# Sheet1.net
KiCad netlist of a schematic drawn in Altium Designer
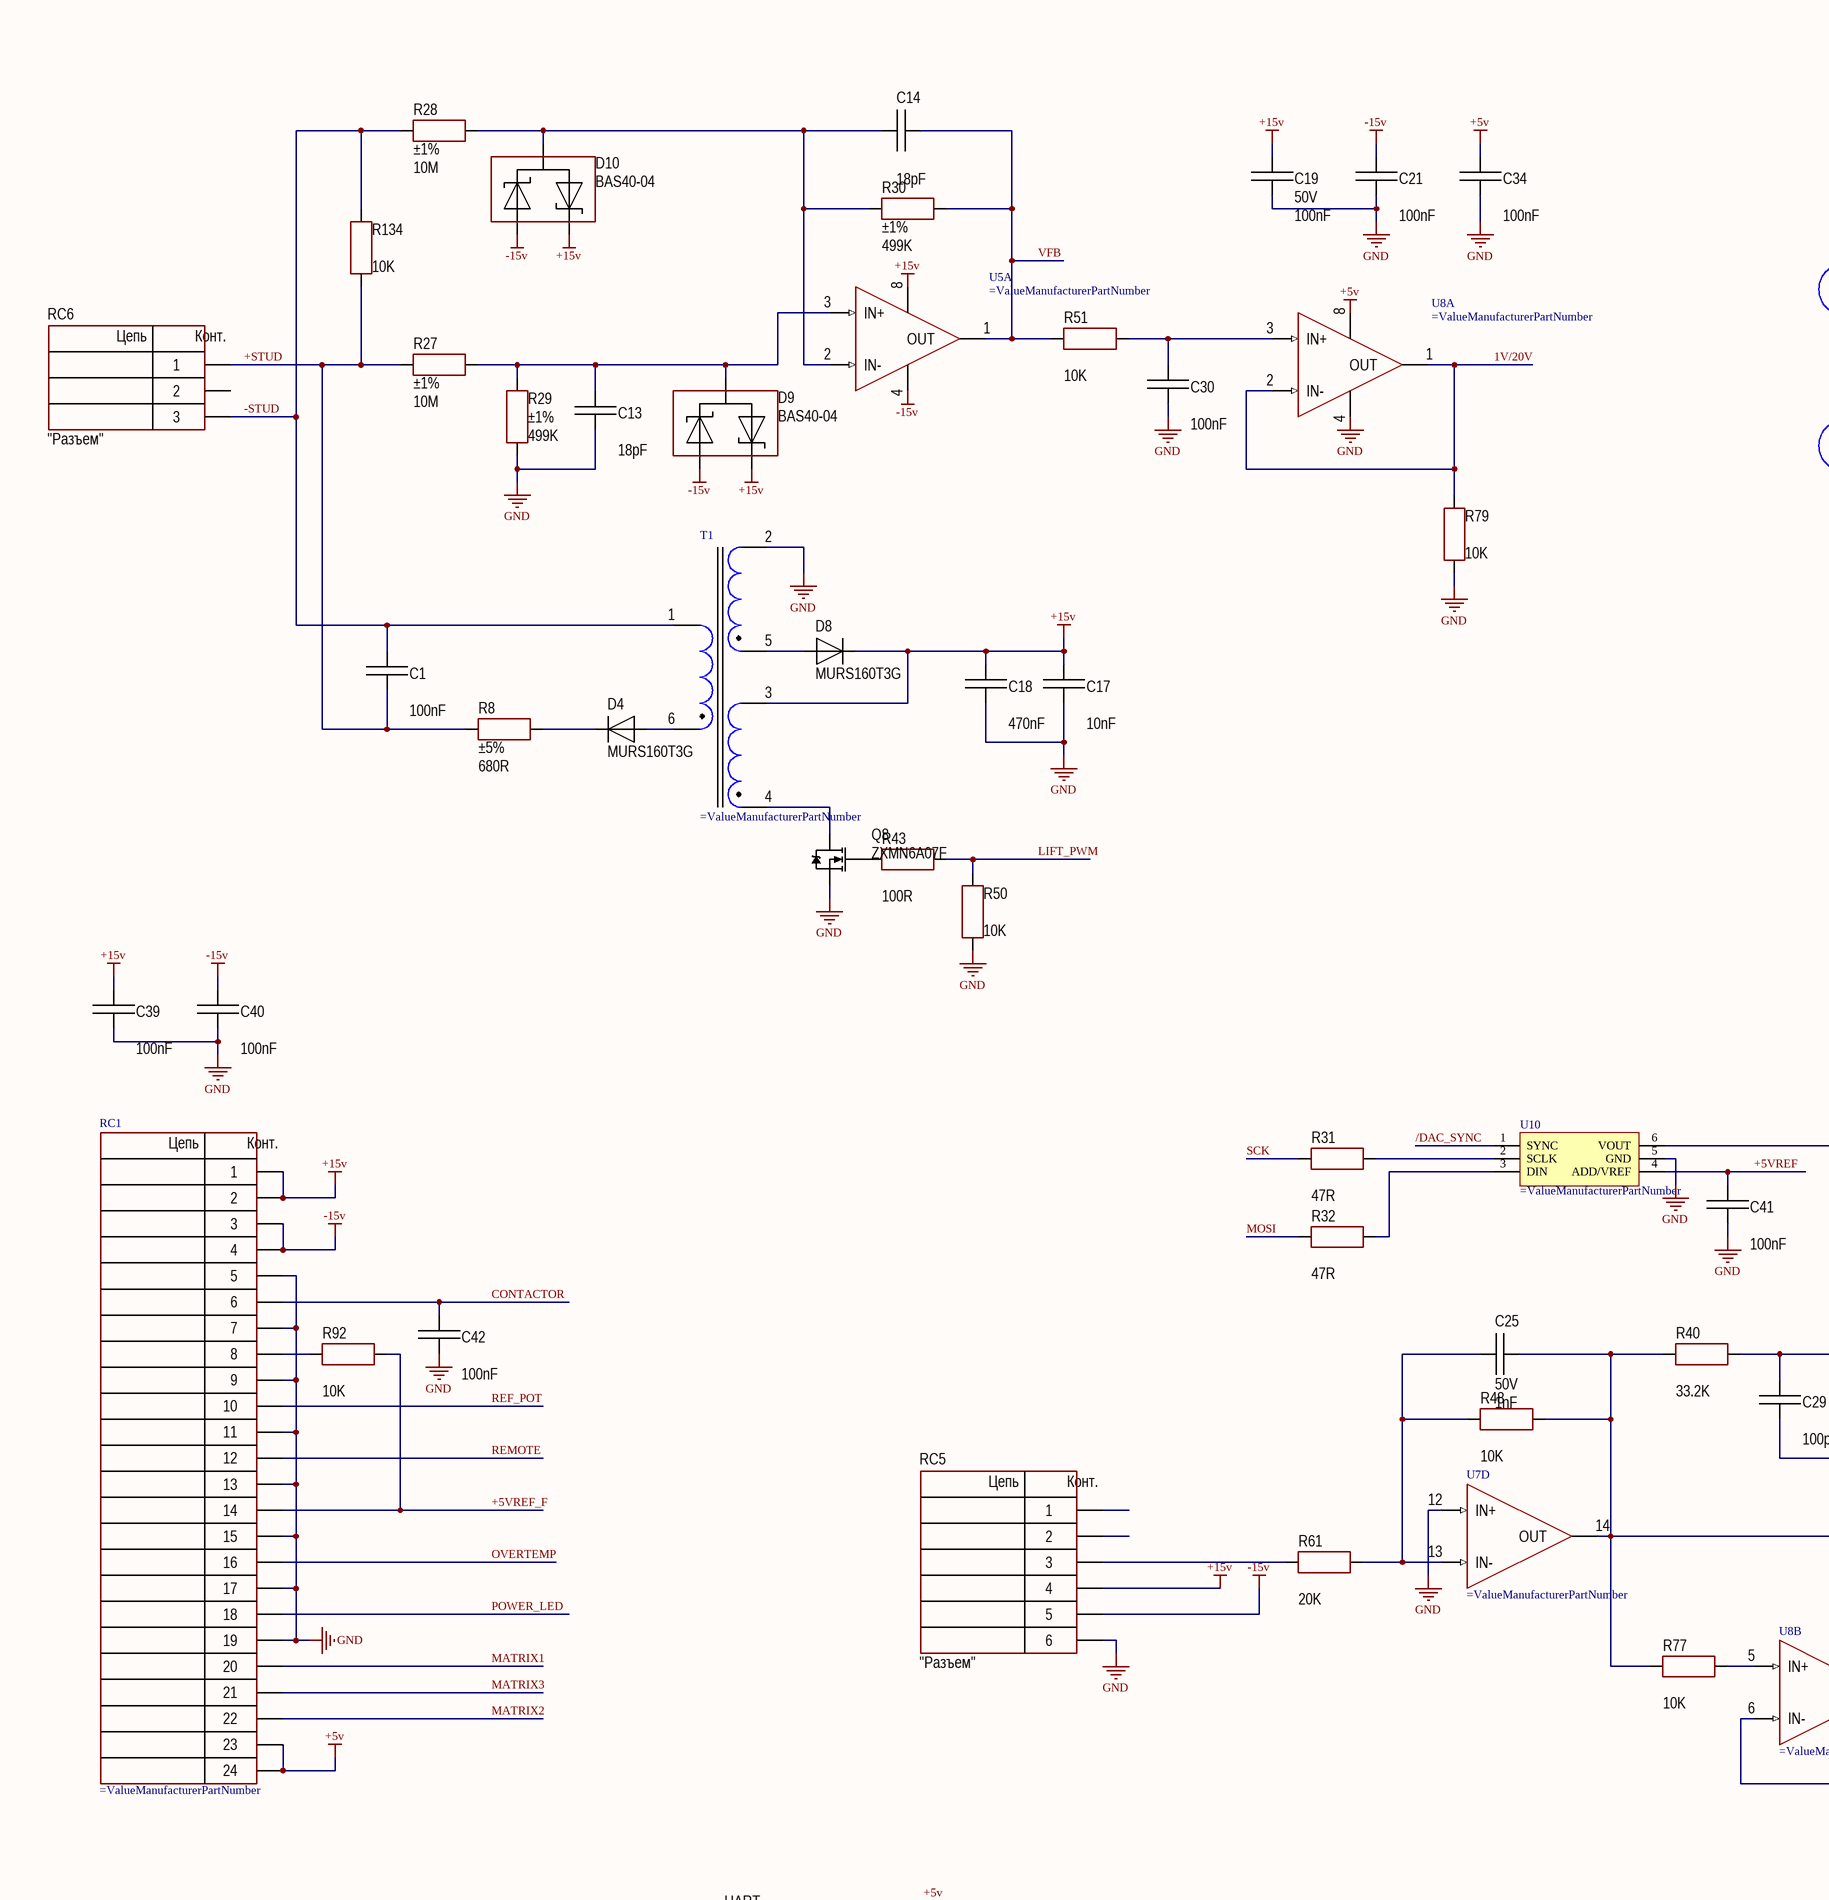
[diagram p0: Sheet1.SchDoc, top left]
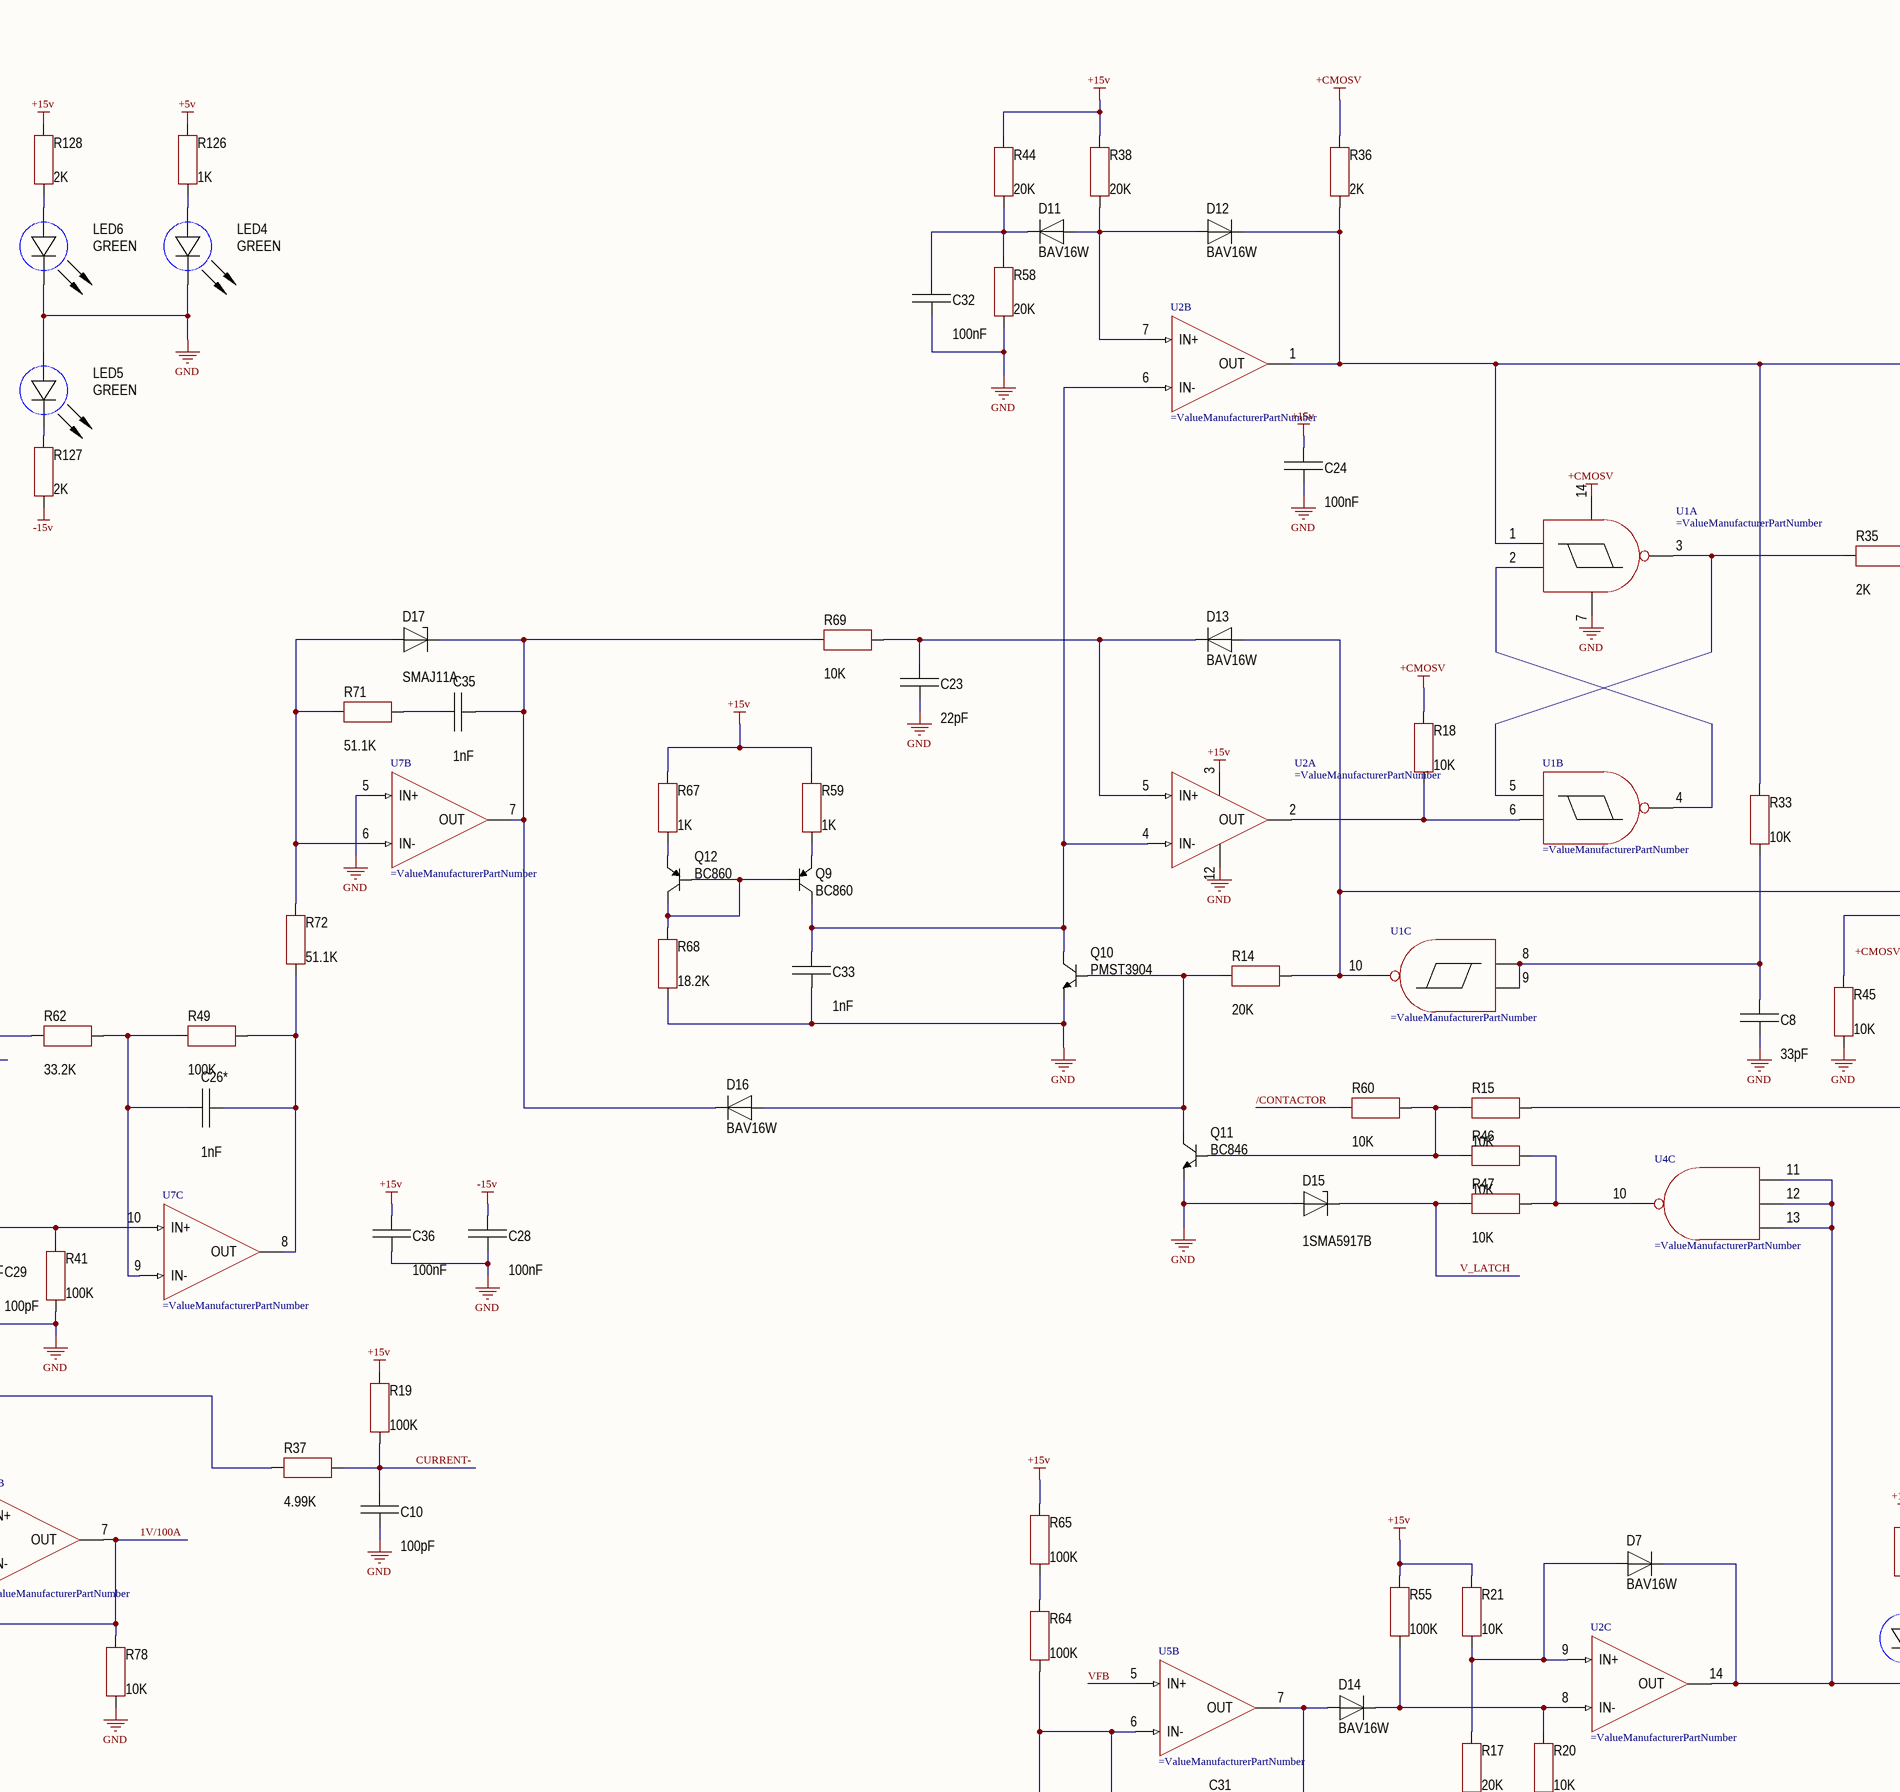
[diagram p1: Sheet1.SchDoc, top middle]
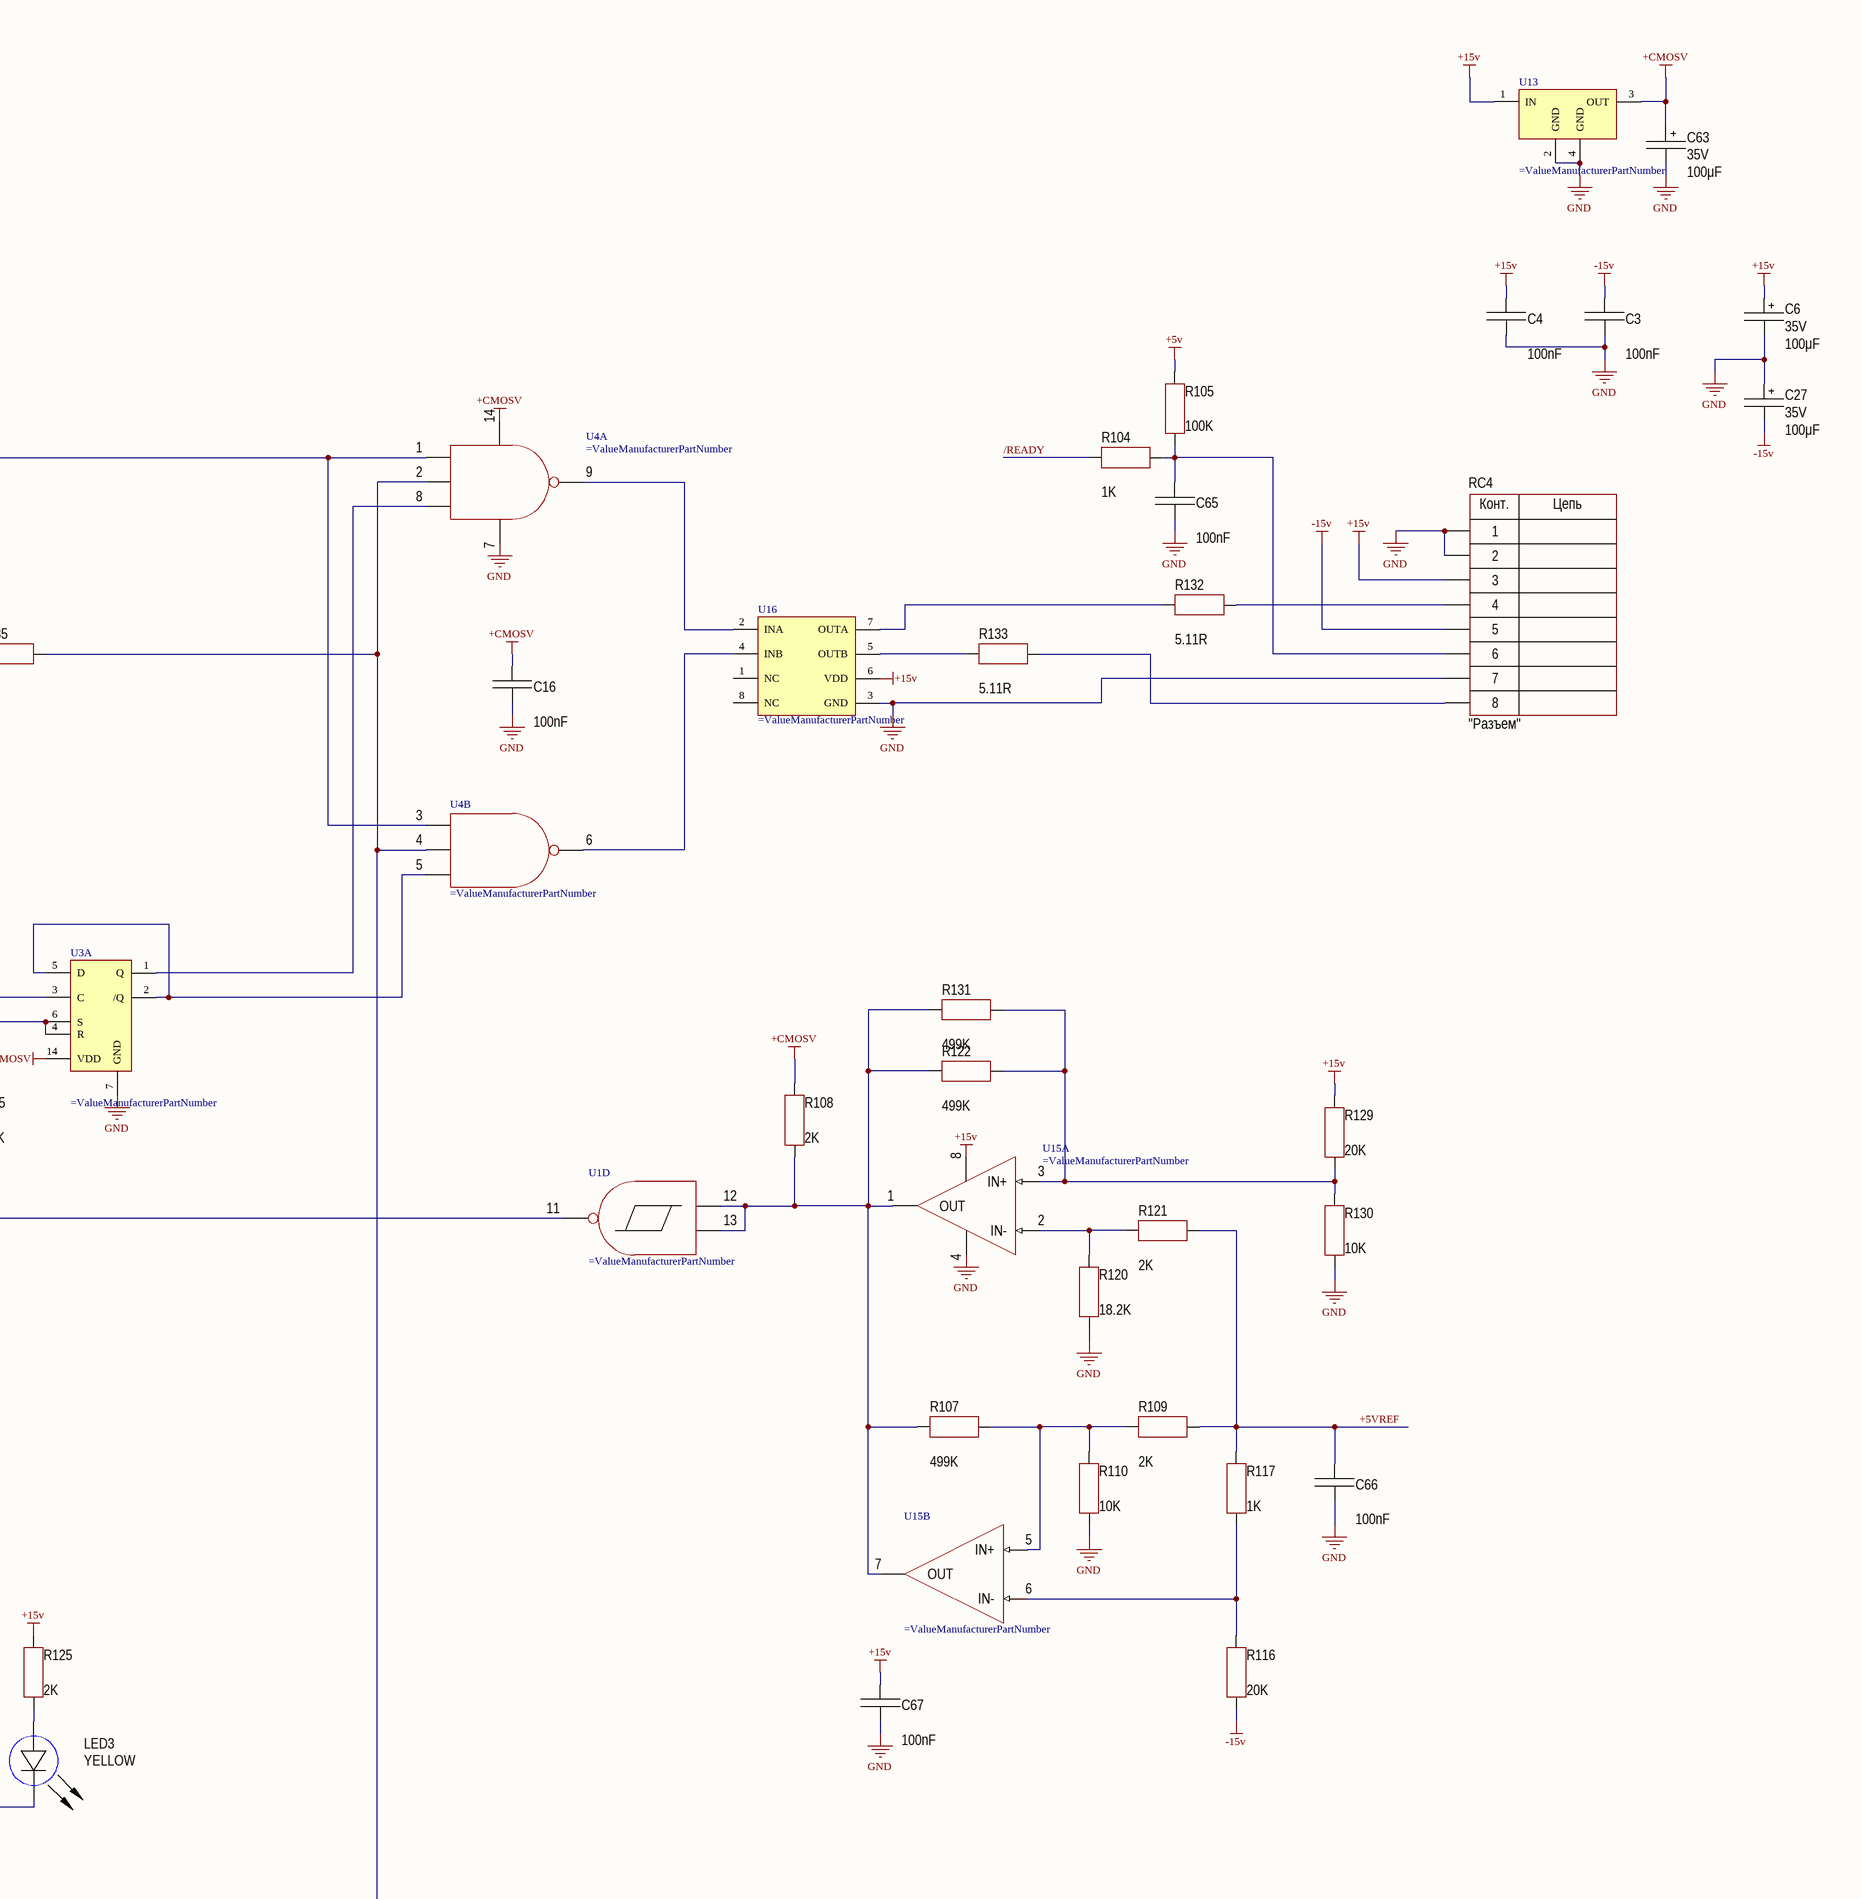
[diagram p2: Sheet1.SchDoc, top right]
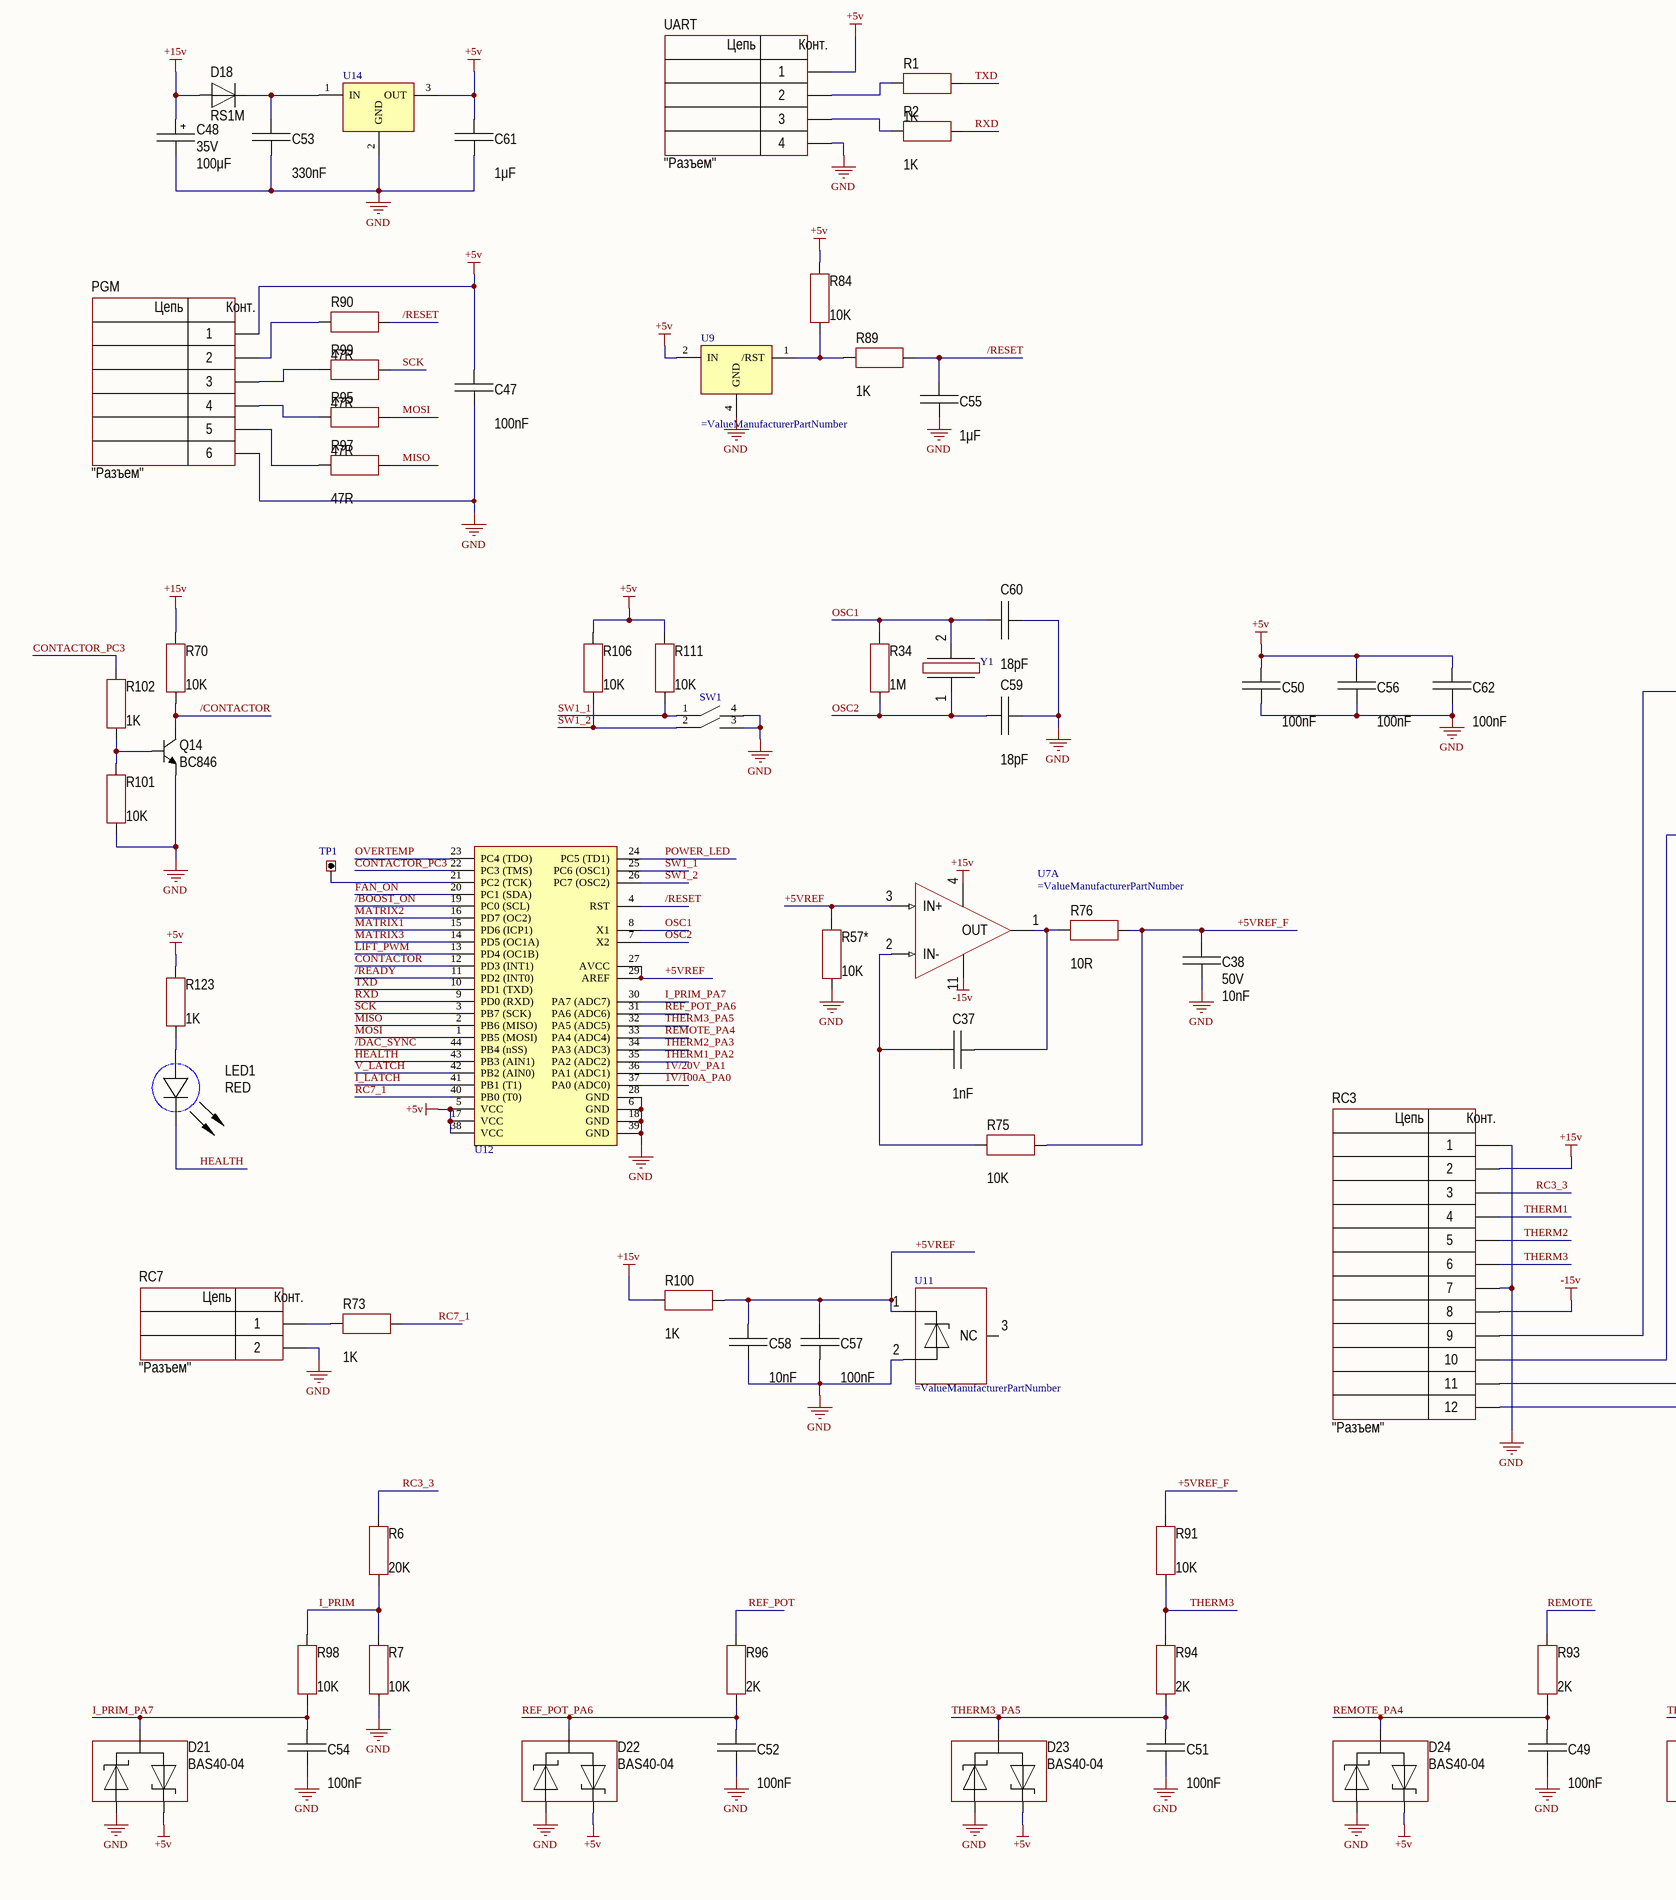
[diagram p3: Sheet1.SchDoc, bottom left]
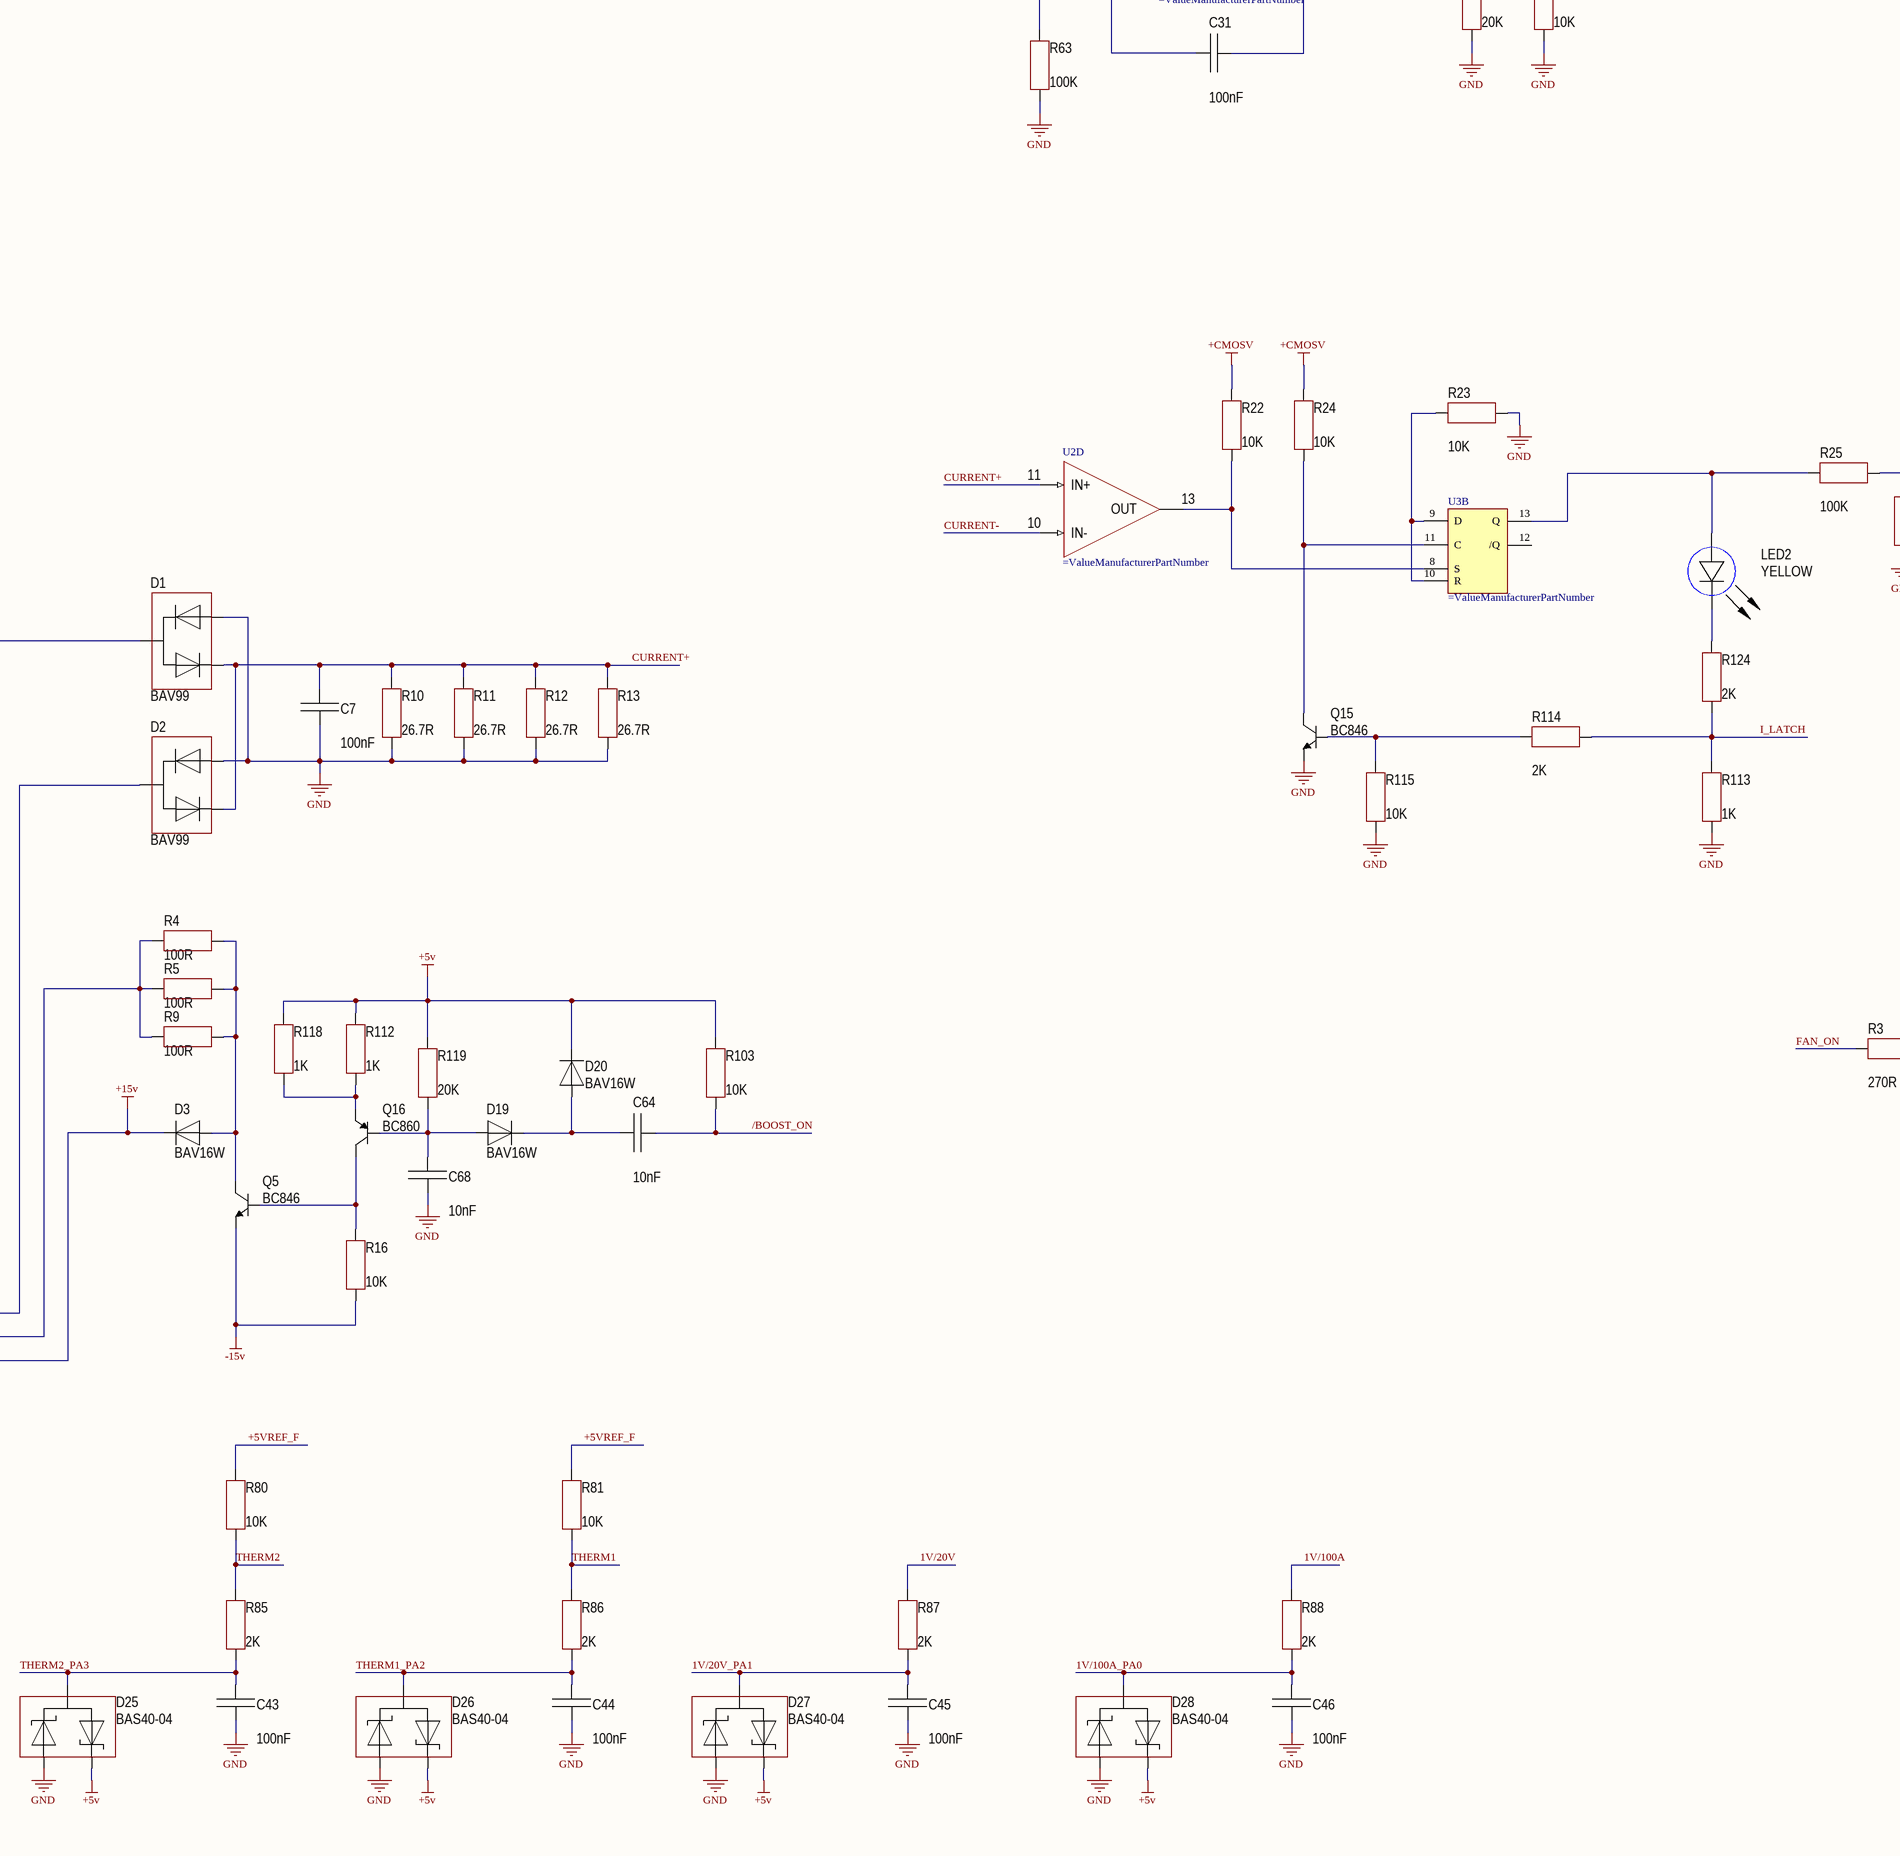
[diagram p4: Sheet1.SchDoc, bottom middle]
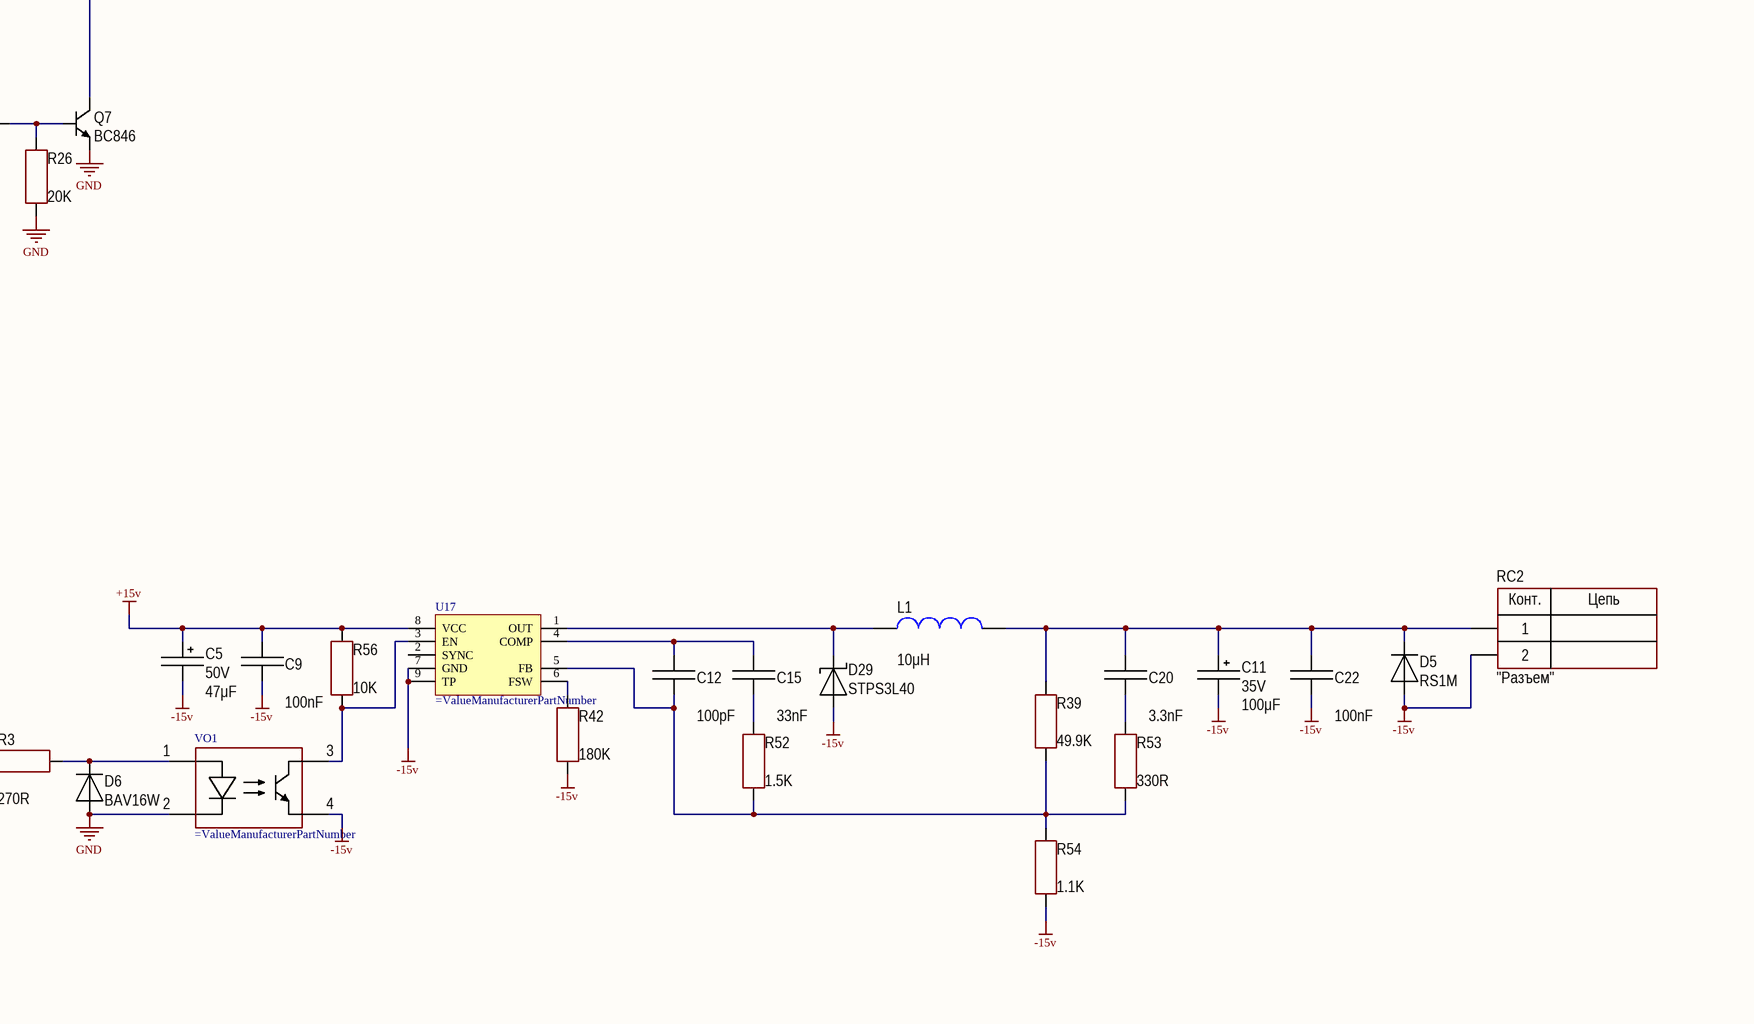
[diagram p5: Sheet1.SchDoc, bottom right]

(export (version "E")
  (design (tool "Eeschema 10.0.6"))
  (components
    (comp (ref "C1")
      (value "100nF")
      (footprint "PcbLib1:К10-17Б")
      (fields
        (field (name "MANUFACTURER") "Yageo")
        (field (name "PARTNUMBER") "CC1206KRX7R9BB104")
        (field (name "VALUEMANUFACTURERPARTNUMBER") "Capacitor, 100nF, К10-17Б")
      )
      (libsource (lib "Capacitor") (part "Ceramic_1206"))
    )
    (comp (ref "C3")
      (value "100nF")
      (footprint "StandardCase:CAP: 1206")
      (fields
        (field (name "MANUFACTURER") "Yageo")
        (field (name "PARTNUMBER") "CC1206KRX7R9BB104")
        (field (name "VALUEMANUFACTURERPARTNUMBER") "Ceramic capacitor, 100nF, 1206")
      )
      (libsource (lib "Capacitor") (part "Ceramic_1206"))
    )
    (comp (ref "C4")
      (value "100nF")
      (footprint "StandardCase:CAP: 1206")
      (fields
        (field (name "MANUFACTURER") "Yageo")
        (field (name "PARTNUMBER") "CC1206KRX7R9BB104")
        (field (name "VALUEMANUFACTURERPARTNUMBER") "Ceramic capacitor, 100nF, 1206")
      )
      (libsource (lib "Capacitor") (part "Ceramic_1206"))
    )
    (comp (ref "C5")
      (value "47μF")
      (footprint "PcbLib1:CAPAE7466X80L")
      (fields
        (field (name "MANUFACTURER") "Wurth")
        (field (name "PARTNUMBER") "EEEFK1H470XP")
        (field (name "VALUEMANUFACTURERPARTNUMBER") "EEEFK1H470XP, 47μF, 50V, D8")
        (field (name "VOLTAGE") "50V")
      )
      (libsource (lib "Capacitor") (part "Aluminium"))
    )
    (comp (ref "C6")
      (value "100μF")
      (footprint "PcbLib1:CAPAE7466X80L")
      (fields
        (field (name "MANUFACTURER") "Wurth")
        (field (name "PARTNUMBER") "EEEFK1V101XP")
        (field (name "VALUEMANUFACTURERPARTNUMBER") "EEEFK1V101XP, 100μF, 35V, D8")
        (field (name "VOLTAGE") "35V")
      )
      (libsource (lib "Capacitor") (part "Aluminium"))
    )
    (comp (ref "C7")
      (value "100nF")
      (footprint "StandardCase:CAP: 1206")
      (fields
        (field (name "MANUFACTURER") "Yageo")
        (field (name "PARTNUMBER") "CC1206KRX7R9BB104")
        (field (name "VALUEMANUFACTURERPARTNUMBER") "Ceramic capacitor, 100nF, 1206")
      )
      (libsource (lib "Capacitor") (part "Ceramic_1206"))
    )
    (comp (ref "C8")
      (value "33pF")
      (footprint "StandardCase:CAP: 1206")
      (fields
        (field (name "MANUFACTURER") "Yageo")
        (field (name "PARTNUMBER") "CC1206KRX7R9BB104")
        (field (name "VALUEMANUFACTURERPARTNUMBER") "Ceramic capacitor, 33pF, 1206")
      )
      (libsource (lib "Capacitor") (part "Ceramic_1206"))
    )
    (comp (ref "C9")
      (value "100nF")
      (footprint "StandardCase:CAP: 1206")
      (fields
        (field (name "MANUFACTURER") "Yageo")
        (field (name "PARTNUMBER") "CC1206KRX7R9BB104")
        (field (name "VALUEMANUFACTURERPARTNUMBER") "Ceramic capacitor, 100nF, 1206")
      )
      (libsource (lib "Capacitor") (part "Ceramic_1206"))
    )
    (comp (ref "C10")
      (value "100pF")
      (footprint "StandardCase:CAP: 1206")
      (fields
        (field (name "MANUFACTURER") "Yageo")
        (field (name "PARTNUMBER") "CC1206KRX7R9BB104")
        (field (name "VALUEMANUFACTURERPARTNUMBER") "Ceramic capacitor, 100pF, 1206")
      )
      (libsource (lib "Capacitor") (part "Ceramic_1206"))
    )
    (comp (ref "C11")
      (value "100μF")
      (footprint "PcbLib1:CAPAE7466X80L")
      (fields
        (field (name "MANUFACTURER") "Wurth")
        (field (name "PARTNUMBER") "EEEFK1V101XP")
        (field (name "VALUEMANUFACTURERPARTNUMBER") "EEEFK1V101XP, 100μF, 35V, D8")
        (field (name "VOLTAGE") "35V")
      )
      (libsource (lib "Capacitor") (part "Aluminium"))
    )
    (comp (ref "C12")
      (value "100pF")
      (footprint "StandardCase:CAP: 1206")
      (fields
        (field (name "MANUFACTURER") "Yageo")
        (field (name "PARTNUMBER") "CC1206KRX7R9BB104")
        (field (name "VALUEMANUFACTURERPARTNUMBER") "Ceramic capacitor, 100pF, 1206")
      )
      (libsource (lib "Capacitor") (part "Ceramic_1206"))
    )
    (comp (ref "C13")
      (value "18pF")
      (footprint "StandardCase:CAP: 1206")
      (fields
        (field (name "MANUFACTURER") "Yageo")
        (field (name "PARTNUMBER") "CC1206KRX7R9BB104")
        (field (name "VALUEMANUFACTURERPARTNUMBER") "Ceramic capacitor, 18pF, 1206")
      )
      (libsource (lib "Capacitor") (part "Ceramic_1206"))
    )
    (comp (ref "C14")
      (value "18pF")
      (footprint "StandardCase:CAP: 1206")
      (fields
        (field (name "MANUFACTURER") "Yageo")
        (field (name "PARTNUMBER") "CC1206KRX7R9BB104")
        (field (name "VALUEMANUFACTURERPARTNUMBER") "Ceramic capacitor, 18pF, 1206")
      )
      (libsource (lib "Capacitor") (part "Ceramic_1206"))
    )
    (comp (ref "C15")
      (value "33nF")
      (footprint "StandardCase:CAP: 1206")
      (fields
        (field (name "MANUFACTURER") "Yageo")
        (field (name "PARTNUMBER") "CC1206KRX7R9BB104")
        (field (name "VALUEMANUFACTURERPARTNUMBER") "Ceramic capacitor, 33nF, 1206")
      )
      (libsource (lib "Capacitor") (part "Ceramic_1206"))
    )
    (comp (ref "C16")
      (value "100nF")
      (footprint "StandardCase:CAP: 1206")
      (fields
        (field (name "MANUFACTURER") "Yageo")
        (field (name "PARTNUMBER") "CC1206KRX7R9BB104")
        (field (name "VALUEMANUFACTURERPARTNUMBER") "Ceramic capacitor, 100nF, 1206")
      )
      (libsource (lib "Capacitor") (part "Ceramic_1206"))
    )
    (comp (ref "C17")
      (value "10nF")
      (footprint "StandardCase:CAP: 1206")
      (fields
        (field (name "MANUFACTURER") "Yageo")
        (field (name "PARTNUMBER") "CC1206KRX7R9BB104")
        (field (name "VALUEMANUFACTURERPARTNUMBER") "Ceramic capacitor, 10nF, 1206")
      )
      (libsource (lib "Capacitor") (part "Ceramic_1206"))
    )
    (comp (ref "C18")
      (value "470nF")
      (footprint "StandardCase:CAP: 1206")
      (fields
        (field (name "MANUFACTURER") "Yageo")
        (field (name "PARTNUMBER") "CC1206KRX7R9BB104")
        (field (name "VALUEMANUFACTURERPARTNUMBER") "Ceramic capacitor, 470nF, 1206")
      )
      (libsource (lib "Capacitor") (part "Ceramic_1206"))
    )
    (comp (ref "C19")
      (value "100nF")
      (footprint "StandardCase:CAP: 1206")
      (fields
        (field (name "MANUFACTURER") "Yageo")
        (field (name "PARTNUMBER") "CC1206KRX7R9BB104")
        (field (name "VALUEMANUFACTURERPARTNUMBER") "Ceramic capacitor, 100nF, 1206")
        (field (name "VOLTAGE") "50V")
      )
      (libsource (lib "Capacitor") (part "Ceramic_1206"))
    )
    (comp (ref "C20")
      (value "3.3nF")
      (footprint "StandardCase:CAP: 1206")
      (fields
        (field (name "MANUFACTURER") "Yageo")
        (field (name "PARTNUMBER") "CC1206KRX7R9BB104")
        (field (name "VALUEMANUFACTURERPARTNUMBER") "Ceramic capacitor, 3.3nF, 1206")
      )
      (libsource (lib "Capacitor") (part "Ceramic_1206"))
    )
    (comp (ref "C21")
      (value "100nF")
      (footprint "StandardCase:CAP: 1206")
      (fields
        (field (name "MANUFACTURER") "Yageo")
        (field (name "PARTNUMBER") "CC1206KRX7R9BB104")
        (field (name "VALUEMANUFACTURERPARTNUMBER") "Ceramic capacitor, 100nF, 1206")
      )
      (libsource (lib "Capacitor") (part "Ceramic_1206"))
    )
    (comp (ref "C22")
      (value "100nF")
      (footprint "StandardCase:CAP: 1206")
      (fields
        (field (name "MANUFACTURER") "Yageo")
        (field (name "PARTNUMBER") "CC1206KRX7R9BB104")
        (field (name "VALUEMANUFACTURERPARTNUMBER") "Ceramic capacitor, 100nF, 1206")
      )
      (libsource (lib "Capacitor") (part "Ceramic_1206"))
    )
    (comp (ref "C23")
      (value "22pF")
      (footprint "StandardCase:CAP: 1206")
      (fields
        (field (name "MANUFACTURER") "Yageo")
        (field (name "PARTNUMBER") "CC1206KRX7R9BB104")
        (field (name "VALUEMANUFACTURERPARTNUMBER") "Ceramic capacitor, 22pF, 1206")
      )
      (libsource (lib "Capacitor") (part "Ceramic_1206"))
    )
    (comp (ref "C24")
      (value "100nF")
      (footprint "StandardCase:CAP: 1206")
      (fields
        (field (name "MANUFACTURER") "Yageo")
        (field (name "PARTNUMBER") "CC1206KRX7R9BB104")
        (field (name "VALUEMANUFACTURERPARTNUMBER") "Ceramic capacitor, 100nF, 1206")
      )
      (libsource (lib "Capacitor") (part "Ceramic_1206"))
    )
    (comp (ref "C25")
      (value "1nF")
      (footprint "StandardCase:CAP: 1206")
      (fields
        (field (name "MANUFACTURER") "Yageo")
        (field (name "PARTNUMBER") "CC1206KRX7R9BB104")
        (field (name "VALUEMANUFACTURERPARTNUMBER") "Ceramic capacitor, 1nF, 1206")
        (field (name "VOLTAGE") "50V")
      )
      (libsource (lib "Capacitor") (part "Ceramic_1206"))
    )
    (comp (ref "C26*")
      (value "1nF")
      (footprint "StandardCase:CAP: 1206")
      (fields
        (field (name "MANUFACTURER") "Yageo")
        (field (name "PARTNUMBER") "CC1206KRX7R9BB104")
        (field (name "VALUEMANUFACTURERPARTNUMBER") "Ceramic capacitor, 1nF, 1206")
      )
      (libsource (lib "Capacitor") (part "Ceramic_1206"))
    )
    (comp (ref "C27")
      (value "100μF")
      (footprint "PcbLib1:CAPAE7466X80L")
      (fields
        (field (name "MANUFACTURER") "Wurth")
        (field (name "PARTNUMBER") "EEEFK1V101XP")
        (field (name "VALUEMANUFACTURERPARTNUMBER") "EEEFK1V101XP, 100μF, 35V, D8")
        (field (name "VOLTAGE") "35V")
      )
      (libsource (lib "Capacitor") (part "Aluminium"))
    )
    (comp (ref "C28")
      (value "100nF")
      (footprint "StandardCase:CAP: 1206")
      (fields
        (field (name "MANUFACTURER") "Yageo")
        (field (name "PARTNUMBER") "CC1206KRX7R9BB104")
        (field (name "VALUEMANUFACTURERPARTNUMBER") "Ceramic capacitor, 100nF, 1206")
      )
      (libsource (lib "Capacitor") (part "Ceramic_1206"))
    )
    (comp (ref "C29")
      (value "100pF")
      (footprint "StandardCase:CAP: 1206")
      (fields
        (field (name "MANUFACTURER") "Yageo")
        (field (name "PARTNUMBER") "CC1206KRX7R9BB104")
        (field (name "VALUEMANUFACTURERPARTNUMBER") "Ceramic capacitor, 100pF, 1206")
      )
      (libsource (lib "Capacitor") (part "Ceramic_1206"))
    )
    (comp (ref "C30")
      (value "100nF")
      (footprint "StandardCase:CAP: 1206")
      (fields
        (field (name "MANUFACTURER") "Yageo")
        (field (name "PARTNUMBER") "CC1206KRX7R9BB104")
        (field (name "VALUEMANUFACTURERPARTNUMBER") "Ceramic capacitor, 100nF, 1206")
      )
      (libsource (lib "Capacitor") (part "Ceramic_1206"))
    )
    (comp (ref "C31")
      (value "100nF")
      (footprint "StandardCase:CAP: 1206")
      (fields
        (field (name "MANUFACTURER") "Yageo")
        (field (name "PARTNUMBER") "CC1206KRX7R9BB104")
        (field (name "VALUEMANUFACTURERPARTNUMBER") "Ceramic capacitor, 100nF, 1206")
      )
      (libsource (lib "Capacitor") (part "Ceramic_1206"))
    )
    (comp (ref "C32")
      (value "100nF")
      (footprint "StandardCase:CAP: 1206")
      (fields
        (field (name "MANUFACTURER") "Yageo")
        (field (name "PARTNUMBER") "CC1206KRX7R9BB104")
        (field (name "VALUEMANUFACTURERPARTNUMBER") "Ceramic capacitor, 100nF, 1206")
      )
      (libsource (lib "Capacitor") (part "Ceramic_1206"))
    )
    (comp (ref "C33")
      (value "1nF")
      (footprint "StandardCase:CAP: 1206")
      (fields
        (field (name "MANUFACTURER") "Yageo")
        (field (name "PARTNUMBER") "CC1206KRX7R9BB104")
        (field (name "VALUEMANUFACTURERPARTNUMBER") "Ceramic capacitor, 1nF, 1206")
      )
      (libsource (lib "Capacitor") (part "Ceramic_1206"))
    )
    (comp (ref "C34")
      (value "100nF")
      (footprint "StandardCase:CAP: 1206")
      (fields
        (field (name "MANUFACTURER") "Yageo")
        (field (name "PARTNUMBER") "CC1206KRX7R9BB104")
        (field (name "VALUEMANUFACTURERPARTNUMBER") "Ceramic capacitor, 100nF, 1206")
      )
      (libsource (lib "Capacitor") (part "Ceramic_1206"))
    )
    (comp (ref "C35")
      (value "1nF")
      (footprint "StandardCase:CAP: 1206")
      (fields
        (field (name "MANUFACTURER") "Yageo")
        (field (name "PARTNUMBER") "CC1206KRX7R9BB104")
        (field (name "VALUEMANUFACTURERPARTNUMBER") "Ceramic capacitor, 1nF, 1206")
      )
      (libsource (lib "Capacitor") (part "Ceramic_1206"))
    )
    (comp (ref "C36")
      (value "100nF")
      (footprint "StandardCase:CAP: 1206")
      (fields
        (field (name "MANUFACTURER") "Yageo")
        (field (name "PARTNUMBER") "CC1206KRX7R9BB104")
        (field (name "VALUEMANUFACTURERPARTNUMBER") "Ceramic capacitor, 100nF, 1206")
      )
      (libsource (lib "Capacitor") (part "Ceramic_1206"))
    )
    (comp (ref "C37")
      (value "1nF")
      (footprint "StandardCase:CAP: 1206")
      (fields
        (field (name "MANUFACTURER") "Yageo")
        (field (name "PARTNUMBER") "CC1206KRX7R9BB104")
        (field (name "VALUEMANUFACTURERPARTNUMBER") "Ceramic capacitor, 1nF, 1206")
      )
      (libsource (lib "Capacitor") (part "Ceramic_1206"))
    )
    (comp (ref "C38")
      (value "10nF")
      (footprint "StandardCase:CAP: 1206")
      (fields
        (field (name "MANUFACTURER") "Yageo")
        (field (name "PARTNUMBER") "CC1206KRX7R9BB104")
        (field (name "VALUEMANUFACTURERPARTNUMBER") "Ceramic capacitor, 10nF, 1206")
        (field (name "VOLTAGE") "50V")
      )
      (libsource (lib "Capacitor") (part "Ceramic_1206"))
    )
    (comp (ref "C39")
      (value "100nF")
      (footprint "StandardCase:CAP: 1206")
      (fields
        (field (name "MANUFACTURER") "Yageo")
        (field (name "PARTNUMBER") "CC1206KRX7R9BB104")
        (field (name "VALUEMANUFACTURERPARTNUMBER") "Ceramic capacitor, 100nF, 1206")
      )
      (libsource (lib "Capacitor") (part "Ceramic_1206"))
    )
    (comp (ref "C40")
      (value "100nF")
      (footprint "StandardCase:CAP: 1206")
      (fields
        (field (name "MANUFACTURER") "Yageo")
        (field (name "PARTNUMBER") "CC1206KRX7R9BB104")
        (field (name "VALUEMANUFACTURERPARTNUMBER") "Ceramic capacitor, 100nF, 1206")
      )
      (libsource (lib "Capacitor") (part "Ceramic_1206"))
    )
    (comp (ref "C41")
      (value "100nF")
      (footprint "StandardCase:CAP: 1206")
      (fields
        (field (name "MANUFACTURER") "Yageo")
        (field (name "PARTNUMBER") "CC1206KRX7R9BB104")
        (field (name "VALUEMANUFACTURERPARTNUMBER") "Ceramic capacitor, 100nF, 1206")
      )
      (libsource (lib "Capacitor") (part "Ceramic_1206"))
    )
    (comp (ref "C42")
      (value "100nF")
      (footprint "StandardCase:CAP: 1206")
      (fields
        (field (name "MANUFACTURER") "Yageo")
        (field (name "PARTNUMBER") "CC1206KRX7R9BB104")
        (field (name "VALUEMANUFACTURERPARTNUMBER") "Ceramic capacitor, 100nF, 1206")
      )
      (libsource (lib "Capacitor") (part "Ceramic_1206"))
    )
    (comp (ref "C43")
      (value "100nF")
      (footprint "StandardCase:CAP: 1206")
      (fields
        (field (name "MANUFACTURER") "Yageo")
        (field (name "PARTNUMBER") "CC1206KRX7R9BB104")
        (field (name "VALUEMANUFACTURERPARTNUMBER") "Ceramic capacitor, 100nF, 1206")
      )
      (libsource (lib "Capacitor") (part "Ceramic_1206"))
    )
    (comp (ref "C44")
      (value "100nF")
      (footprint "StandardCase:CAP: 1206")
      (fields
        (field (name "MANUFACTURER") "Yageo")
        (field (name "PARTNUMBER") "CC1206KRX7R9BB104")
        (field (name "VALUEMANUFACTURERPARTNUMBER") "Ceramic capacitor, 100nF, 1206")
      )
      (libsource (lib "Capacitor") (part "Ceramic_1206"))
    )
    (comp (ref "C45")
      (value "100nF")
      (footprint "StandardCase:CAP: 1206")
      (fields
        (field (name "MANUFACTURER") "Yageo")
        (field (name "PARTNUMBER") "CC1206KRX7R9BB104")
        (field (name "VALUEMANUFACTURERPARTNUMBER") "Ceramic capacitor, 100nF, 1206")
      )
      (libsource (lib "Capacitor") (part "Ceramic_1206"))
    )
    (comp (ref "C46")
      (value "100nF")
      (footprint "StandardCase:CAP: 1206")
      (fields
        (field (name "MANUFACTURER") "Yageo")
        (field (name "PARTNUMBER") "CC1206KRX7R9BB104")
        (field (name "VALUEMANUFACTURERPARTNUMBER") "Ceramic capacitor, 100nF, 1206")
      )
      (libsource (lib "Capacitor") (part "Ceramic_1206"))
    )
    (comp (ref "C47")
      (value "100nF")
      (footprint "StandardCase:CAP: 1206")
      (fields
        (field (name "MANUFACTURER") "Yageo")
        (field (name "PARTNUMBER") "CC1206KRX7R9BB104")
        (field (name "VALUEMANUFACTURERPARTNUMBER") "Ceramic capacitor, 100nF, 1206")
      )
      (libsource (lib "Capacitor") (part "Ceramic_1206"))
    )
    (comp (ref "C48")
      (value "100μF")
      (footprint "PcbLib1:CAPAE7466X80L")
      (fields
        (field (name "MANUFACTURER") "Wurth")
        (field (name "PARTNUMBER") "EEEFK1V101XP")
        (field (name "VALUEMANUFACTURERPARTNUMBER") "EEEFK1V101XP, 100μF, 35V, D8")
        (field (name "VOLTAGE") "35V")
      )
      (libsource (lib "Capacitor") (part "Aluminium"))
    )
    (comp (ref "C49")
      (value "100nF")
      (footprint "StandardCase:CAP: 1206")
      (fields
        (field (name "MANUFACTURER") "Yageo")
        (field (name "PARTNUMBER") "CC1206KRX7R9BB104")
        (field (name "VALUEMANUFACTURERPARTNUMBER") "Ceramic capacitor, 100nF, 1206")
      )
      (libsource (lib "Capacitor") (part "Ceramic_1206"))
    )
    (comp (ref "C50")
      (value "100nF")
      (footprint "StandardCase:CAP: 1206")
      (fields
        (field (name "MANUFACTURER") "Yageo")
        (field (name "PARTNUMBER") "CC1206KRX7R9BB104")
        (field (name "VALUEMANUFACTURERPARTNUMBER") "Ceramic capacitor, 100nF, 1206")
      )
      (libsource (lib "Capacitor") (part "Ceramic_1206"))
    )
    (comp (ref "C51")
      (value "100nF")
      (footprint "StandardCase:CAP: 1206")
      (fields
        (field (name "MANUFACTURER") "Yageo")
        (field (name "PARTNUMBER") "CC1206KRX7R9BB104")
        (field (name "VALUEMANUFACTURERPARTNUMBER") "Ceramic capacitor, 100nF, 1206")
      )
      (libsource (lib "Capacitor") (part "Ceramic_1206"))
    )
    (comp (ref "C52")
      (value "100nF")
      (footprint "StandardCase:CAP: 1206")
      (fields
        (field (name "MANUFACTURER") "Yageo")
        (field (name "PARTNUMBER") "CC1206KRX7R9BB104")
        (field (name "VALUEMANUFACTURERPARTNUMBER") "Ceramic capacitor, 100nF, 1206")
      )
      (libsource (lib "Capacitor") (part "Ceramic_1206"))
    )
    (comp (ref "C53")
      (value "330nF")
      (footprint "StandardCase:CAP: 1206")
      (fields
        (field (name "MANUFACTURER") "Yageo")
        (field (name "PARTNUMBER") "CC1206KRX7R9BB104")
        (field (name "VALUEMANUFACTURERPARTNUMBER") "Ceramic capacitor, 330nF, 1206")
      )
      (libsource (lib "Capacitor") (part "Ceramic_1206"))
    )
    (comp (ref "C54")
      (value "100nF")
      (footprint "StandardCase:CAP: 1206")
      (fields
        (field (name "MANUFACTURER") "Yageo")
        (field (name "PARTNUMBER") "CC1206KRX7R9BB104")
        (field (name "VALUEMANUFACTURERPARTNUMBER") "Ceramic capacitor, 100nF, 1206")
      )
      (libsource (lib "Capacitor") (part "Ceramic_1206"))
    )
    (comp (ref "C55")
      (value "1μF")
      (footprint "StandardCase:CAP: 1206")
      (fields
        (field (name "MANUFACTURER") "Yageo")
        (field (name "PARTNUMBER") "CC1206KRX7R9BB104")
        (field (name "VALUEMANUFACTURERPARTNUMBER") "Ceramic capacitor, 1μF, 1206")
      )
      (libsource (lib "Capacitor") (part "Ceramic_1206"))
    )
    (comp (ref "C56")
      (value "100nF")
      (footprint "StandardCase:CAP: 1206")
      (fields
        (field (name "MANUFACTURER") "Yageo")
        (field (name "PARTNUMBER") "CC1206KRX7R9BB104")
        (field (name "VALUEMANUFACTURERPARTNUMBER") "Ceramic capacitor, 100nF, 1206")
      )
      (libsource (lib "Capacitor") (part "Ceramic_1206"))
    )
    (comp (ref "C57")
      (value "100nF")
      (footprint "StandardCase:CAP: 1206")
      (fields
        (field (name "MANUFACTURER") "Yageo")
        (field (name "PARTNUMBER") "CC1206KRX7R9BB104")
        (field (name "VALUEMANUFACTURERPARTNUMBER") "Ceramic capacitor, 100nF, 1206")
      )
      (libsource (lib "Capacitor") (part "Ceramic_1206"))
    )
    (comp (ref "C58")
      (value "10nF")
      (footprint "StandardCase:CAP: 1206")
      (fields
        (field (name "MANUFACTURER") "Yageo")
        (field (name "PARTNUMBER") "CC1206KRX7R9BB104")
        (field (name "VALUEMANUFACTURERPARTNUMBER") "Ceramic capacitor, 10nF, 1206")
      )
      (libsource (lib "Capacitor") (part "Ceramic_1206"))
    )
    (comp (ref "C59")
      (value "18pF")
      (footprint "StandardCase:CAP: 1206")
      (fields
        (field (name "MANUFACTURER") "Yageo")
        (field (name "PARTNUMBER") "CC1206KRX7R9BB104")
        (field (name "VALUEMANUFACTURERPARTNUMBER") "Ceramic capacitor, 18pF, 1206")
      )
      (libsource (lib "Capacitor") (part "Ceramic_1206"))
    )
    (comp (ref "C60")
      (value "18pF")
      (footprint "StandardCase:CAP: 1206")
      (fields
        (field (name "MANUFACTURER") "Yageo")
        (field (name "PARTNUMBER") "CC1206KRX7R9BB104")
        (field (name "VALUEMANUFACTURERPARTNUMBER") "Ceramic capacitor, 18pF, 1206")
      )
      (libsource (lib "Capacitor") (part "Ceramic_1206"))
    )
    (comp (ref "C61")
      (value "1μF")
      (footprint "StandardCase:CAP: 1206")
      (fields
        (field (name "MANUFACTURER") "Yageo")
        (field (name "PARTNUMBER") "CC1206KRX7R9BB104")
        (field (name "VALUEMANUFACTURERPARTNUMBER") "Ceramic capacitor, 1μF, 1206")
      )
      (libsource (lib "Capacitor") (part "Ceramic_1206"))
    )
    (comp (ref "C62")
      (value "100nF")
      (footprint "StandardCase:CAP: 1206")
      (fields
        (field (name "MANUFACTURER") "Yageo")
        (field (name "PARTNUMBER") "CC1206KRX7R9BB104")
        (field (name "VALUEMANUFACTURERPARTNUMBER") "Ceramic capacitor, 100nF, 1206")
      )
      (libsource (lib "Capacitor") (part "Ceramic_1206"))
    )
    (comp (ref "C63")
      (value "100μF")
      (footprint "PcbLib1:CAPAE7466X80L")
      (fields
        (field (name "MANUFACTURER") "Wurth")
        (field (name "PARTNUMBER") "EEEFK1V101XP")
        (field (name "VALUEMANUFACTURERPARTNUMBER") "EEEFK1V101XP, 100μF, 35V, D8")
        (field (name "VOLTAGE") "35V")
      )
      (libsource (lib "Capacitor") (part "Aluminium"))
    )
    (comp (ref "C64")
      (value "10nF")
      (footprint "StandardCase:CAP: 1206")
      (fields
        (field (name "MANUFACTURER") "Yageo")
        (field (name "PARTNUMBER") "CC1206KRX7R9BB104")
        (field (name "VALUEMANUFACTURERPARTNUMBER") "Ceramic capacitor, 10nF, 1206")
      )
      (libsource (lib "Capacitor") (part "Ceramic_1206"))
    )
    (comp (ref "C65")
      (value "100nF")
      (footprint "StandardCase:CAP: 1206")
      (fields
        (field (name "MANUFACTURER") "Yageo")
        (field (name "PARTNUMBER") "CC1206KRX7R9BB104")
        (field (name "VALUEMANUFACTURERPARTNUMBER") "Ceramic capacitor, 100nF, 1206")
      )
      (libsource (lib "Capacitor") (part "Ceramic_1206"))
    )
    (comp (ref "C66")
      (value "100nF")
      (footprint "StandardCase:CAP: 1206")
      (fields
        (field (name "MANUFACTURER") "Yageo")
        (field (name "PARTNUMBER") "CC1206KRX7R9BB104")
        (field (name "VALUEMANUFACTURERPARTNUMBER") "Ceramic capacitor, 100nF, 1206")
      )
      (libsource (lib "Capacitor") (part "Ceramic_1206"))
    )
    (comp (ref "C67")
      (value "100nF")
      (footprint "StandardCase:CAP: 1206")
      (fields
        (field (name "MANUFACTURER") "Yageo")
        (field (name "PARTNUMBER") "CC1206KRX7R9BB104")
        (field (name "VALUEMANUFACTURERPARTNUMBER") "Ceramic capacitor, 100nF, 1206")
      )
      (libsource (lib "Capacitor") (part "Ceramic_1206"))
    )
    (comp (ref "C68")
      (value "10nF")
      (footprint "StandardCase:CAP: 1206")
      (fields
        (field (name "MANUFACTURER") "Yageo")
        (field (name "PARTNUMBER") "CC1206KRX7R9BB104")
        (field (name "VALUEMANUFACTURERPARTNUMBER") "Ceramic capacitor, 10nF, 1206")
      )
      (libsource (lib "Capacitor") (part "Ceramic_1206"))
    )
    (comp (ref "D1")
      (value "~")
      (footprint "StandardCase:SOT23")
      (fields
        (field (name "MANUFACTURER") "Diodes Incorporated")
        (field (name "VALUEMANUFACTURERPARTNUMBER") "BAV99, SOT-23")
        (field (name "VOLTAGE") "85V")
        (field (name "PARTNUMBER") "BAV99")
      )
      (libsource (lib "Diode") (part "Diode_array"))
    )
    (comp (ref "D2")
      (value "~")
      (footprint "StandardCase:SOT23")
      (fields
        (field (name "MANUFACTURER") "Diodes Incorporated")
        (field (name "VALUEMANUFACTURERPARTNUMBER") "BAV99, SOT-23")
        (field (name "VOLTAGE") "85V")
        (field (name "PARTNUMBER") "BAV99")
      )
      (libsource (lib "Diode") (part "Diode_array"))
    )
    (comp (ref "D3")
      (value "~")
      (footprint "StandardCase:DIODE: SOD123")
      (fields
        (field (name "MANUFACTURER") "DIODES")
        (field (name "VALUEMANUFACTURERPARTNUMBER") "BAV16W@ DIODES, SOD123")
        (field (name "VOLTAGE") "1000V")
        (field (name "PARTNUMBER") "BAV16W")
      )
      (libsource (lib "Diode") (part "Diode_single"))
    )
    (comp (ref "D4")
      (value "~")
      (footprint "StandardCase:DIODE: SMB")
      (fields
        (field (name "MANUFACTURER") "Micro Commercial")
        (field (name "VALUEMANUFACTURERPARTNUMBER") "MURS160T3G, SMB")
        (field (name "VOLTAGE") "600V")
        (field (name "PARTNUMBER") "MURS160T3G")
      )
      (libsource (lib "Diode") (part "Diode_single"))
    )
    (comp (ref "D5")
      (value "~")
      (footprint "StandardCase:DIODE: SMA")
      (fields
        (field (name "MANUFACTURER") "DIODES")
        (field (name "VALUEMANUFACTURERPARTNUMBER") "RS1M, SMA")
        (field (name "VOLTAGE") "1000V")
        (field (name "PARTNUMBER") "RS1M")
      )
      (libsource (lib "Diode") (part "Diode_single"))
    )
    (comp (ref "D6")
      (value "~")
      (footprint "StandardCase:DIODE: SOD123")
      (fields
        (field (name "MANUFACTURER") "DIODES")
        (field (name "VALUEMANUFACTURERPARTNUMBER") "BAV16W@ DIODES, SOD123")
        (field (name "VOLTAGE") "1000V")
        (field (name "PARTNUMBER") "BAV16W")
      )
      (libsource (lib "Diode") (part "Diode_single"))
    )
    (comp (ref "D7")
      (value "~")
      (footprint "StandardCase:DIODE: SOD123")
      (fields
        (field (name "MANUFACTURER") "DIODES")
        (field (name "VALUEMANUFACTURERPARTNUMBER") "BAV16W@ DIODES, SOD123")
        (field (name "VOLTAGE") "1000V")
        (field (name "PARTNUMBER") "BAV16W")
      )
      (libsource (lib "Diode") (part "Diode_single"))
    )
    (comp (ref "D8")
      (value "~")
      (footprint "StandardCase:DIODE: SMB")
      (fields
        (field (name "MANUFACTURER") "Micro Commercial")
        (field (name "VALUEMANUFACTURERPARTNUMBER") "MURS160T3G, SMB")
        (field (name "VOLTAGE") "600V")
        (field (name "PARTNUMBER") "MURS160T3G")
      )
      (libsource (lib "Diode") (part "Diode_single"))
    )
    (comp (ref "D9")
      (value "~")
      (footprint "StandardCase:SOT23")
      (fields
        (field (name "MANUFACTURER") "Diodes Incorporated")
        (field (name "VALUEMANUFACTURERPARTNUMBER") "BAS40-04, SOT23-3")
        (field (name "VOLTAGE") "40V")
        (field (name "PARTNUMBER") "BAS40-04")
      )
      (libsource (lib "Diode") (part "Schottky_array"))
    )
    (comp (ref "D10")
      (value "~")
      (footprint "StandardCase:SOT23")
      (fields
        (field (name "MANUFACTURER") "Diodes Incorporated")
        (field (name "VALUEMANUFACTURERPARTNUMBER") "BAS40-04, SOT23-3")
        (field (name "VOLTAGE") "40V")
        (field (name "PARTNUMBER") "BAS40-04")
      )
      (libsource (lib "Diode") (part "Schottky_array"))
    )
    (comp (ref "D11")
      (value "~")
      (footprint "StandardCase:DIODE: SOD123")
      (fields
        (field (name "MANUFACTURER") "DIODES")
        (field (name "VALUEMANUFACTURERPARTNUMBER") "BAV16W@ DIODES, SOD123")
        (field (name "VOLTAGE") "1000V")
        (field (name "PARTNUMBER") "BAV16W")
      )
      (libsource (lib "Diode") (part "Diode_single"))
    )
    (comp (ref "D12")
      (value "~")
      (footprint "StandardCase:DIODE: SOD123")
      (fields
        (field (name "MANUFACTURER") "DIODES")
        (field (name "VALUEMANUFACTURERPARTNUMBER") "BAV16W@ DIODES, SOD123")
        (field (name "VOLTAGE") "1000V")
        (field (name "PARTNUMBER") "BAV16W")
      )
      (libsource (lib "Diode") (part "Diode_single"))
    )
    (comp (ref "D13")
      (value "~")
      (footprint "StandardCase:DIODE: SOD123")
      (fields
        (field (name "MANUFACTURER") "DIODES")
        (field (name "VALUEMANUFACTURERPARTNUMBER") "BAV16W@ DIODES, SOD123")
        (field (name "VOLTAGE") "1000V")
        (field (name "PARTNUMBER") "BAV16W")
      )
      (libsource (lib "Diode") (part "Diode_single"))
    )
    (comp (ref "D14")
      (value "~")
      (footprint "StandardCase:DIODE: SOD123")
      (fields
        (field (name "MANUFACTURER") "DIODES")
        (field (name "VALUEMANUFACTURERPARTNUMBER") "BAV16W@ DIODES, SOD123")
        (field (name "VOLTAGE") "1000V")
        (field (name "PARTNUMBER") "BAV16W")
      )
      (libsource (lib "Diode") (part "Diode_single"))
    )
    (comp (ref "D15")
      (value "~")
      (footprint "StandardCase:DIODE: SMA")
      (fields
        (field (name "MANUFACTURER") "Diodes Incorporated")
        (field (name "VALUEMANUFACTURERPARTNUMBER") "1SMA5917B, SMA")
        (field (name "VOLTAGE") "5.1V")
        (field (name "PARTNUMBER") "1SMA5917B")
      )
      (libsource (lib "Diode") (part "Zener_single"))
    )
    (comp (ref "D16")
      (value "~")
      (footprint "StandardCase:DIODE: SOD123")
      (fields
        (field (name "MANUFACTURER") "DIODES")
        (field (name "VALUEMANUFACTURERPARTNUMBER") "BAV16W@ DIODES, SOD123")
        (field (name "VOLTAGE") "1000V")
        (field (name "PARTNUMBER") "BAV16W")
      )
      (libsource (lib "Diode") (part "Diode_single"))
    )
    (comp (ref "D17")
      (value "~")
      (footprint "StandardCase:DIODE: SMA")
      (fields
        (field (name "MANUFACTURER") "Diodes Incorporated")
        (field (name "VALUEMANUFACTURERPARTNUMBER") "SMAJ11A, SMA")
        (field (name "VOLTAGE") "11V")
        (field (name "PARTNUMBER") "SMAJ11A")
      )
      (libsource (lib "Diode") (part "Zener_single"))
    )
    (comp (ref "D18")
      (value "~")
      (footprint "StandardCase:DIODE: SMA")
      (fields
        (field (name "MANUFACTURER") "DIODES")
        (field (name "VALUEMANUFACTURERPARTNUMBER") "RS1M, SMA")
        (field (name "VOLTAGE") "1000V")
        (field (name "PARTNUMBER") "RS1M")
      )
      (libsource (lib "Diode") (part "Diode_single"))
    )
    (comp (ref "D19")
      (value "~")
      (footprint "StandardCase:DIODE: SOD123")
      (fields
        (field (name "MANUFACTURER") "DIODES")
        (field (name "VALUEMANUFACTURERPARTNUMBER") "BAV16W@ DIODES, SOD123")
        (field (name "VOLTAGE") "1000V")
        (field (name "PARTNUMBER") "BAV16W")
      )
      (libsource (lib "Diode") (part "Diode_single"))
    )
    (comp (ref "D20")
      (value "~")
      (footprint "StandardCase:DIODE: SOD123")
      (fields
        (field (name "MANUFACTURER") "DIODES")
        (field (name "VALUEMANUFACTURERPARTNUMBER") "BAV16W@ DIODES, SOD123")
        (field (name "VOLTAGE") "1000V")
        (field (name "PARTNUMBER") "BAV16W")
      )
      (libsource (lib "Diode") (part "Diode_single"))
    )
    (comp (ref "D21")
      (value "~")
      (footprint "StandardCase:SOT23")
      (fields
        (field (name "MANUFACTURER") "Diodes Incorporated")
        (field (name "VALUEMANUFACTURERPARTNUMBER") "BAS40-04, SOT23-3")
        (field (name "VOLTAGE") "40V")
        (field (name "PARTNUMBER") "BAS40-04")
      )
      (libsource (lib "Diode") (part "Schottky_array"))
    )
    (comp (ref "D22")
      (value "~")
      (footprint "StandardCase:SOT23")
      (fields
        (field (name "MANUFACTURER") "Diodes Incorporated")
        (field (name "VALUEMANUFACTURERPARTNUMBER") "BAS40-04, SOT23-3")
        (field (name "VOLTAGE") "40V")
        (field (name "PARTNUMBER") "BAS40-04")
      )
      (libsource (lib "Diode") (part "Schottky_array"))
    )
    (comp (ref "D23")
      (value "~")
      (footprint "StandardCase:SOT23")
      (fields
        (field (name "MANUFACTURER") "Diodes Incorporated")
        (field (name "VALUEMANUFACTURERPARTNUMBER") "BAS40-04, SOT23-3")
        (field (name "VOLTAGE") "40V")
        (field (name "PARTNUMBER") "BAS40-04")
      )
      (libsource (lib "Diode") (part "Schottky_array"))
    )
    (comp (ref "D24")
      (value "~")
      (footprint "StandardCase:SOT23")
      (fields
        (field (name "MANUFACTURER") "Diodes Incorporated")
        (field (name "VALUEMANUFACTURERPARTNUMBER") "BAS40-04, SOT23-3")
        (field (name "VOLTAGE") "40V")
        (field (name "PARTNUMBER") "BAS40-04")
      )
      (libsource (lib "Diode") (part "Schottky_array"))
    )
    (comp (ref "D25")
      (value "~")
      (footprint "StandardCase:SOT23")
      (fields
        (field (name "MANUFACTURER") "Diodes Incorporated")
        (field (name "VALUEMANUFACTURERPARTNUMBER") "BAS40-04, SOT23-3")
        (field (name "VOLTAGE") "40V")
        (field (name "PARTNUMBER") "BAS40-04")
      )
      (libsource (lib "Diode") (part "Schottky_array"))
    )
    (comp (ref "D26")
      (value "~")
      (footprint "StandardCase:SOT23")
      (fields
        (field (name "MANUFACTURER") "Diodes Incorporated")
        (field (name "VALUEMANUFACTURERPARTNUMBER") "BAS40-04, SOT23-3")
        (field (name "VOLTAGE") "40V")
        (field (name "PARTNUMBER") "BAS40-04")
      )
      (libsource (lib "Diode") (part "Schottky_array"))
    )
    (comp (ref "D27")
      (value "~")
      (footprint "StandardCase:SOT23")
      (fields
        (field (name "MANUFACTURER") "Diodes Incorporated")
        (field (name "VALUEMANUFACTURERPARTNUMBER") "BAS40-04, SOT23-3")
        (field (name "VOLTAGE") "40V")
        (field (name "PARTNUMBER") "BAS40-04")
      )
      (libsource (lib "Diode") (part "Schottky_array"))
    )
    (comp (ref "D28")
      (value "~")
      (footprint "StandardCase:SOT23")
      (fields
        (field (name "MANUFACTURER") "Diodes Incorporated")
        (field (name "VALUEMANUFACTURERPARTNUMBER") "BAS40-04, SOT23-3")
        (field (name "VOLTAGE") "40V")
        (field (name "PARTNUMBER") "BAS40-04")
      )
      (libsource (lib "Diode") (part "Schottky_array"))
    )
    (comp (ref "D29")
      (value "~")
      (footprint "StandardCase:DIODE: SMC")
      (fields
        (field (name "MANUFACTURER") "Diodes Incorporated")
        (field (name "VALUEMANUFACTURERPARTNUMBER") "STPS3L40, SMC")
        (field (name "VOLTAGE") "80V")
        (field (name "PARTNUMBER") "STPS3L40")
      )
      (libsource (lib "Diode") (part "Schottky_single"))
    )
    (comp (ref "L1")
      (value "10μH")
      (footprint "PcbLib1:MSS1038T")
      (fields
        (field (name "MANUFACTURER") "Sumida")
        (field (name "PARTNUMBER") "MSS1038T")
        (field (name "VALUEMANUFACTURERPARTNUMBER") "MSS1038T, 10μH")
      )
      (libsource (lib "Inductor") (part "Inductor_CD43"))
    )
    (comp (ref "LED1")
      (value "~")
      (footprint "StandardCase:LED: 1206G")
      (fields
        (field (name "VALUEMANUFACTURERPARTNUMBER") "LED, RED, 1206")
        (field (name "PARTNUMBER") "BL-LS1206HC")
        (field (name "COLOR") "RED")
      )
      (libsource (lib "Diode") (part "LED_single"))
    )
    (comp (ref "LED2")
      (value "~")
      (footprint "StandardCase:LED: 1206G")
      (fields
        (field (name "VALUEMANUFACTURERPARTNUMBER") "LED, YELLOW, 1206")
        (field (name "PARTNUMBER") "BL-LS1206HC")
        (field (name "COLOR") "YELLOW")
      )
      (libsource (lib "Diode") (part "LED_single"))
    )
    (comp (ref "LED3")
      (value "~")
      (footprint "StandardCase:LED: 1206G")
      (fields
        (field (name "VALUEMANUFACTURERPARTNUMBER") "LED, YELLOW, 1206")
        (field (name "PARTNUMBER") "BL-LS1206HC")
        (field (name "COLOR") "YELLOW")
      )
      (libsource (lib "Diode") (part "LED_single"))
    )
    (comp (ref "LED4")
      (value "~")
      (footprint "StandardCase:LED: 1206G")
      (fields (field (name "VALUEMANUFACTURERPARTNUMBER") "LED, GREEN, 1206") (field (name "COLOR") "GREEN"))
      (libsource (lib "Diode") (part "LED_single"))
    )
    (comp (ref "LED5")
      (value "~")
      (footprint "StandardCase:LED: 1206R")
      (fields (field (name "VALUEMANUFACTURERPARTNUMBER") "LED, GREEN, 1206") (field (name "COLOR") "GREEN"))
      (libsource (lib "Diode") (part "LED_single"))
    )
    (comp (ref "LED6")
      (value "~")
      (footprint "StandardCase:LED: 1206G")
      (fields
        (field (name "VALUEMANUFACTURERPARTNUMBER") "LED, GREEN, 1206")
        (field (name "PARTNUMBER") "BL-LS1206HC")
        (field (name "COLOR") "GREEN")
      )
      (libsource (lib "Diode") (part "LED_single"))
    )
    (comp (ref "PGM")
      (value "~")
      (footprint "CustomCase:CON: PLS-6")
      (fields
        (field (name "MANUFACTURER") "Connfly")
        (field (name "VALUEMANUFACTURERPARTNUMBER") "PLS-6, 6pin")
        (field (name "PARTNUMBER") "PLS-6")
        (field (name "COMMENTTEXT") "\"Разъем\"")
      )
      (libsource (lib "Connector") (part "PLS-6"))
    )
    (comp (ref "Q5")
      (value "~")
      (footprint "StandardCase:SOT23")
      (fields
        (field (name "MANUFACTURER") "ON Semiconductor")
        (field (name "VALUEMANUFACTURERPARTNUMBER") "BC846, SOT-23")
        (field (name "PARTNUMBER") "BC846")
      )
      (libsource (lib "Transistor") (part "BJT_NPN_132"))
    )
    (comp (ref "Q7")
      (value "~")
      (footprint "StandardCase:SOT23")
      (fields
        (field (name "MANUFACTURER") "ON Semiconductor")
        (field (name "VALUEMANUFACTURERPARTNUMBER") "BC846, SOT-23")
        (field (name "PARTNUMBER") "BC846")
      )
      (libsource (lib "Transistor") (part "BJT_NPN_132"))
    )
    (comp (ref "Q8")
      (value "~")
      (footprint "StandardCase:SOT23")
      (fields
        (field (name "MANUFACTURER") "Infineon Technologies")
        (field (name "VALUEMANUFACTURERPARTNUMBER") "ZXMN6A07F, SOT23-3")
        (field (name "PARTNUMBER") "ZXMN6A07F")
      )
      (libsource (lib "Transistor") (part "MOSFET_N_132"))
    )
    (comp (ref "Q9")
      (value "~")
      (footprint "StandardCase:SOT23")
      (fields
        (field (name "MANUFACTURER") "ON Semiconductor")
        (field (name "VALUEMANUFACTURERPARTNUMBER") "BC860, SOT-23")
        (field (name "PARTNUMBER") "BC860")
      )
      (libsource (lib "Transistor") (part "BJT_PNP_123"))
    )
    (comp (ref "Q10")
      (value "~")
      (footprint "StandardCase:SOT23")
      (fields
        (field (name "MANUFACTURER") "ON Semiconductor")
        (field (name "VALUEMANUFACTURERPARTNUMBER") "PMST3904, SOT-23")
        (field (name "PARTNUMBER") "PMST3904")
      )
      (libsource (lib "Transistor") (part "BJT_NPN_132"))
    )
    (comp (ref "Q11")
      (value "~")
      (footprint "StandardCase:SOT23")
      (fields
        (field (name "MANUFACTURER") "ON Semiconductor")
        (field (name "VALUEMANUFACTURERPARTNUMBER") "BC846, SOT-23")
        (field (name "PARTNUMBER") "BC846")
      )
      (libsource (lib "Transistor") (part "BJT_NPN_132"))
    )
    (comp (ref "Q12")
      (value "~")
      (footprint "StandardCase:SOT23")
      (fields
        (field (name "MANUFACTURER") "ON Semiconductor")
        (field (name "VALUEMANUFACTURERPARTNUMBER") "BC860, SOT-23")
        (field (name "PARTNUMBER") "BC860")
      )
      (libsource (lib "Transistor") (part "BJT_PNP_123"))
    )
    (comp (ref "Q14")
      (value "~")
      (footprint "StandardCase:SOT23")
      (fields
        (field (name "MANUFACTURER") "ON Semiconductor")
        (field (name "VALUEMANUFACTURERPARTNUMBER") "BC846, SOT-23")
        (field (name "PARTNUMBER") "BC846")
      )
      (libsource (lib "Transistor") (part "BJT_NPN_132"))
    )
    (comp (ref "Q15")
      (value "~")
      (footprint "StandardCase:SOT23")
      (fields
        (field (name "MANUFACTURER") "ON Semiconductor")
        (field (name "VALUEMANUFACTURERPARTNUMBER") "BC846, SOT-23")
        (field (name "PARTNUMBER") "BC846")
      )
      (libsource (lib "Transistor") (part "BJT_NPN_132"))
    )
    (comp (ref "Q16")
      (value "~")
      (footprint "StandardCase:SOT23")
      (fields
        (field (name "MANUFACTURER") "ON Semiconductor")
        (field (name "VALUEMANUFACTURERPARTNUMBER") "BC860, SOT-23")
        (field (name "PARTNUMBER") "BC860")
      )
      (libsource (lib "Transistor") (part "BJT_PNP_123"))
    )
    (comp (ref "R1")
      (value "1K")
      (footprint "StandardCase:RES: 1206")
      (fields
        (field (name "MANUFACTURER") "Yageo")
        (field (name "PARTNUMBER") "RC1206JR-07100RL")
        (field (name "VALUEMANUFACTURERPARTNUMBER") "Resistor, 1K, 1206")
      )
      (libsource (lib "") (part "Resistor_1206_1"))
    )
    (comp (ref "R2")
      (value "1K")
      (footprint "StandardCase:RES: 1206")
      (fields
        (field (name "MANUFACTURER") "Yageo")
        (field (name "PARTNUMBER") "RC1206JR-07100RL")
        (field (name "VALUEMANUFACTURERPARTNUMBER") "Resistor, 1K, 1206")
      )
      (libsource (lib "") (part "Resistor_1206_1"))
    )
    (comp (ref "R3")
      (value "270R")
      (footprint "StandardCase:RES: 1206")
      (fields
        (field (name "MANUFACTURER") "Yageo")
        (field (name "PARTNUMBER") "RC1206JR-07100RL")
        (field (name "VALUEMANUFACTURERPARTNUMBER") "Resistor, 270R, 1206")
      )
      (libsource (lib "") (part "Resistor_1206_2"))
    )
    (comp (ref "R4")
      (value "100R")
      (footprint "StandardCase:RES: 1206")
      (fields
        (field (name "MANUFACTURER") "Yageo")
        (field (name "PARTNUMBER") "RC1206JR-07100RL")
        (field (name "VALUEMANUFACTURERPARTNUMBER") "Resistor, 100R, 1206")
      )
      (libsource (lib "") (part "Resistor_1206_2"))
    )
    (comp (ref "R5")
      (value "100R")
      (footprint "StandardCase:RES: 1206")
      (fields
        (field (name "MANUFACTURER") "Yageo")
        (field (name "PARTNUMBER") "RC1206JR-07100RL")
        (field (name "VALUEMANUFACTURERPARTNUMBER") "Resistor, 100R, 1206")
      )
      (libsource (lib "") (part "Resistor_1206_2"))
    )
    (comp (ref "R6")
      (value "20K")
      (footprint "StandardCase:RES: 1206")
      (fields
        (field (name "MANUFACTURER") "Yageo")
        (field (name "PARTNUMBER") "RC1206JR-07100RL")
        (field (name "VALUEMANUFACTURERPARTNUMBER") "Resistor, 20K, 1206")
      )
      (libsource (lib "Resistor") (part "Resistor_1206"))
    )
    (comp (ref "R7")
      (value "10K")
      (footprint "StandardCase:RES: 1206")
      (fields
        (field (name "MANUFACTURER") "Yageo")
        (field (name "PARTNUMBER") "RC1206JR-07100RL")
        (field (name "VALUEMANUFACTURERPARTNUMBER") "Resistor, 10K, 1206")
      )
      (libsource (lib "Resistor") (part "Resistor_1206"))
    )
    (comp (ref "R8")
      (value "680R")
      (footprint "StandardCase:RES: 1206")
      (fields
        (field (name "MANUFACTURER") "Yageo")
        (field (name "PARTNUMBER") "RC1206JR-07100RL")
        (field (name "VALUEMANUFACTURERPARTNUMBER") "Resistor, 680R, 1206")
        (field (name "TOLERANCE") "±5%")
      )
      (libsource (lib "") (part "Resistor_1206_1"))
    )
    (comp (ref "R9")
      (value "100R")
      (footprint "StandardCase:RES: 1206")
      (fields
        (field (name "MANUFACTURER") "Yageo")
        (field (name "PARTNUMBER") "RC1206JR-07100RL")
        (field (name "VALUEMANUFACTURERPARTNUMBER") "Resistor, 100R, 1206")
      )
      (libsource (lib "") (part "Resistor_1206_2"))
    )
    (comp (ref "R10")
      (value "26.7R")
      (footprint "StandardCase:RES: 1206")
      (fields
        (field (name "MANUFACTURER") "Yageo")
        (field (name "PARTNUMBER") "RC1206JR-07100RL")
        (field (name "VALUEMANUFACTURERPARTNUMBER") "Resistor, 26.7R, 1206")
      )
      (libsource (lib "Resistor") (part "Resistor_1206"))
    )
    (comp (ref "R11")
      (value "26.7R")
      (footprint "StandardCase:RES: 1206")
      (fields
        (field (name "MANUFACTURER") "Yageo")
        (field (name "PARTNUMBER") "RC1206JR-07100RL")
        (field (name "VALUEMANUFACTURERPARTNUMBER") "Resistor, 26.7R, 1206")
      )
      (libsource (lib "Resistor") (part "Resistor_1206"))
    )
    (comp (ref "R12")
      (value "26.7R")
      (footprint "StandardCase:RES: 1206")
      (fields
        (field (name "MANUFACTURER") "Yageo")
        (field (name "PARTNUMBER") "RC1206JR-07100RL")
        (field (name "VALUEMANUFACTURERPARTNUMBER") "Resistor, 26.7R, 1206")
      )
      (libsource (lib "Resistor") (part "Resistor_1206"))
    )
    (comp (ref "R13")
      (value "26.7R")
      (footprint "StandardCase:RES: 1206")
      (fields
        (field (name "MANUFACTURER") "Yageo")
        (field (name "PARTNUMBER") "RC1206JR-07100RL")
        (field (name "VALUEMANUFACTURERPARTNUMBER") "Resistor, 26.7R, 1206")
      )
      (libsource (lib "Resistor") (part "Resistor_1206"))
    )
    (comp (ref "R14")
      (value "20K")
      (footprint "StandardCase:RES: 1206")
      (fields
        (field (name "MANUFACTURER") "Yageo")
        (field (name "PARTNUMBER") "RC1206JR-07100RL")
        (field (name "VALUEMANUFACTURERPARTNUMBER") "Resistor, 20K, 1206")
      )
      (libsource (lib "") (part "Resistor_1206_2"))
    )
    (comp (ref "R15")
      (value "10K")
      (footprint "StandardCase:RES: 1206")
      (fields
        (field (name "MANUFACTURER") "Yageo")
        (field (name "PARTNUMBER") "RC1206JR-07100RL")
        (field (name "VALUEMANUFACTURERPARTNUMBER") "Resistor, 10K, 1206")
      )
      (libsource (lib "") (part "Resistor_1206_2"))
    )
    (comp (ref "R16")
      (value "10K")
      (footprint "StandardCase:RES: 1206")
      (fields
        (field (name "MANUFACTURER") "Yageo")
        (field (name "PARTNUMBER") "RC1206JR-07100RL")
        (field (name "VALUEMANUFACTURERPARTNUMBER") "Resistor, 10K, 1206")
      )
      (libsource (lib "Resistor") (part "Resistor_1206"))
    )
    (comp (ref "R17")
      (value "20K")
      (footprint "StandardCase:RES: 1206")
      (fields
        (field (name "MANUFACTURER") "Yageo")
        (field (name "PARTNUMBER") "RC1206JR-07100RL")
        (field (name "VALUEMANUFACTURERPARTNUMBER") "Resistor, 20K, 1206")
      )
      (libsource (lib "Resistor") (part "Resistor_1206"))
    )
    (comp (ref "R18")
      (value "10K")
      (footprint "StandardCase:RES: 1206")
      (fields
        (field (name "MANUFACTURER") "Yageo")
        (field (name "PARTNUMBER") "RC1206JR-07100RL")
        (field (name "VALUEMANUFACTURERPARTNUMBER") "Resistor, 10K, 1206")
      )
      (libsource (lib "Resistor") (part "Resistor_1206"))
    )
    (comp (ref "R19")
      (value "100K")
      (footprint "StandardCase:RES: 1206")
      (fields
        (field (name "MANUFACTURER") "Yageo")
        (field (name "PARTNUMBER") "RC1206JR-07100RL")
        (field (name "VALUEMANUFACTURERPARTNUMBER") "Resistor, 100K, 1206")
      )
      (libsource (lib "Resistor") (part "Resistor_1206"))
    )
    (comp (ref "R20")
      (value "10K")
      (footprint "StandardCase:RES: 1206")
      (fields
        (field (name "MANUFACTURER") "Yageo")
        (field (name "PARTNUMBER") "RC1206JR-07100RL")
        (field (name "VALUEMANUFACTURERPARTNUMBER") "Resistor, 10K, 1206")
      )
      (libsource (lib "Resistor") (part "Resistor_1206"))
    )
    (comp (ref "R21")
      (value "10K")
      (footprint "StandardCase:RES: 1206")
      (fields
        (field (name "MANUFACTURER") "Yageo")
        (field (name "PARTNUMBER") "RC1206JR-07100RL")
        (field (name "VALUEMANUFACTURERPARTNUMBER") "Resistor, 10K, 1206")
      )
      (libsource (lib "Resistor") (part "Resistor_1206"))
    )
    (comp (ref "R22")
      (value "10K")
      (footprint "StandardCase:RES: 1206")
      (fields
        (field (name "MANUFACTURER") "Yageo")
        (field (name "PARTNUMBER") "RC1206JR-07100RL")
        (field (name "VALUEMANUFACTURERPARTNUMBER") "Resistor, 10K, 1206")
      )
      (libsource (lib "Resistor") (part "Resistor_1206"))
    )
    (comp (ref "R23")
      (value "10K")
      (footprint "StandardCase:RES: 1206")
      (fields
        (field (name "MANUFACTURER") "Yageo")
        (field (name "PARTNUMBER") "RC1206JR-07100RL")
        (field (name "VALUEMANUFACTURERPARTNUMBER") "Resistor, 10K, 1206")
      )
      (libsource (lib "") (part "Resistor_1206_2"))
    )
    (comp (ref "R24")
      (value "10K")
      (footprint "StandardCase:RES: 1206")
      (fields
        (field (name "MANUFACTURER") "Yageo")
        (field (name "PARTNUMBER") "RC1206JR-07100RL")
        (field (name "VALUEMANUFACTURERPARTNUMBER") "Resistor, 10K, 1206")
      )
      (libsource (lib "Resistor") (part "Resistor_1206"))
    )
    (comp (ref "R25")
      (value "100K")
      (footprint "StandardCase:RES: 1206")
      (fields
        (field (name "MANUFACTURER") "Yageo")
        (field (name "PARTNUMBER") "RC1206JR-07100RL")
        (field (name "VALUEMANUFACTURERPARTNUMBER") "Resistor, 100K, 1206")
      )
      (libsource (lib "") (part "Resistor_1206_2"))
    )
    (comp (ref "R26")
      (value "20K")
      (footprint "StandardCase:RES: 1206")
      (fields
        (field (name "MANUFACTURER") "Yageo")
        (field (name "PARTNUMBER") "RC1206JR-07100RL")
        (field (name "VALUEMANUFACTURERPARTNUMBER") "Resistor, 20K, 1206")
      )
      (libsource (lib "") (part "Resistor_1206_3"))
    )
    (comp (ref "R27")
      (value "10M")
      (footprint "PcbLib1:CFR-50")
      (fields
        (field (name "MANUFACTURER") "Yageo")
        (field (name "PARTNUMBER") "RC1206JR-07100RL")
        (field (name "VALUEMANUFACTURERPARTNUMBER") "Resistor, 10M, CFR-50")
        (field (name "TOLERANCE") "±1%")
      )
      (libsource (lib "") (part "Resistor_1206_1"))
    )
    (comp (ref "R28")
      (value "10M")
      (footprint "PcbLib1:CFR-50")
      (fields
        (field (name "MANUFACTURER") "Yageo")
        (field (name "PARTNUMBER") "RC1206JR-07100RL")
        (field (name "VALUEMANUFACTURERPARTNUMBER") "Resistor, 10M, CFR-50")
        (field (name "TOLERANCE") "±1%")
      )
      (libsource (lib "") (part "Resistor_1206_2"))
    )
    (comp (ref "R29")
      (value "499K")
      (footprint "StandardCase:RES: 1206")
      (fields
        (field (name "MANUFACTURER") "Yageo")
        (field (name "PARTNUMBER") "RC1206JR-07100RL")
        (field (name "VALUEMANUFACTURERPARTNUMBER") "Resistor, 499K, 1206")
        (field (name "TOLERANCE") "±1%")
      )
      (libsource (lib "Resistor") (part "Resistor_1206"))
    )
    (comp (ref "R30")
      (value "499K")
      (footprint "StandardCase:RES: 1206")
      (fields
        (field (name "MANUFACTURER") "Yageo")
        (field (name "PARTNUMBER") "RC1206JR-07100RL")
        (field (name "VALUEMANUFACTURERPARTNUMBER") "Resistor, 499K, 1206")
        (field (name "TOLERANCE") "±1%")
      )
      (libsource (lib "") (part "Resistor_1206_1"))
    )
    (comp (ref "R31")
      (value "47R")
      (footprint "StandardCase:RES: 1206")
      (fields
        (field (name "MANUFACTURER") "Yageo")
        (field (name "PARTNUMBER") "RC1206JR-07100RL")
        (field (name "VALUEMANUFACTURERPARTNUMBER") "Resistor, 47R, 1206")
      )
      (libsource (lib "") (part "Resistor_1206_1"))
    )
    (comp (ref "R32")
      (value "47R")
      (footprint "StandardCase:RES: 1206")
      (fields
        (field (name "MANUFACTURER") "Yageo")
        (field (name "PARTNUMBER") "RC1206JR-07100RL")
        (field (name "VALUEMANUFACTURERPARTNUMBER") "Resistor, 47R, 1206")
      )
      (libsource (lib "") (part "Resistor_1206_1"))
    )
    (comp (ref "R33")
      (value "10K")
      (footprint "StandardCase:RES: 1206")
      (fields
        (field (name "MANUFACTURER") "Yageo")
        (field (name "PARTNUMBER") "RC1206JR-07100RL")
        (field (name "VALUEMANUFACTURERPARTNUMBER") "Resistor, 10K, 1206")
      )
      (libsource (lib "Resistor") (part "Resistor_1206"))
    )
    (comp (ref "R34")
      (value "1M")
      (footprint "StandardCase:RES: 1206")
      (fields
        (field (name "MANUFACTURER") "Yageo")
        (field (name "PARTNUMBER") "RC1206JR-07100RL")
        (field (name "VALUEMANUFACTURERPARTNUMBER") "Resistor, 1M, 1206")
      )
      (libsource (lib "Resistor") (part "Resistor_1206"))
    )
    (comp (ref "R35")
      (value "2K")
      (footprint "StandardCase:RES: 1206")
      (fields
        (field (name "MANUFACTURER") "Yageo")
        (field (name "PARTNUMBER") "RC1206JR-07100RL")
        (field (name "VALUEMANUFACTURERPARTNUMBER") "Resistor, 2K, 1206")
      )
      (libsource (lib "") (part "Resistor_1206_2"))
    )
    (comp (ref "R36")
      (value "2K")
      (footprint "StandardCase:RES: 1206")
      (fields
        (field (name "MANUFACTURER") "Yageo")
        (field (name "PARTNUMBER") "RC1206JR-07100RL")
        (field (name "VALUEMANUFACTURERPARTNUMBER") "Resistor, 2K, 1206")
      )
      (libsource (lib "Resistor") (part "Resistor_1206"))
    )
    (comp (ref "R37")
      (value "4.99K")
      (footprint "StandardCase:RES: 1206")
      (fields
        (field (name "MANUFACTURER") "Yageo")
        (field (name "PARTNUMBER") "RC1206JR-07100RL")
        (field (name "VALUEMANUFACTURERPARTNUMBER") "Resistor, 4.99K, 1206")
      )
      (libsource (lib "") (part "Resistor_1206_1"))
    )
    (comp (ref "R38")
      (value "20K")
      (footprint "StandardCase:RES: 1206")
      (fields
        (field (name "MANUFACTURER") "Yageo")
        (field (name "PARTNUMBER") "RC1206JR-07100RL")
        (field (name "VALUEMANUFACTURERPARTNUMBER") "Resistor, 20K, 1206")
      )
      (libsource (lib "Resistor") (part "Resistor_1206"))
    )
    (comp (ref "R39")
      (value "49.9K")
      (footprint "StandardCase:RES: 1206")
      (fields
        (field (name "MANUFACTURER") "Yageo")
        (field (name "PARTNUMBER") "RC1206JR-07100RL")
        (field (name "VALUEMANUFACTURERPARTNUMBER") "Resistor, 49.9K, 1206")
      )
      (libsource (lib "") (part "Resistor_1206_3"))
    )
    (comp (ref "R40")
      (value "33.2K")
      (footprint "StandardCase:RES: 1206")
      (fields
        (field (name "MANUFACTURER") "Yageo")
        (field (name "PARTNUMBER") "RC1206JR-07100RL")
        (field (name "VALUEMANUFACTURERPARTNUMBER") "Resistor, 33.2K, 1206")
      )
      (libsource (lib "") (part "Resistor_1206_1"))
    )
    (comp (ref "R41")
      (value "100K")
      (footprint "StandardCase:RES: 1206")
      (fields
        (field (name "MANUFACTURER") "Yageo")
        (field (name "PARTNUMBER") "RC1206JR-07100RL")
        (field (name "VALUEMANUFACTURERPARTNUMBER") "Resistor, 100K, 1206")
      )
      (libsource (lib "Resistor") (part "Resistor_1206"))
    )
    (comp (ref "R42")
      (value "180K")
      (footprint "StandardCase:RES: 1206")
      (fields
        (field (name "MANUFACTURER") "Yageo")
        (field (name "PARTNUMBER") "RC1206JR-07100RL")
        (field (name "VALUEMANUFACTURERPARTNUMBER") "Resistor, 180K, 1206")
      )
      (libsource (lib "Resistor") (part "Resistor_1206"))
    )
    (comp (ref "R43")
      (value "100R")
      (footprint "StandardCase:RES: 1206")
      (fields
        (field (name "MANUFACTURER") "Yageo")
        (field (name "PARTNUMBER") "RC1206JR-07100RL")
        (field (name "VALUEMANUFACTURERPARTNUMBER") "Resistor, 100R, 1206")
      )
      (libsource (lib "") (part "Resistor_1206_1"))
    )
    (comp (ref "R44")
      (value "20K")
      (footprint "StandardCase:RES: 1206")
      (fields
        (field (name "MANUFACTURER") "Yageo")
        (field (name "PARTNUMBER") "RC1206JR-07100RL")
        (field (name "VALUEMANUFACTURERPARTNUMBER") "Resistor, 20K, 1206")
      )
      (libsource (lib "Resistor") (part "Resistor_1206"))
    )
    (comp (ref "R45")
      (value "10K")
      (footprint "StandardCase:RES: 1206")
      (fields
        (field (name "MANUFACTURER") "Yageo")
        (field (name "PARTNUMBER") "RC1206JR-07100RL")
        (field (name "VALUEMANUFACTURERPARTNUMBER") "Resistor, 10K, 1206")
      )
      (libsource (lib "Resistor") (part "Resistor_1206"))
    )
    (comp (ref "R46")
      (value "10K")
      (footprint "StandardCase:RES: 1206")
      (fields
        (field (name "MANUFACTURER") "Yageo")
        (field (name "PARTNUMBER") "RC1206JR-07100RL")
        (field (name "VALUEMANUFACTURERPARTNUMBER") "Resistor, 10K, 1206")
      )
      (libsource (lib "") (part "Resistor_1206_2"))
    )
    (comp (ref "R47")
      (value "10K")
      (footprint "StandardCase:RES: 1206")
      (fields
        (field (name "MANUFACTURER") "Yageo")
        (field (name "PARTNUMBER") "RC1206JR-07100RL")
        (field (name "VALUEMANUFACTURERPARTNUMBER") "Resistor, 10K, 1206")
      )
      (libsource (lib "") (part "Resistor_1206_2"))
    )
    (comp (ref "R48")
      (value "10K")
      (footprint "StandardCase:RES: 1206")
      (fields
        (field (name "MANUFACTURER") "Yageo")
        (field (name "PARTNUMBER") "RC1206JR-07100RL")
        (field (name "VALUEMANUFACTURERPARTNUMBER") "Resistor, 10K, 1206")
      )
      (libsource (lib "") (part "Resistor_1206_1"))
    )
    (comp (ref "R49")
      (value "100K")
      (footprint "StandardCase:RES: 1206")
      (fields
        (field (name "MANUFACTURER") "Yageo")
        (field (name "PARTNUMBER") "RC1206JR-07100RL")
        (field (name "VALUEMANUFACTURERPARTNUMBER") "Resistor, 100K, 1206")
      )
      (libsource (lib "") (part "Resistor_1206_1"))
    )
    (comp (ref "R50")
      (value "10K")
      (footprint "StandardCase:RES: 1206")
      (fields
        (field (name "MANUFACTURER") "Yageo")
        (field (name "PARTNUMBER") "RC1206JR-07100RL")
        (field (name "VALUEMANUFACTURERPARTNUMBER") "Resistor, 10K, 1206")
      )
      (libsource (lib "Resistor") (part "Resistor_1206"))
    )
    (comp (ref "R51")
      (value "10K")
      (footprint "StandardCase:RES: 1206")
      (fields
        (field (name "MANUFACTURER") "Yageo")
        (field (name "PARTNUMBER") "RC1206JR-07100RL")
        (field (name "VALUEMANUFACTURERPARTNUMBER") "Resistor, 10K, 1206")
      )
      (libsource (lib "") (part "Resistor_1206_1"))
    )
    (comp (ref "R52")
      (value "1.5K")
      (footprint "StandardCase:RES: 1206")
      (fields
        (field (name "MANUFACTURER") "Yageo")
        (field (name "PARTNUMBER") "RC1206JR-07100RL")
        (field (name "VALUEMANUFACTURERPARTNUMBER") "Resistor, 1.5K, 1206")
      )
      (libsource (lib "") (part "Resistor_1206_3"))
    )
    (comp (ref "R53")
      (value "330R")
      (footprint "StandardCase:RES: 1206")
      (fields
        (field (name "MANUFACTURER") "Yageo")
        (field (name "PARTNUMBER") "RC1206JR-07100RL")
        (field (name "VALUEMANUFACTURERPARTNUMBER") "Resistor, 330R, 1206")
      )
      (libsource (lib "") (part "Resistor_1206_3"))
    )
    (comp (ref "R54")
      (value "1.1K")
      (footprint "StandardCase:RES: 1206")
      (fields
        (field (name "MANUFACTURER") "Yageo")
        (field (name "PARTNUMBER") "RC1206JR-07100RL")
        (field (name "VALUEMANUFACTURERPARTNUMBER") "Resistor, 1.1K, 1206")
      )
      (libsource (lib "") (part "Resistor_1206_3"))
    )
    (comp (ref "R55")
      (value "100K")
      (footprint "StandardCase:RES: 1206")
      (fields
        (field (name "MANUFACTURER") "Yageo")
        (field (name "PARTNUMBER") "RC1206JR-07100RL")
        (field (name "VALUEMANUFACTURERPARTNUMBER") "Resistor, 100K, 1206")
      )
      (libsource (lib "Resistor") (part "Resistor_1206"))
    )
    (comp (ref "R56")
      (value "10K")
      (footprint "StandardCase:RES: 1206")
      (fields
        (field (name "MANUFACTURER") "Yageo")
        (field (name "PARTNUMBER") "RC1206JR-07100RL")
        (field (name "VALUEMANUFACTURERPARTNUMBER") "Resistor, 10K, 1206")
      )
      (libsource (lib "Resistor") (part "Resistor_1206"))
    )
    (comp (ref "R57*")
      (value "10K")
      (footprint "StandardCase:RES: 1206")
      (fields
        (field (name "MANUFACTURER") "Yageo")
        (field (name "PARTNUMBER") "RC1206JR-07100RL")
        (field (name "VALUEMANUFACTURERPARTNUMBER") "Resistor, 10K, 1206")
      )
      (libsource (lib "Resistor") (part "Resistor_1206"))
    )
    (comp (ref "R58")
      (value "20K")
      (footprint "StandardCase:RES: 1206")
      (fields
        (field (name "MANUFACTURER") "Yageo")
        (field (name "PARTNUMBER") "RC1206JR-07100RL")
        (field (name "VALUEMANUFACTURERPARTNUMBER") "Resistor, 20K, 1206")
      )
      (libsource (lib "Resistor") (part "Resistor_1206"))
    )
    (comp (ref "R59")
      (value "1K")
      (footprint "StandardCase:RES: 1206")
      (fields
        (field (name "MANUFACTURER") "Yageo")
        (field (name "PARTNUMBER") "RC1206JR-07100RL")
        (field (name "VALUEMANUFACTURERPARTNUMBER") "Resistor, 1K, 1206")
      )
      (libsource (lib "Resistor") (part "Resistor_1206"))
    )
    (comp (ref "R60")
      (value "10K")
      (footprint "StandardCase:RES: 1206")
      (fields
        (field (name "MANUFACTURER") "Yageo")
        (field (name "PARTNUMBER") "RC1206JR-07100RL")
        (field (name "VALUEMANUFACTURERPARTNUMBER") "Resistor, 10K, 1206")
      )
      (libsource (lib "") (part "Resistor_1206_2"))
    )
    (comp (ref "R61")
      (value "20K")
      (footprint "StandardCase:RES: 1206")
      (fields
        (field (name "MANUFACTURER") "Yageo")
        (field (name "PARTNUMBER") "RC1206JR-07100RL")
        (field (name "VALUEMANUFACTURERPARTNUMBER") "Resistor, 20K, 1206")
      )
      (libsource (lib "") (part "Resistor_1206_1"))
    )
    (comp (ref "R62")
      (value "33.2K")
      (footprint "StandardCase:RES: 1206")
      (fields
        (field (name "MANUFACTURER") "Yageo")
        (field (name "PARTNUMBER") "RC1206JR-07100RL")
        (field (name "VALUEMANUFACTURERPARTNUMBER") "Resistor, 33.2K, 1206")
      )
      (libsource (lib "") (part "Resistor_1206_1"))
    )
    (comp (ref "R63")
      (value "100K")
      (footprint "StandardCase:RES: 1206")
      (fields
        (field (name "MANUFACTURER") "Yageo")
        (field (name "PARTNUMBER") "RC1206JR-07100RL")
        (field (name "VALUEMANUFACTURERPARTNUMBER") "Resistor, 100K, 1206")
      )
      (libsource (lib "Resistor") (part "Resistor_1206"))
    )
    (comp (ref "R64")
      (value "100K")
      (footprint "StandardCase:RES: 1206")
      (fields
        (field (name "MANUFACTURER") "Yageo")
        (field (name "PARTNUMBER") "RC1206JR-07100RL")
        (field (name "VALUEMANUFACTURERPARTNUMBER") "Resistor, 100K, 1206")
      )
      (libsource (lib "Resistor") (part "Resistor_1206"))
    )
    (comp (ref "R65")
      (value "100K")
      (footprint "StandardCase:RES: 1206")
      (fields
        (field (name "MANUFACTURER") "Yageo")
        (field (name "PARTNUMBER") "RC1206JR-07100RL")
        (field (name "VALUEMANUFACTURERPARTNUMBER") "Resistor, 100K, 1206")
      )
      (libsource (lib "Resistor") (part "Resistor_1206"))
    )
    (comp (ref "R67")
      (value "1K")
      (footprint "StandardCase:RES: 1206")
      (fields
        (field (name "MANUFACTURER") "Yageo")
        (field (name "PARTNUMBER") "RC1206JR-07100RL")
        (field (name "VALUEMANUFACTURERPARTNUMBER") "Resistor, 1K, 1206")
      )
      (libsource (lib "Resistor") (part "Resistor_1206"))
    )
    (comp (ref "R68")
      (value "18.2K")
      (footprint "StandardCase:RES: 1206")
      (fields
        (field (name "MANUFACTURER") "Yageo")
        (field (name "PARTNUMBER") "RC1206JR-07100RL")
        (field (name "VALUEMANUFACTURERPARTNUMBER") "Resistor, 18.2K, 1206")
      )
      (libsource (lib "Resistor") (part "Resistor_1206"))
    )
    (comp (ref "R69")
      (value "10K")
      (footprint "StandardCase:RES: 1206")
      (fields
        (field (name "MANUFACTURER") "Yageo")
        (field (name "PARTNUMBER") "RC1206JR-07100RL")
        (field (name "VALUEMANUFACTURERPARTNUMBER") "Resistor, 10K, 1206")
      )
      (libsource (lib "") (part "Resistor_1206_1"))
    )
    (comp (ref "R70")
      (value "10K")
      (footprint "StandardCase:RES: 1206")
      (fields
        (field (name "MANUFACTURER") "Yageo")
        (field (name "PARTNUMBER") "RC1206JR-07100RL")
        (field (name "VALUEMANUFACTURERPARTNUMBER") "Resistor, 10K, 1206")
      )
      (libsource (lib "Resistor") (part "Resistor_1206"))
    )
    (comp (ref "R71")
      (value "51.1K")
      (footprint "StandardCase:RES: 1206")
      (fields
        (field (name "MANUFACTURER") "Yageo")
        (field (name "PARTNUMBER") "RC1206JR-07100RL")
        (field (name "VALUEMANUFACTURERPARTNUMBER") "Resistor, 51.1K, 1206")
      )
      (libsource (lib "") (part "Resistor_1206_1"))
    )
    (comp (ref "R72")
      (value "51.1K")
      (footprint "StandardCase:RES: 1206")
      (fields
        (field (name "MANUFACTURER") "Yageo")
        (field (name "PARTNUMBER") "RC1206JR-07100RL")
        (field (name "VALUEMANUFACTURERPARTNUMBER") "Resistor, 51.1K, 1206")
      )
      (libsource (lib "Resistor") (part "Resistor_1206"))
    )
    (comp (ref "R73")
      (value "1K")
      (footprint "StandardCase:RES: 1206")
      (fields
        (field (name "MANUFACTURER") "Yageo")
        (field (name "PARTNUMBER") "RC1206JR-07100RL")
        (field (name "VALUEMANUFACTURERPARTNUMBER") "Resistor, 1K, 1206")
      )
      (libsource (lib "") (part "Resistor_1206_2"))
    )
    (comp (ref "R75")
      (value "10K")
      (footprint "StandardCase:RES: 1206")
      (fields
        (field (name "MANUFACTURER") "Yageo")
        (field (name "PARTNUMBER") "RC1206JR-07100RL")
        (field (name "VALUEMANUFACTURERPARTNUMBER") "Resistor, 10K, 1206")
      )
      (libsource (lib "") (part "Resistor_1206_2"))
    )
    (comp (ref "R76")
      (value "10R")
      (footprint "StandardCase:RES: 1206")
      (fields
        (field (name "MANUFACTURER") "Yageo")
        (field (name "PARTNUMBER") "RC1206JR-07100RL")
        (field (name "VALUEMANUFACTURERPARTNUMBER") "Resistor, 10R, 1206")
      )
      (libsource (lib "") (part "Resistor_1206_2"))
    )
    (comp (ref "R77")
      (value "10K")
      (footprint "StandardCase:RES: 1206")
      (fields
        (field (name "MANUFACTURER") "Yageo")
        (field (name "PARTNUMBER") "RC1206JR-07100RL")
        (field (name "VALUEMANUFACTURERPARTNUMBER") "Resistor, 10K, 1206")
      )
      (libsource (lib "") (part "Resistor_1206_1"))
    )
    (comp (ref "R78")
      (value "10K")
      (footprint "StandardCase:RES: 1206")
      (fields
        (field (name "MANUFACTURER") "Yageo")
        (field (name "PARTNUMBER") "RC1206JR-07100RL")
        (field (name "VALUEMANUFACTURERPARTNUMBER") "Resistor, 10K, 1206")
      )
      (libsource (lib "Resistor") (part "Resistor_1206"))
    )
    (comp (ref "R79")
      (value "10K")
      (footprint "StandardCase:RES: 1206")
      (fields
        (field (name "MANUFACTURER") "Yageo")
        (field (name "PARTNUMBER") "RC1206JR-07100RL")
        (field (name "VALUEMANUFACTURERPARTNUMBER") "Resistor, 10K, 1206")
      )
      (libsource (lib "Resistor") (part "Resistor_1206"))
    )
    (comp (ref "R80")
      (value "10K")
      (footprint "StandardCase:RES: 1206")
      (fields
        (field (name "MANUFACTURER") "Yageo")
        (field (name "PARTNUMBER") "RC1206JR-07100RL")
        (field (name "VALUEMANUFACTURERPARTNUMBER") "Resistor, 10K, 1206")
      )
      (libsource (lib "Resistor") (part "Resistor_1206"))
    )
    (comp (ref "R81")
      (value "10K")
      (footprint "StandardCase:RES: 1206")
      (fields
        (field (name "MANUFACTURER") "Yageo")
        (field (name "PARTNUMBER") "RC1206JR-07100RL")
        (field (name "VALUEMANUFACTURERPARTNUMBER") "Resistor, 10K, 1206")
      )
      (libsource (lib "Resistor") (part "Resistor_1206"))
    )
    (comp (ref "R84")
      (value "10K")
      (footprint "StandardCase:RES: 1206")
      (fields
        (field (name "MANUFACTURER") "Yageo")
        (field (name "PARTNUMBER") "RC1206JR-07100RL")
        (field (name "VALUEMANUFACTURERPARTNUMBER") "Resistor, 10K, 1206")
      )
      (libsource (lib "Resistor") (part "Resistor_1206"))
    )
    (comp (ref "R85")
      (value "2K")
      (footprint "StandardCase:RES: 1206")
      (fields
        (field (name "MANUFACTURER") "Yageo")
        (field (name "PARTNUMBER") "RC1206JR-07100RL")
        (field (name "VALUEMANUFACTURERPARTNUMBER") "Resistor, 2K, 1206")
      )
      (libsource (lib "Resistor") (part "Resistor_1206"))
    )
    (comp (ref "R86")
      (value "2K")
      (footprint "StandardCase:RES: 1206")
      (fields
        (field (name "MANUFACTURER") "Yageo")
        (field (name "PARTNUMBER") "RC1206JR-07100RL")
        (field (name "VALUEMANUFACTURERPARTNUMBER") "Resistor, 2K, 1206")
      )
      (libsource (lib "Resistor") (part "Resistor_1206"))
    )
    (comp (ref "R87")
      (value "2K")
      (footprint "StandardCase:RES: 1206")
      (fields
        (field (name "MANUFACTURER") "Yageo")
        (field (name "PARTNUMBER") "RC1206JR-07100RL")
        (field (name "VALUEMANUFACTURERPARTNUMBER") "Resistor, 2K, 1206")
      )
      (libsource (lib "Resistor") (part "Resistor_1206"))
    )
    (comp (ref "R88")
      (value "2K")
      (footprint "StandardCase:RES: 1206")
      (fields
        (field (name "MANUFACTURER") "Yageo")
        (field (name "PARTNUMBER") "RC1206JR-07100RL")
        (field (name "VALUEMANUFACTURERPARTNUMBER") "Resistor, 2K, 1206")
      )
      (libsource (lib "Resistor") (part "Resistor_1206"))
    )
    (comp (ref "R89")
      (value "1K")
      (footprint "StandardCase:RES: 1206")
      (fields
        (field (name "MANUFACTURER") "Yageo")
        (field (name "PARTNUMBER") "RC1206JR-07100RL")
        (field (name "VALUEMANUFACTURERPARTNUMBER") "Resistor, 1K, 1206")
      )
      (libsource (lib "") (part "Resistor_1206_1"))
    )
    (comp (ref "R90")
      (value "47R")
      (footprint "StandardCase:RES: 1206")
      (fields
        (field (name "MANUFACTURER") "Yageo")
        (field (name "PARTNUMBER") "RC1206JR-07100RL")
        (field (name "VALUEMANUFACTURERPARTNUMBER") "Resistor, 47R, 1206")
      )
      (libsource (lib "") (part "Resistor_1206_1"))
    )
    (comp (ref "R91")
      (value "10K")
      (footprint "StandardCase:RES: 1206")
      (fields
        (field (name "MANUFACTURER") "Yageo")
        (field (name "PARTNUMBER") "RC1206JR-07100RL")
        (field (name "VALUEMANUFACTURERPARTNUMBER") "Resistor, 10K, 1206")
      )
      (libsource (lib "Resistor") (part "Resistor_1206"))
    )
    (comp (ref "R92")
      (value "10K")
      (footprint "StandardCase:RES: 1206")
      (fields
        (field (name "MANUFACTURER") "Yageo")
        (field (name "PARTNUMBER") "RC1206JR-07100RL")
        (field (name "VALUEMANUFACTURERPARTNUMBER") "Resistor, 10K, 1206")
      )
      (libsource (lib "") (part "Resistor_1206_1"))
    )
    (comp (ref "R93")
      (value "2K")
      (footprint "StandardCase:RES: 1206")
      (fields
        (field (name "MANUFACTURER") "Yageo")
        (field (name "PARTNUMBER") "RC1206JR-07100RL")
        (field (name "VALUEMANUFACTURERPARTNUMBER") "Resistor, 2K, 1206")
      )
      (libsource (lib "Resistor") (part "Resistor_1206"))
    )
    (comp (ref "R94")
      (value "2K")
      (footprint "StandardCase:RES: 1206")
      (fields
        (field (name "MANUFACTURER") "Yageo")
        (field (name "PARTNUMBER") "RC1206JR-07100RL")
        (field (name "VALUEMANUFACTURERPARTNUMBER") "Resistor, 2K, 1206")
      )
      (libsource (lib "Resistor") (part "Resistor_1206"))
    )
    (comp (ref "R95")
      (value "47R")
      (footprint "StandardCase:RES: 1206")
      (fields
        (field (name "MANUFACTURER") "Yageo")
        (field (name "PARTNUMBER") "RC1206JR-07100RL")
        (field (name "VALUEMANUFACTURERPARTNUMBER") "Resistor, 47R, 1206")
      )
      (libsource (lib "") (part "Resistor_1206_1"))
    )
    (comp (ref "R96")
      (value "2K")
      (footprint "StandardCase:RES: 1206")
      (fields
        (field (name "MANUFACTURER") "Yageo")
        (field (name "PARTNUMBER") "RC1206JR-07100RL")
        (field (name "VALUEMANUFACTURERPARTNUMBER") "Resistor, 2K, 1206")
      )
      (libsource (lib "Resistor") (part "Resistor_1206"))
    )
    (comp (ref "R97")
      (value "47R")
      (footprint "StandardCase:RES: 1206")
      (fields
        (field (name "MANUFACTURER") "Yageo")
        (field (name "PARTNUMBER") "RC1206JR-07100RL")
        (field (name "VALUEMANUFACTURERPARTNUMBER") "Resistor, 47R, 1206")
      )
      (libsource (lib "") (part "Resistor_1206_1"))
    )
    (comp (ref "R98")
      (value "10K")
      (footprint "StandardCase:RES: 1206")
      (fields
        (field (name "MANUFACTURER") "Yageo")
        (field (name "PARTNUMBER") "RC1206JR-07100RL")
        (field (name "VALUEMANUFACTURERPARTNUMBER") "Resistor, 10K, 1206")
      )
      (libsource (lib "Resistor") (part "Resistor_1206"))
    )
    (comp (ref "R99")
      (value "47R")
      (footprint "StandardCase:RES: 1206")
      (fields
        (field (name "MANUFACTURER") "Yageo")
        (field (name "PARTNUMBER") "RC1206JR-07100RL")
        (field (name "VALUEMANUFACTURERPARTNUMBER") "Resistor, 47R, 1206")
      )
      (libsource (lib "") (part "Resistor_1206_1"))
    )
    (comp (ref "R100")
      (value "1K")
      (footprint "StandardCase:RES: 1206")
      (fields
        (field (name "MANUFACTURER") "Yageo")
        (field (name "PARTNUMBER") "RC1206JR-07100RL")
        (field (name "VALUEMANUFACTURERPARTNUMBER") "Resistor, 1K, 1206")
      )
      (libsource (lib "") (part "Resistor_1206_2"))
    )
    (comp (ref "R101")
      (value "10K")
      (footprint "StandardCase:RES: 1206")
      (fields
        (field (name "MANUFACTURER") "Yageo")
        (field (name "PARTNUMBER") "RC1206JR-07100RL")
        (field (name "VALUEMANUFACTURERPARTNUMBER") "Resistor, 10K, 1206")
      )
      (libsource (lib "Resistor") (part "Resistor_1206"))
    )
    (comp (ref "R102")
      (value "1K")
      (footprint "StandardCase:RES: 1206")
      (fields
        (field (name "MANUFACTURER") "Yageo")
        (field (name "PARTNUMBER") "RC1206JR-07100RL")
        (field (name "VALUEMANUFACTURERPARTNUMBER") "Resistor, 1K, 1206")
      )
      (libsource (lib "Resistor") (part "Resistor_1206"))
    )
    (comp (ref "R103")
      (value "10K")
      (footprint "StandardCase:RES: 1206")
      (fields
        (field (name "MANUFACTURER") "Yageo")
        (field (name "PARTNUMBER") "RC1206JR-07100RL")
        (field (name "VALUEMANUFACTURERPARTNUMBER") "Resistor, 10K, 1206")
      )
      (libsource (lib "Resistor") (part "Resistor_1206"))
    )
    (comp (ref "R104")
      (value "1K")
      (footprint "StandardCase:RES: 1206")
      (fields
        (field (name "MANUFACTURER") "Yageo")
        (field (name "PARTNUMBER") "RC1206JR-07100RL")
        (field (name "VALUEMANUFACTURERPARTNUMBER") "Resistor, 1K, 1206")
      )
      (libsource (lib "") (part "Resistor_1206_2"))
    )
    (comp (ref "R105")
      (value "100K")
      (footprint "StandardCase:RES: 1206")
      (fields
        (field (name "MANUFACTURER") "Yageo")
        (field (name "PARTNUMBER") "RC1206JR-07100RL")
        (field (name "VALUEMANUFACTURERPARTNUMBER") "Resistor, 100K, 1206")
      )
      (libsource (lib "") (part "Resistor_1206_3"))
    )
    (comp (ref "R106")
      (value "10K")
      (footprint "StandardCase:RES: 1206")
      (fields
        (field (name "MANUFACTURER") "Yageo")
        (field (name "PARTNUMBER") "RC1206JR-07100RL")
        (field (name "VALUEMANUFACTURERPARTNUMBER") "Resistor, 10K, 1206")
      )
      (libsource (lib "Resistor") (part "Resistor_1206"))
    )
    (comp (ref "R107")
      (value "499K")
      (footprint "StandardCase:RES: 1206")
      (fields
        (field (name "MANUFACTURER") "Yageo")
        (field (name "PARTNUMBER") "RC1206JR-07100RL")
        (field (name "VALUEMANUFACTURERPARTNUMBER") "Resistor, 499K, 1206")
      )
      (libsource (lib "") (part "Resistor_1206_2"))
    )
    (comp (ref "R108")
      (value "2K")
      (footprint "StandardCase:RES: 1206")
      (fields
        (field (name "MANUFACTURER") "Yageo")
        (field (name "PARTNUMBER") "RC1206JR-07100RL")
        (field (name "VALUEMANUFACTURERPARTNUMBER") "Resistor, 2K, 1206")
      )
      (libsource (lib "Resistor") (part "Resistor_1206"))
    )
    (comp (ref "R109")
      (value "2K")
      (footprint "StandardCase:RES: 1206")
      (fields
        (field (name "MANUFACTURER") "Yageo")
        (field (name "PARTNUMBER") "RC1206JR-07100RL")
        (field (name "VALUEMANUFACTURERPARTNUMBER") "Resistor, 2K, 1206")
      )
      (libsource (lib "") (part "Resistor_1206_2"))
    )
    (comp (ref "R110")
      (value "10K")
      (footprint "StandardCase:RES: 1206")
      (fields
        (field (name "MANUFACTURER") "Yageo")
        (field (name "PARTNUMBER") "RC1206JR-07100RL")
        (field (name "VALUEMANUFACTURERPARTNUMBER") "Resistor, 10K, 1206")
      )
      (libsource (lib "Resistor") (part "Resistor_1206"))
    )
    (comp (ref "R111")
      (value "10K")
      (footprint "StandardCase:RES: 1206")
      (fields
        (field (name "MANUFACTURER") "Yageo")
        (field (name "PARTNUMBER") "RC1206JR-07100RL")
        (field (name "VALUEMANUFACTURERPARTNUMBER") "Resistor, 10K, 1206")
      )
      (libsource (lib "Resistor") (part "Resistor_1206"))
    )
    (comp (ref "R112")
      (value "1K")
      (footprint "StandardCase:RES: 1206")
      (fields
        (field (name "MANUFACTURER") "Yageo")
        (field (name "PARTNUMBER") "RC1206JR-07100RL")
        (field (name "VALUEMANUFACTURERPARTNUMBER") "Resistor, 1K, 1206")
      )
      (libsource (lib "Resistor") (part "Resistor_1206"))
    )
    (comp (ref "R113")
      (value "1K")
      (footprint "StandardCase:RES: 1206")
      (fields
        (field (name "MANUFACTURER") "Yageo")
        (field (name "PARTNUMBER") "RC1206JR-07100RL")
        (field (name "VALUEMANUFACTURERPARTNUMBER") "Resistor, 1K, 1206")
      )
      (libsource (lib "Resistor") (part "Resistor_1206"))
    )
    (comp (ref "R114")
      (value "2K")
      (footprint "StandardCase:RES: 1206")
      (fields
        (field (name "MANUFACTURER") "Yageo")
        (field (name "PARTNUMBER") "RC1206JR-07100RL")
        (field (name "VALUEMANUFACTURERPARTNUMBER") "Resistor, 2K, 1206")
      )
      (libsource (lib "") (part "Resistor_1206_2"))
    )
    (comp (ref "R115")
      (value "10K")
      (footprint "StandardCase:RES: 1206")
      (fields
        (field (name "MANUFACTURER") "Yageo")
        (field (name "PARTNUMBER") "RC1206JR-07100RL")
        (field (name "VALUEMANUFACTURERPARTNUMBER") "Resistor, 10K, 1206")
      )
      (libsource (lib "Resistor") (part "Resistor_1206"))
    )
    (comp (ref "R116")
      (value "20K")
      (footprint "StandardCase:RES: 1206")
      (fields
        (field (name "MANUFACTURER") "Yageo")
        (field (name "PARTNUMBER") "RC1206JR-07100RL")
        (field (name "VALUEMANUFACTURERPARTNUMBER") "Resistor, 20K, 1206")
      )
      (libsource (lib "Resistor") (part "Resistor_1206"))
    )
    (comp (ref "R117")
      (value "1K")
      (footprint "StandardCase:RES: 1206")
      (fields
        (field (name "MANUFACTURER") "Yageo")
        (field (name "PARTNUMBER") "RC1206JR-07100RL")
        (field (name "VALUEMANUFACTURERPARTNUMBER") "Resistor, 1K, 1206")
      )
      (libsource (lib "Resistor") (part "Resistor_1206"))
    )
    (comp (ref "R118")
      (value "1K")
      (footprint "StandardCase:RES: 1206")
      (fields
        (field (name "MANUFACTURER") "Yageo")
        (field (name "PARTNUMBER") "RC1206JR-07100RL")
        (field (name "VALUEMANUFACTURERPARTNUMBER") "Resistor, 1K, 1206")
      )
      (libsource (lib "Resistor") (part "Resistor_1206"))
    )
    (comp (ref "R119")
      (value "20K")
      (footprint "StandardCase:RES: 1206")
      (fields
        (field (name "MANUFACTURER") "Yageo")
        (field (name "PARTNUMBER") "RC1206JR-07100RL")
        (field (name "VALUEMANUFACTURERPARTNUMBER") "Resistor, 20K, 1206")
      )
      (libsource (lib "Resistor") (part "Resistor_1206"))
    )
    (comp (ref "R120")
      (value "18.2K")
      (footprint "StandardCase:RES: 1206")
      (fields
        (field (name "MANUFACTURER") "Yageo")
        (field (name "PARTNUMBER") "RC1206JR-07100RL")
        (field (name "VALUEMANUFACTURERPARTNUMBER") "Resistor, 18.2K, 1206")
      )
      (libsource (lib "Resistor") (part "Resistor_1206"))
    )
    (comp (ref "R121")
      (value "2K")
      (footprint "StandardCase:RES: 1206")
      (fields
        (field (name "MANUFACTURER") "Yageo")
        (field (name "PARTNUMBER") "RC1206JR-07100RL")
        (field (name "VALUEMANUFACTURERPARTNUMBER") "Resistor, 2K, 1206")
      )
      (libsource (lib "") (part "Resistor_1206_2"))
    )
    (comp (ref "R122")
      (value "499K")
      (footprint "StandardCase:RES: 1206")
      (fields
        (field (name "MANUFACTURER") "Yageo")
        (field (name "PARTNUMBER") "RC1206JR-07100RL")
        (field (name "VALUEMANUFACTURERPARTNUMBER") "Resistor, 499K, 1206")
      )
      (libsource (lib "") (part "Resistor_1206_2"))
    )
    (comp (ref "R123")
      (value "1K")
      (footprint "StandardCase:RES: 1206")
      (fields
        (field (name "MANUFACTURER") "Yageo")
        (field (name "PARTNUMBER") "RC1206JR-07100RL")
        (field (name "VALUEMANUFACTURERPARTNUMBER") "Resistor, 1K, 1206")
      )
      (libsource (lib "Resistor") (part "Resistor_1206"))
    )
    (comp (ref "R124")
      (value "2K")
      (footprint "StandardCase:RES: 1206")
      (fields
        (field (name "MANUFACTURER") "Yageo")
        (field (name "PARTNUMBER") "RC1206JR-07100RL")
        (field (name "VALUEMANUFACTURERPARTNUMBER") "Resistor, 2K, 1206")
      )
      (libsource (lib "Resistor") (part "Resistor_1206"))
    )
    (comp (ref "R125")
      (value "2K")
      (footprint "StandardCase:RES: 1206")
      (fields
        (field (name "MANUFACTURER") "Yageo")
        (field (name "PARTNUMBER") "RC1206JR-07100RL")
        (field (name "VALUEMANUFACTURERPARTNUMBER") "Resistor, 2K, 1206")
      )
      (libsource (lib "Resistor") (part "Resistor_1206"))
    )
    (comp (ref "R126")
      (value "1K")
      (footprint "StandardCase:RES: 1206")
      (fields
        (field (name "MANUFACTURER") "Yageo")
        (field (name "PARTNUMBER") "RC1206JR-07100RL")
        (field (name "VALUEMANUFACTURERPARTNUMBER") "Resistor, 1K, 1206")
      )
      (libsource (lib "Resistor") (part "Resistor_1206"))
    )
    (comp (ref "R127")
      (value "2K")
      (footprint "StandardCase:RES: 1206")
      (fields
        (field (name "MANUFACTURER") "Yageo")
        (field (name "PARTNUMBER") "RC1206JR-07100RL")
        (field (name "VALUEMANUFACTURERPARTNUMBER") "Resistor, 2K, 1206")
      )
      (libsource (lib "Resistor") (part "Resistor_1206"))
    )
    (comp (ref "R128")
      (value "2K")
      (footprint "StandardCase:RES: 1206")
      (fields
        (field (name "MANUFACTURER") "Yageo")
        (field (name "PARTNUMBER") "RC1206JR-07100RL")
        (field (name "VALUEMANUFACTURERPARTNUMBER") "Resistor, 2K, 1206")
      )
      (libsource (lib "Resistor") (part "Resistor_1206"))
    )
    (comp (ref "R129")
      (value "20K")
      (footprint "StandardCase:RES: 1206")
      (fields
        (field (name "MANUFACTURER") "Yageo")
        (field (name "PARTNUMBER") "RC1206JR-07100RL")
        (field (name "VALUEMANUFACTURERPARTNUMBER") "Resistor, 20K, 1206")
      )
      (libsource (lib "Resistor") (part "Resistor_1206"))
    )
    (comp (ref "R130")
      (value "10K")
      (footprint "StandardCase:RES: 1206")
      (fields
        (field (name "MANUFACTURER") "Yageo")
        (field (name "PARTNUMBER") "RC1206JR-07100RL")
        (field (name "VALUEMANUFACTURERPARTNUMBER") "Resistor, 10K, 1206")
      )
      (libsource (lib "Resistor") (part "Resistor_1206"))
    )
    (comp (ref "R131")
      (value "499K")
      (footprint "StandardCase:RES: 1206")
      (fields
        (field (name "MANUFACTURER") "Yageo")
        (field (name "PARTNUMBER") "RC1206JR-07100RL")
        (field (name "VALUEMANUFACTURERPARTNUMBER") "Resistor, 499K, 1206")
      )
      (libsource (lib "") (part "Resistor_1206_2"))
    )
    (comp (ref "R132")
      (value "5.11R")
      (footprint "StandardCase:RES: 2512")
      (fields
        (field (name "MANUFACTURER") "Yageo")
        (field (name "PARTNUMBER") "RC1206JR-07100RL")
        (field (name "VALUEMANUFACTURERPARTNUMBER") "Resistor, 5.11R, 2512")
      )
      (libsource (lib "") (part "Resistor_1206_2"))
    )
    (comp (ref "R133")
      (value "5.11R")
      (footprint "StandardCase:RES: 2512")
      (fields
        (field (name "MANUFACTURER") "Yageo")
        (field (name "PARTNUMBER") "RC1206JR-07100RL")
        (field (name "VALUEMANUFACTURERPARTNUMBER") "Resistor, 5.11R, 2512")
      )
      (libsource (lib "") (part "Resistor_1206_2"))
    )
    (comp (ref "R134")
      (value "10K")
      (footprint "PcbLib1:CPF-3")
      (fields
        (field (name "MANUFACTURER") "Yageo")
        (field (name "PARTNUMBER") "RC1206JR-07100RL")
        (field (name "VALUEMANUFACTURERPARTNUMBER") "Resistor, 10K, CPF-3")
      )
      (libsource (lib "Resistor") (part "Resistor_1206"))
    )
    (comp (ref "RC1")
      (value "~")
      (footprint "PcbLib1:SCM-24")
      (fields
        (field (name "PARTNUMBER") "DS1011-24SBSiB")
        (field (name "VALUEMANUFACTURERPARTNUMBER") "DS1011-24SBSiB, 24 Pin")
      )
      (libsource (lib "Schlib1") (part "SCM-24"))
    )
    (comp (ref "RC2")
      (value "~")
      (footprint "PcbLib1:MOLEX 2")
      (fields
        (field (name "MANUFACTURER") "MOLEX")
        (field (name "VALUEMANUFACTURERPARTNUMBER") "MOLEX, 0026013114, 2pin")
        (field (name "PARTNUMBER") "0026013114")
        (field (name "COMMENTTEXT") "\"Разъем\"")
      )
      (libsource (lib "") (part "PLS-2_1"))
    )
    (comp (ref "RC3")
      (value "~")
      (footprint "PcbLib1:MOLEX 2x6")
      (fields
        (field (name "MANUFACTURER") "MOLEX")
        (field (name "VALUEMANUFACTURERPARTNUMBER") "MOLEX, 0026013119, 12pin")
        (field (name "PARTNUMBER") "0026013119")
        (field (name "COMMENTTEXT") "\"Разъем\"")
      )
      (libsource (lib "Connector") (part "PLS-12"))
    )
    (comp (ref "RC4")
      (value "~")
      (footprint "PcbLib1:MOLEX 2x4")
      (fields
        (field (name "MANUFACTURER") "MOLEX")
        (field (name "VALUEMANUFACTURERPARTNUMBER") "MOLEX, 0026013144, 8pin")
        (field (name "PARTNUMBER") "0026013144")
        (field (name "COMMENTTEXT") "\"Разъем\"")
      )
      (libsource (lib "Connector") (part "PLS-8"))
    )
    (comp (ref "RC5")
      (value "~")
      (footprint "PcbLib1:MOLEX 2x3")
      (fields
        (field (name "MANUFACTURER") "MOLEX")
        (field (name "VALUEMANUFACTURERPARTNUMBER") "MOLEX, 0039301060, 6pin")
        (field (name "PARTNUMBER") "0039301060")
        (field (name "COMMENTTEXT") "\"Разъем\"")
      )
      (libsource (lib "Connector") (part "PLS-6"))
    )
    (comp (ref "RC6")
      (value "~")
      (footprint "PcbLib1:MOLEX 3")
      (fields
        (field (name "MANUFACTURER") "MOLEX")
        (field (name "VALUEMANUFACTURERPARTNUMBER") "MOLEX, 0460140304, 3pin")
        (field (name "PARTNUMBER") "0460140304")
        (field (name "COMMENTTEXT") "\"Разъем\"")
      )
      (libsource (lib "Connector") (part "PLS-3"))
    )
    (comp (ref "RC7")
      (value "~")
      (footprint "CustomCase:CON: PLS-2")
      (fields
        (field (name "MANUFACTURER") "Connfly")
        (field (name "VALUEMANUFACTURERPARTNUMBER") "PLS-2, 2pin")
        (field (name "PARTNUMBER") "PLS-2")
        (field (name "COMMENTTEXT") "\"Разъем\"")
      )
      (libsource (lib "Connector") (part "PLS-2"))
    )
    (comp (ref "SW1")
      (value "~")
      (footprint "PcbLib1:DPL-2")
      (fields
        (field (name "PARTNUMBER") "NDP-02")
        (field (name "VALUEMANUFACTURERPARTNUMBER") "NDP-02, DPL-02")
      )
      (libsource (lib "Schlib1") (part "NDP-02"))
    )
    (comp (ref "T1")
      (value "~")
      (footprint "PcbLib1:T1")
      (fields (field (name "PARTNUMBER") "T1"))
      (libsource (lib "Schlib1") (part "T1"))
    )
    (comp (ref "TP1")
      (value "~")
      (footprint "FP_lib_PCB:Test_Point")
      (libsource (lib "PcbLib1") (part "Test_Point"))
    )
    (comp (ref "U1")
      (value "~")
      (footprint "StandardCase:14-SOIC")
      (fields
        (field (name "VALUEMANUFACTURERPARTNUMBER") "CD4093, SOIC-14")
        (field (name "PARTNUMBER") "CD4093")
      )
      (libsource (lib "") (part "CD4093_1"))
    )
    (comp (ref "U2")
      (value "~")
      (footprint "StandardCase:14-SOIC")
      (fields
        (field (name "PARTNUMBER") "LM239")
        (field (name "VALUEMANUFACTURERPARTNUMBER") "LM239, SOIC-14")
      )
      (libsource (lib "Schlib1") (part "LM339"))
    )
    (comp (ref "U3")
      (value "~")
      (footprint "StandardCase:14-SOIC")
      (fields
        (field (name "PARTNUMBER") "MC14013")
        (field (name "VALUEMANUFACTURERPARTNUMBER") "MC14013, SOIC-14")
      )
      (libsource (lib "Schlib1") (part "MC14013"))
    )
    (comp (ref "U4")
      (value "~")
      (footprint "StandardCase:14-SOIC")
      (fields
        (field (name "PARTNUMBER") "MC14023")
        (field (name "VALUEMANUFACTURERPARTNUMBER") "MC14023, SOIC-14")
      )
      (libsource (lib "") (part "MC14023_1"))
    )
    (comp (ref "U5")
      (value "~")
      (footprint "StandardCase:8-SOIC")
      (fields
        (field (name "PARTNUMBER") "LF253")
        (field (name "VALUEMANUFACTURERPARTNUMBER") "LF253, SOIC-8")
      )
      (libsource (lib "Schlib1") (part "LF253"))
    )
    (comp (ref "U7")
      (value "~")
      (footprint "StandardCase:14-SOIC")
      (fields
        (field (name "PARTNUMBER") "LF247")
        (field (name "VALUEMANUFACTURERPARTNUMBER") "LF247, SOIC-14")
      )
      (libsource (lib "Schlib1") (part "LF347"))
    )
    (comp (ref "U8")
      (value "~")
      (footprint "StandardCase:8-SOIC")
      (fields
        (field (name "PARTNUMBER") "MC33202")
        (field (name "VALUEMANUFACTURERPARTNUMBER") "MC33202, SOIC-8")
      )
      (libsource (lib "Schlib1") (part "MC33202"))
    )
    (comp (ref "U9")
      (value "~")
      (footprint "StandardCase:8-SOIC")
      (fields
        (field (name "PARTNUMBER") "MC33064")
        (field (name "VALUEMANUFACTURERPARTNUMBER") "MC33064, SOIC-8")
      )
      (libsource (lib "Schlib1") (part "MC34064"))
    )
    (comp (ref "U10")
      (value "~")
      (footprint "PcbLib1:SC70-6")
      (fields
        (field (name "VALUEMANUFACTURERPARTNUMBER") "AD5641, SC70-6")
        (field (name "PARTNUMBER") "AD5641")
      )
      (libsource (lib "Schlib1") (part "AD5641"))
    )
    (comp (ref "U11")
      (value "~")
      (footprint "StandardCase:SOT23")
      (fields
        (field (name "PARTNUMBER") "LM4040A50IDZ")
        (field (name "VALUEMANUFACTURERPARTNUMBER") "LM4040A50IDZ, SOT23-3")
      )
      (libsource (lib "Schlib1") (part "LM4040"))
    )
    (comp (ref "U12")
      (value "~")
      (footprint "PcbLib1:QFP80P1200X1200X120-44N")
      (fields
        (field (name "VALUEMANUFACTURERPARTNUMBER") "ATMega16-AU, TQFP-44")
        (field (name "PARTNUMBER") "ATMega16-AU")
      )
      (libsource (lib "Schlib1") (part "ATMega16-AU"))
    )
    (comp (ref "U13")
      (value "~")
      (footprint "StandardCase:SOT223")
      (fields
        (field (name "PARTNUMBER") "LM2940-15")
        (field (name "VALUEMANUFACTURERPARTNUMBER") "LM2940-15, SOT223")
      )
      (libsource (lib "Schlib1") (part "LM2940"))
    )
    (comp (ref "U14")
      (value "~")
      (footprint "StandardCase:D2PAK")
      (fields
        (field (name "PARTNUMBER") "MC7805")
        (field (name "VALUEMANUFACTURERPARTNUMBER") "MC7805, D2PAK")
      )
      (libsource (lib "Schlib1") (part "MC7805"))
    )
    (comp (ref "U15")
      (value "~")
      (footprint "StandardCase:8-SOIC")
      (fields
        (field (name "PARTNUMBER") "LM393")
        (field (name "VALUEMANUFACTURERPARTNUMBER") "LM393, SOIC-8")
      )
      (libsource (lib "Schlib1") (part "LM393"))
    )
    (comp (ref "U16")
      (value "~")
      (footprint "StandardCase:8-SOIC")
      (fields
        (field (name "PARTNUMBER") "IXDN602SIA")
        (field (name "VALUEMANUFACTURERPARTNUMBER") "IXDN602SIA, SOIC-8")
      )
      (libsource (lib "Schlib1") (part "IXDN602SIA"))
    )
    (comp (ref "U17")
      (value "~")
      (footprint "PcbLib1:HSOP8")
      (fields
        (field (name "PARTNUMBER") "L7986")
        (field (name "VALUEMANUFACTURERPARTNUMBER") "L7986, HSOP-8")
      )
      (libsource (lib "Schlib1") (part "L7986"))
    )
    (comp (ref "UART")
      (value "~")
      (footprint "CustomCase:CON: PLS-4")
      (fields
        (field (name "MANUFACTURER") "Connfly")
        (field (name "VALUEMANUFACTURERPARTNUMBER") "PLS-4, 4pin")
        (field (name "PARTNUMBER") "PLS-4")
        (field (name "COMMENTTEXT") "\"Разъем\"")
      )
      (libsource (lib "Connector") (part "PLS-4"))
    )
    (comp (ref "VO1")
      (value "~")
      (footprint "PcbLib1:SOP254P980X405-4L")
      (fields
        (field (name "PARTNUMBER") "SFH610*")
        (field (name "VALUEMANUFACTURERPARTNUMBER") "SFH610*, SMD (option 7)")
      )
      (libsource (lib "Schlib1") (part "SFH610"))
    )
    (comp (ref "Y1")
      (value "~")
      (footprint "PcbLib1:HC49SM")
      (fields
        (field (name "PARTNUMBER") "HC49SM-16.000MHZ-20PF")
        (field (name "VALUEMANUFACTURERPARTNUMBER") "HC49SM-16.000MHZ-20PF, HC49SM")
      )
      (libsource (lib "Schlib1") (part "HC49SM"))
    )
  )
  (nets
    (net (code "1") (name "+5v") (class "Default")
      (node (ref "C34") (pin "2") (pinfunction "2_2") (pintype "power_in"))
      (node (ref "C47") (pin "2") (pinfunction "2_2") (pintype "power_in"))
      (node (ref "C50") (pin "2") (pinfunction "2_2") (pintype "power_in"))
      (node (ref "C56") (pin "2") (pinfunction "2_2") (pintype "power_in"))
      (node (ref "C61") (pin "2") (pinfunction "2_2") (pintype "power_in"))
      (node (ref "C62") (pin "2") (pinfunction "2_2") (pintype "power_in"))
      (node (ref "D20") (pin "2") (pinfunction "2_2") (pintype "passive"))
      (node (ref "D21") (pin "2") (pinfunction "2_2") (pintype "passive"))
      (node (ref "D22") (pin "2") (pinfunction "2_2") (pintype "passive"))
      (node (ref "D23") (pin "2") (pinfunction "2_2") (pintype "passive"))
      (node (ref "D24") (pin "2") (pinfunction "2_2") (pintype "passive"))
      (node (ref "D25") (pin "2") (pinfunction "2_2") (pintype "passive"))
      (node (ref "D26") (pin "2") (pinfunction "2_2") (pintype "passive"))
      (node (ref "D27") (pin "2") (pinfunction "2_2") (pintype "passive"))
      (node (ref "D28") (pin "2") (pinfunction "2_2") (pintype "passive"))
      (node (ref "PGM") (pin "1") (pinfunction "1_1") (pintype "passive"))
      (node (ref "R103") (pin "2") (pinfunction "2_2") (pintype "passive"))
      (node (ref "R105") (pin "1") (pinfunction "1_1") (pintype "passive"))
      (node (ref "R106") (pin "2") (pinfunction "2_2") (pintype "passive"))
      (node (ref "R111") (pin "2") (pinfunction "2_2") (pintype "passive"))
      (node (ref "R112") (pin "2") (pinfunction "2_2") (pintype "passive"))
      (node (ref "R118") (pin "2") (pinfunction "2_2") (pintype "passive"))
      (node (ref "R119") (pin "2") (pinfunction "2_2") (pintype "passive"))
      (node (ref "R123") (pin "2") (pinfunction "2_2") (pintype "passive"))
      (node (ref "R126") (pin "2") (pinfunction "2_2") (pintype "passive"))
      (node (ref "R84") (pin "2") (pinfunction "2_2") (pintype "passive"))
      (node (ref "RC1") (pin "23") (pinfunction "23_23") (pintype "passive"))
      (node (ref "RC1") (pin "24") (pinfunction "24_24") (pintype "passive"))
      (node (ref "U12") (pin "17") (pinfunction "VCC_17") (pintype "passive"))
      (node (ref "U12") (pin "38") (pinfunction "VCC_38") (pintype "passive"))
      (node (ref "U12") (pin "5") (pinfunction "VCC_5") (pintype "passive"))
      (node (ref "U14") (pin "3") (pinfunction "OUT_3") (pintype "passive"))
      (node (ref "U8") (pin "8") (pinfunction "V+_8") (pintype "power_in"))
      (node (ref "U9") (pin "2") (pinfunction "IN_2") (pintype "passive"))
      (node (ref "UART") (pin "1") (pinfunction "1_1") (pintype "passive"))
    )
    (net (code "2") (name "+15v") (class "Default")
      (node (ref "C17") (pin "2") (pinfunction "2_2") (pintype "power_in"))
      (node (ref "C18") (pin "2") (pinfunction "2_2") (pintype "power_in"))
      (node (ref "C19") (pin "2") (pinfunction "2_2") (pintype "power_in"))
      (node (ref "C24") (pin "2") (pinfunction "2_2") (pintype "power_in"))
      (node (ref "C36") (pin "2") (pinfunction "2_2") (pintype "power_in"))
      (node (ref "C39") (pin "2") (pinfunction "2_2") (pintype "power_in"))
      (node (ref "C4") (pin "2") (pinfunction "2_2") (pintype "power_in"))
      (node (ref "C48") (pin "1") (pinfunction "1_1") (pintype "power_in"))
      (node (ref "C5") (pin "1") (pinfunction "1_1") (pintype "power_in"))
      (node (ref "C6") (pin "1") (pinfunction "1_1") (pintype "power_in"))
      (node (ref "C67") (pin "2") (pinfunction "2_2") (pintype "power_in"))
      (node (ref "C9") (pin "1") (pinfunction "1_1") (pintype "power_in"))
      (node (ref "D10") (pin "2") (pinfunction "2_2") (pintype "passive"))
      (node (ref "D18") (pin "1") (pinfunction "1_1") (pintype "passive"))
      (node (ref "D3") (pin "2") (pinfunction "2_2") (pintype "passive"))
      (node (ref "D8") (pin "2") (pinfunction "2_2") (pintype "passive"))
      (node (ref "D9") (pin "2") (pinfunction "2_2") (pintype "passive"))
      (node (ref "R100") (pin "2") (pinfunction "2_2") (pintype "passive"))
      (node (ref "R125") (pin "2") (pinfunction "2_2") (pintype "passive"))
      (node (ref "R128") (pin "2") (pinfunction "2_2") (pintype "passive"))
      (node (ref "R129") (pin "2") (pinfunction "2_2") (pintype "passive"))
      (node (ref "R19") (pin "2") (pinfunction "2_2") (pintype "passive"))
      (node (ref "R21") (pin "2") (pinfunction "2_2") (pintype "passive"))
      (node (ref "R38") (pin "2") (pinfunction "2_2") (pintype "passive"))
      (node (ref "R44") (pin "2") (pinfunction "2_2") (pintype "passive"))
      (node (ref "R55") (pin "2") (pinfunction "2_2") (pintype "passive"))
      (node (ref "R56") (pin "2") (pinfunction "2_2") (pintype "passive"))
      (node (ref "R59") (pin "2") (pinfunction "2_2") (pintype "passive"))
      (node (ref "R65") (pin "2") (pinfunction "2_2") (pintype "passive"))
      (node (ref "R67") (pin "2") (pinfunction "2_2") (pintype "passive"))
      (node (ref "R70") (pin "2") (pinfunction "2_2") (pintype "passive"))
      (node (ref "RC1") (pin "1") (pinfunction "1_1") (pintype "passive"))
      (node (ref "RC1") (pin "2") (pinfunction "2_2") (pintype "passive"))
      (node (ref "RC3") (pin "12") (pinfunction "12_12") (pintype "power_in"))
      (node (ref "RC3") (pin "2") (pinfunction "2_2") (pintype "passive"))
      (node (ref "RC4") (pin "3") (pinfunction "3_3") (pintype "power_in"))
      (node (ref "RC5") (pin "4") (pinfunction "4_4") (pintype "power_in"))
      (node (ref "T1") (pin "3") (pinfunction "3_3") (pintype "power_in"))
      (node (ref "U13") (pin "1") (pinfunction "IN_1") (pintype "passive"))
      (node (ref "U15") (pin "8") (pinfunction "V+_8") (pintype "power_in"))
      (node (ref "U16") (pin "6") (pinfunction "VDD_6") (pintype "passive"))
      (node (ref "U17") (pin "8") (pinfunction "VCC_8") (pintype "passive"))
      (node (ref "U2") (pin "3") (pinfunction "V+_3") (pintype "power_in"))
      (node (ref "U5") (pin "8") (pinfunction "V+_8") (pintype "power_in"))
      (node (ref "U7") (pin "4") (pinfunction "V+_4") (pintype "power_in"))
    )
    (net (code "3") (name "+CMOSV") (class "Default")
      (node (ref "C16") (pin "2") (pinfunction "2_2") (pintype "power_in"))
      (node (ref "C63") (pin "1") (pinfunction "1_1") (pintype "power_in"))
      (node (ref "R108") (pin "2") (pinfunction "2_2") (pintype "passive"))
      (node (ref "R18") (pin "2") (pinfunction "2_2") (pintype "passive"))
      (node (ref "R22") (pin "2") (pinfunction "2_2") (pintype "passive"))
      (node (ref "R24") (pin "2") (pinfunction "2_2") (pintype "passive"))
      (node (ref "R36") (pin "2") (pinfunction "2_2") (pintype "passive"))
      (node (ref "U1") (pin "14") (pintype "passive"))
      (node (ref "U13") (pin "3") (pinfunction "OUT_3") (pintype "passive"))
      (node (ref "U3") (pin "14") (pinfunction "VDD_14") (pintype "passive"))
      (node (ref "U4") (pin "14") (pintype "power_in"))
    )
    (net (code "4") (name "-15v") (class "Default")
      (node (ref "C11") (pin "2") (pinfunction "2_2") (pintype "power_in"))
      (node (ref "C21") (pin "2") (pinfunction "2_2") (pintype "power_in"))
      (node (ref "C22") (pin "2") (pinfunction "2_2") (pintype "power_in"))
      (node (ref "C27") (pin "2") (pinfunction "2_2") (pintype "power_in"))
      (node (ref "C28") (pin "2") (pinfunction "2_2") (pintype "power_in"))
      (node (ref "C3") (pin "2") (pinfunction "2_2") (pintype "power_in"))
      (node (ref "C40") (pin "2") (pinfunction "2_2") (pintype "power_in"))
      (node (ref "C5") (pin "2") (pinfunction "2_2") (pintype "power_in"))
      (node (ref "C9") (pin "2") (pinfunction "2_2") (pintype "power_in"))
      (node (ref "D10") (pin "1") (pinfunction "1_1") (pintype "passive"))
      (node (ref "D29") (pin "1") (pinfunction "1_1") (pintype "passive"))
      (node (ref "D5") (pin "1") (pinfunction "1_1") (pintype "passive"))
      (node (ref "D9") (pin "1") (pinfunction "1_1") (pintype "passive"))
      (node (ref "Q5") (pin "2") (pinfunction "E_2") (pintype "passive"))
      (node (ref "R116") (pin "1") (pinfunction "1_1") (pintype "passive"))
      (node (ref "R127") (pin "1") (pinfunction "1_1") (pintype "passive"))
      (node (ref "R16") (pin "1") (pinfunction "1_1") (pintype "passive"))
      (node (ref "R42") (pin "1") (pinfunction "1_1") (pintype "passive"))
      (node (ref "R54") (pin "2") (pinfunction "2_2") (pintype "passive"))
      (node (ref "RC1") (pin "3") (pinfunction "3_3") (pintype "passive"))
      (node (ref "RC1") (pin "4") (pinfunction "4_4") (pintype "passive"))
      (node (ref "RC2") (pin "2") (pinfunction "2_2") (pintype "passive"))
      (node (ref "RC3") (pin "8") (pinfunction "8_8") (pintype "power_in"))
      (node (ref "RC4") (pin "5") (pinfunction "5_5") (pintype "power_in"))
      (node (ref "RC5") (pin "5") (pinfunction "5_5") (pintype "power_in"))
      (node (ref "U17") (pin "7") (pinfunction "GND_7") (pintype "passive"))
      (node (ref "U17") (pin "9") (pinfunction "TP_9") (pintype "passive"))
      (node (ref "U5") (pin "4") (pinfunction "V-_4") (pintype "power_in"))
      (node (ref "U7") (pin "11") (pinfunction "V-_11") (pintype "power_in"))
      (node (ref "VO1") (pin "4") (pinfunction "E_4") (pintype "passive"))
    )
    (net (code "5") (name "/+5VREF") (class "Default")
      (node (ref "C41") (pin "2") (pinfunction "2_2") (pintype "power_in"))
      (node (ref "C57") (pin "1") (pinfunction "1_1") (pintype "power_in"))
      (node (ref "C58") (pin "1") (pinfunction "1_1") (pintype "power_in"))
      (node (ref "C66") (pin "1") (pinfunction "1_1") (pintype "power_in"))
      (node (ref "R100") (pin "1") (pinfunction "1_1") (pintype "passive"))
      (node (ref "R109") (pin "1") (pinfunction "1_1") (pintype "passive"))
      (node (ref "R117") (pin "2") (pinfunction "2_2") (pintype "passive"))
      (node (ref "R121") (pin "1") (pinfunction "1_1") (pintype "passive"))
      (node (ref "R57*") (pin "2") (pinfunction "2_2") (pintype "passive"))
      (node (ref "U10") (pin "4") (pinfunction "ADD/VREF_4") (pintype "passive"))
      (node (ref "U11") (pin "1") (pintype "passive"))
      (node (ref "U12") (pin "27") (pinfunction "AVCC_27") (pintype "passive"))
      (node (ref "U12") (pin "29") (pinfunction "AREF_29") (pintype "passive"))
      (node (ref "U7") (pin "3") (pinfunction "IN+_3") (pintype "input"))
    )
    (net (code "6") (name "/+5VREF_F") (class "Default")
      (node (ref "C38") (pin "1") (pinfunction "1_1") (pintype "power_in"))
      (node (ref "R75") (pin "1") (pinfunction "1_1") (pintype "passive"))
      (node (ref "R76") (pin "1") (pinfunction "1_1") (pintype "passive"))
      (node (ref "R80") (pin "2") (pinfunction "2_2") (pintype "passive"))
      (node (ref "R81") (pin "2") (pinfunction "2_2") (pintype "passive"))
      (node (ref "R91") (pin "2") (pinfunction "2_2") (pintype "passive"))
      (node (ref "R92") (pin "2") (pinfunction "2_2") (pintype "passive"))
      (node (ref "RC1") (pin "14") (pinfunction "14_14") (pintype "passive"))
    )
    (net (code "7") (name "/+STUD") (class "Default")
      (node (ref "C1") (pin "1") (pinfunction "1_1") (pintype "power_in"))
      (node (ref "R134") (pin "1") (pinfunction "1_1") (pintype "passive"))
      (node (ref "R27") (pin "1") (pinfunction "1_1") (pintype "passive"))
      (node (ref "R8") (pin "1") (pinfunction "1_1") (pintype "passive"))
      (node (ref "RC6") (pin "1") (pinfunction "1_1") (pintype "passive"))
    )
    (net (code "8") (name "/-STUD") (class "Default")
      (node (ref "C1") (pin "2") (pinfunction "2_2") (pintype "power_in"))
      (node (ref "R134") (pin "2") (pinfunction "2_2") (pintype "passive"))
      (node (ref "R28") (pin "2") (pinfunction "2_2") (pintype "passive"))
      (node (ref "RC6") (pin "3") (pinfunction "3_3") (pintype "power_in"))
      (node (ref "T1") (pin "1") (pinfunction "1_1") (pintype "power_in"))
    )
    (net (code "9") (name "/1V{slash}20V") (class "Default")
      (node (ref "R79") (pin "2") (pinfunction "2_2") (pintype "passive"))
      (node (ref "R87") (pin "2") (pinfunction "2_2") (pintype "passive"))
      (node (ref "U8") (pin "1") (pinfunction "OUT_1") (pintype "power_in"))
      (node (ref "U8") (pin "2") (pinfunction "IN-_2") (pintype "input"))
    )
    (net (code "10") (name "/1V{slash}20V_PA1") (class "Default")
      (node (ref "C45") (pin "1") (pinfunction "1_1") (pintype "power_in"))
      (node (ref "D27") (pin "3") (pinfunction "3_3") (pintype "passive"))
      (node (ref "R87") (pin "1") (pinfunction "1_1") (pintype "passive"))
      (node (ref "U12") (pin "36") (pinfunction "PA1_(ADC1)_36") (pintype "passive"))
    )
    (net (code "11") (name "/1V{slash}100A") (class "Default")
      (node (ref "R78") (pin "2") (pinfunction "2_2") (pintype "passive"))
      (node (ref "R88") (pin "2") (pinfunction "2_2") (pintype "passive"))
      (node (ref "U8") (pin "6") (pinfunction "IN-_6") (pintype "input"))
      (node (ref "U8") (pin "7") (pinfunction "OUT_7") (pintype "power_in"))
    )
    (net (code "12") (name "/1V{slash}100A_PA0") (class "Default")
      (node (ref "C46") (pin "1") (pinfunction "1_1") (pintype "power_in"))
      (node (ref "D28") (pin "3") (pinfunction "3_3") (pintype "passive"))
      (node (ref "R88") (pin "1") (pinfunction "1_1") (pintype "passive"))
      (node (ref "U12") (pin "37") (pinfunction "PA0_(ADC0)_37") (pintype "passive"))
    )
    (net (code "13") (name "/CONTACTOR") (class "Default")
      (node (ref "C42") (pin "2") (pinfunction "2_2") (pintype "power_in"))
      (node (ref "RC1") (pin "6") (pinfunction "6_6") (pintype "passive"))
      (node (ref "U12") (pin "12") (pinfunction "PD3_(INT1)_12") (pintype "passive"))
    )
    (net (code "14") (name "/CONTACTOR_PC3") (class "Default")
      (node (ref "R102") (pin "2") (pinfunction "2_2") (pintype "passive"))
      (node (ref "U12") (pin "22") (pinfunction "PC3_(TMS)_22") (pintype "passive"))
    )
    (net (code "15") (name "/CURRENT+") (class "Default")
      (node (ref "C7") (pin "1") (pinfunction "1_1") (pintype "power_in"))
      (node (ref "D1") (pin "2") (pinfunction "2_2") (pintype "passive"))
      (node (ref "D2") (pin "2") (pinfunction "2_2") (pintype "passive"))
      (node (ref "R10") (pin "2") (pinfunction "2_2") (pintype "passive"))
      (node (ref "R11") (pin "2") (pinfunction "2_2") (pintype "passive"))
      (node (ref "R12") (pin "2") (pinfunction "2_2") (pintype "passive"))
      (node (ref "R13") (pin "2") (pinfunction "2_2") (pintype "passive"))
      (node (ref "U2") (pin "11") (pinfunction "IN+_11") (pintype "input"))
    )
    (net (code "16") (name "/CURRENT-") (class "Default")
      (node (ref "C10") (pin "2") (pinfunction "2_2") (pintype "power_in"))
      (node (ref "R19") (pin "1") (pinfunction "1_1") (pintype "passive"))
      (node (ref "R37") (pin "2") (pinfunction "2_2") (pintype "passive"))
      (node (ref "U2") (pin "10") (pinfunction "IN-_10") (pintype "input"))
    )
    (net (code "17") (name "/FAN_ON") (class "Default")
      (node (ref "R3") (pin "2") (pinfunction "2_2") (pintype "passive"))
      (node (ref "U12") (pin "20") (pinfunction "PC1_(SDA)_20") (pintype "passive"))
    )
    (net (code "18") (name "/HEALTH") (class "Default")
      (node (ref "LED1") (pin "2") (pinfunction "C_2") (pintype "passive"))
      (node (ref "U12") (pin "43") (pinfunction "PB3_(AIN1)_43") (pintype "passive"))
    )
    (net (code "19") (name "/I_LATCH") (class "Default")
      (node (ref "R113") (pin "2") (pinfunction "2_2") (pintype "passive"))
      (node (ref "R114") (pin "1") (pinfunction "1_1") (pintype "passive"))
      (node (ref "R124") (pin "1") (pinfunction "1_1") (pintype "passive"))
      (node (ref "U12") (pin "41") (pinfunction "PB1_(T1)_41") (pintype "passive"))
    )
    (net (code "20") (name "/I_PRIM") (class "Default")
      (node (ref "R6") (pin "1") (pinfunction "1_1") (pintype "passive"))
      (node (ref "R7") (pin "2") (pinfunction "2_2") (pintype "passive"))
      (node (ref "R98") (pin "2") (pinfunction "2_2") (pintype "passive"))
    )
    (net (code "21") (name "/I_PRIM_PA7") (class "Default")
      (node (ref "C54") (pin "1") (pinfunction "1_1") (pintype "power_in"))
      (node (ref "D21") (pin "3") (pinfunction "3_3") (pintype "passive"))
      (node (ref "R98") (pin "1") (pinfunction "1_1") (pintype "passive"))
      (node (ref "U12") (pin "30") (pinfunction "PA7_(ADC7)_30") (pintype "passive"))
    )
    (net (code "22") (name "/LIFT_PWM") (class "Default")
      (node (ref "R43") (pin "2") (pinfunction "2_2") (pintype "passive"))
      (node (ref "R50") (pin "2") (pinfunction "2_2") (pintype "passive"))
      (node (ref "U12") (pin "13") (pinfunction "PD4_(OC1B)_13") (pintype "passive"))
    )
    (net (code "23") (name "/MATRIX1") (class "Default")
      (node (ref "RC1") (pin "20") (pinfunction "20_20") (pintype "passive"))
      (node (ref "U12") (pin "15") (pinfunction "PD6_(ICP1)_15") (pintype "passive"))
    )
    (net (code "24") (name "/MATRIX2") (class "Default")
      (node (ref "RC1") (pin "22") (pinfunction "22_22") (pintype "passive"))
      (node (ref "U12") (pin "16") (pinfunction "PD7_(OC2)_16") (pintype "passive"))
    )
    (net (code "25") (name "/MATRIX3") (class "Default")
      (node (ref "RC1") (pin "21") (pinfunction "21_21") (pintype "passive"))
      (node (ref "U12") (pin "14") (pinfunction "PD5_(OC1A)_14") (pintype "passive"))
    )
    (net (code "26") (name "/MISO") (class "Default")
      (node (ref "R97") (pin "2") (pinfunction "2_2") (pintype "passive"))
      (node (ref "U12") (pin "2") (pinfunction "PB6_(MISO)_2") (pintype "passive"))
    )
    (net (code "27") (name "/MOSI") (class "Default")
      (node (ref "R32") (pin "1") (pinfunction "1_1") (pintype "passive"))
      (node (ref "R95") (pin "2") (pinfunction "2_2") (pintype "passive"))
      (node (ref "U12") (pin "1") (pinfunction "PB5_(MOSI)_1") (pintype "passive"))
    )
    (net (code "28") (name "/OSC1") (class "Default")
      (node (ref "C60") (pin "2") (pinfunction "2_2") (pintype "power_in"))
      (node (ref "R34") (pin "2") (pinfunction "2_2") (pintype "passive"))
      (node (ref "U12") (pin "8") (pinfunction "X1_8") (pintype "passive"))
      (node (ref "Y1") (pin "2") (pinfunction "2_2") (pintype "passive"))
    )
    (net (code "29") (name "/OSC2") (class "Default")
      (node (ref "C59") (pin "2") (pinfunction "2_2") (pintype "power_in"))
      (node (ref "R34") (pin "1") (pinfunction "1_1") (pintype "passive"))
      (node (ref "U12") (pin "7") (pinfunction "X2_7") (pintype "passive"))
      (node (ref "Y1") (pin "1") (pinfunction "1_1") (pintype "passive"))
    )
    (net (code "30") (name "/OVERTEMP") (class "Default")
      (node (ref "RC1") (pin "16") (pinfunction "16_16") (pintype "passive"))
      (node (ref "U12") (pin "23") (pinfunction "PC4_(TDO)_23") (pintype "passive"))
    )
    (net (code "31") (name "/POWER_LED") (class "Default")
      (node (ref "RC1") (pin "18") (pinfunction "18_18") (pintype "passive"))
      (node (ref "U12") (pin "24") (pinfunction "PC5_(TD1)_24") (pintype "passive"))
    )
    (net (code "32") (name "/RC3_3") (class "Default")
      (node (ref "R6") (pin "2") (pinfunction "2_2") (pintype "passive"))
      (node (ref "RC3") (pin "3") (pinfunction "3_3") (pintype "power_in"))
    )
    (net (code "33") (name "/RC7_1") (class "Default")
      (node (ref "R73") (pin "1") (pinfunction "1_1") (pintype "passive"))
      (node (ref "U12") (pin "40") (pinfunction "PB0_(T0)_40") (pintype "passive"))
    )
    (net (code "34") (name "/REF_POT") (class "Default")
      (node (ref "R96") (pin "2") (pinfunction "2_2") (pintype "passive"))
      (node (ref "RC1") (pin "10") (pinfunction "10_10") (pintype "passive"))
    )
    (net (code "35") (name "/REF_POT_PA6") (class "Default")
      (node (ref "C52") (pin "1") (pinfunction "1_1") (pintype "power_in"))
      (node (ref "D22") (pin "3") (pinfunction "3_3") (pintype "passive"))
      (node (ref "R96") (pin "1") (pinfunction "1_1") (pintype "passive"))
      (node (ref "U12") (pin "31") (pinfunction "PA6_(ADC6)_31") (pintype "passive"))
    )
    (net (code "36") (name "/REMOTE") (class "Default")
      (node (ref "R93") (pin "2") (pinfunction "2_2") (pintype "passive"))
      (node (ref "RC1") (pin "12") (pinfunction "12_12") (pintype "passive"))
    )
    (net (code "37") (name "/REMOTE_PA4") (class "Default")
      (node (ref "C49") (pin "1") (pinfunction "1_1") (pintype "power_in"))
      (node (ref "D24") (pin "3") (pinfunction "3_3") (pintype "passive"))
      (node (ref "R93") (pin "1") (pinfunction "1_1") (pintype "passive"))
      (node (ref "U12") (pin "33") (pinfunction "PA4_(ADC4)_33") (pintype "passive"))
    )
    (net (code "38") (name "/RXD") (class "Default")
      (node (ref "R2") (pin "2") (pinfunction "2_2") (pintype "passive"))
      (node (ref "U12") (pin "9") (pinfunction "PD0_(RXD)_9") (pintype "passive"))
    )
    (net (code "39") (name "/SCK") (class "Default")
      (node (ref "R31") (pin "1") (pinfunction "1_1") (pintype "passive"))
      (node (ref "R99") (pin "2") (pinfunction "2_2") (pintype "passive"))
      (node (ref "U12") (pin "3") (pinfunction "PB7_(SCK)_3") (pintype "passive"))
    )
    (net (code "40") (name "/SW1_1") (class "Default")
      (node (ref "R111") (pin "1") (pinfunction "1_1") (pintype "passive"))
      (node (ref "SW1") (pin "1") (pinfunction "1_1") (pintype "passive"))
      (node (ref "U12") (pin "25") (pinfunction "PC6_(OSC1)_25") (pintype "passive"))
    )
    (net (code "41") (name "/SW1_2") (class "Default")
      (node (ref "R106") (pin "1") (pinfunction "1_1") (pintype "passive"))
      (node (ref "SW1") (pin "2") (pinfunction "2_2") (pintype "passive"))
      (node (ref "U12") (pin "26") (pinfunction "PC7_(OSC2)_26") (pintype "passive"))
    )
    (net (code "42") (name "/THERM1") (class "Default")
      (node (ref "R81") (pin "1") (pinfunction "1_1") (pintype "passive"))
      (node (ref "R86") (pin "2") (pinfunction "2_2") (pintype "passive"))
      (node (ref "RC3") (pin "4") (pinfunction "4_4") (pintype "power_in"))
    )
    (net (code "43") (name "/THERM1_PA2") (class "Default")
      (node (ref "C44") (pin "1") (pinfunction "1_1") (pintype "power_in"))
      (node (ref "D26") (pin "3") (pinfunction "3_3") (pintype "passive"))
      (node (ref "R86") (pin "1") (pinfunction "1_1") (pintype "passive"))
      (node (ref "U12") (pin "35") (pinfunction "PA2_(ADC2)_35") (pintype "passive"))
    )
    (net (code "44") (name "/THERM2") (class "Default")
      (node (ref "R80") (pin "1") (pinfunction "1_1") (pintype "passive"))
      (node (ref "R85") (pin "2") (pinfunction "2_2") (pintype "passive"))
      (node (ref "RC3") (pin "5") (pinfunction "5_5") (pintype "power_in"))
    )
    (net (code "45") (name "/THERM2_PA3") (class "Default")
      (node (ref "C43") (pin "1") (pinfunction "1_1") (pintype "power_in"))
      (node (ref "D25") (pin "3") (pinfunction "3_3") (pintype "passive"))
      (node (ref "R85") (pin "1") (pinfunction "1_1") (pintype "passive"))
      (node (ref "U12") (pin "34") (pinfunction "PA3_(ADC3)_34") (pintype "passive"))
    )
    (net (code "46") (name "/THERM3") (class "Default")
      (node (ref "R91") (pin "1") (pinfunction "1_1") (pintype "passive"))
      (node (ref "R94") (pin "2") (pinfunction "2_2") (pintype "passive"))
      (node (ref "RC3") (pin "6") (pinfunction "6_6") (pintype "power_in"))
    )
    (net (code "47") (name "/THERM3_PA5") (class "Default")
      (node (ref "C51") (pin "1") (pinfunction "1_1") (pintype "power_in"))
      (node (ref "D23") (pin "3") (pinfunction "3_3") (pintype "passive"))
      (node (ref "R94") (pin "1") (pinfunction "1_1") (pintype "passive"))
      (node (ref "U12") (pin "32") (pinfunction "PA5_(ADC5)_32") (pintype "passive"))
    )
    (net (code "48") (name "/TXD") (class "Default")
      (node (ref "R1") (pin "2") (pinfunction "2_2") (pintype "passive"))
      (node (ref "U12") (pin "10") (pinfunction "PD1_(TXD)_10") (pintype "passive"))
    )
    (net (code "49") (name "/VFB") (class "Default")
      (node (ref "C14") (pin "1") (pinfunction "1_1") (pintype "power_in"))
      (node (ref "R30") (pin "2") (pinfunction "2_2") (pintype "passive"))
      (node (ref "R51") (pin "1") (pinfunction "1_1") (pintype "passive"))
      (node (ref "U5") (pin "1") (pinfunction "OUT_1") (pintype "power_in"))
      (node (ref "U5") (pin "5") (pinfunction "IN+_5") (pintype "input"))
    )
    (net (code "50") (name "/V_LATCH") (class "Default")
      (node (ref "D15") (pin "2") (pinfunction "C_2") (pintype "passive"))
      (node (ref "R47") (pin "2") (pinfunction "2_2") (pintype "passive"))
      (node (ref "U12") (pin "42") (pinfunction "PB2_(AIN0)_42") (pintype "passive"))
    )
    (net (code "51") (name "/{slash}BOOST_ON") (class "Default")
      (node (ref "C64") (pin "2") (pinfunction "2_2") (pintype "power_in"))
      (node (ref "R103") (pin "1") (pinfunction "1_1") (pintype "passive"))
      (node (ref "U12") (pin "19") (pinfunction "PC0_(SCL)_19") (pintype "passive"))
    )
    (net (code "52") (name "/{slash}CONTACTOR") (class "Default")
      (node (ref "Q14") (pin "3") (pinfunction "C_3") (pintype "passive"))
      (node (ref "R60") (pin "2") (pinfunction "2_2") (pintype "passive"))
      (node (ref "R70") (pin "1") (pinfunction "1_1") (pintype "passive"))
    )
    (net (code "53") (name "/{slash}DAC_SYNC") (class "Default")
      (node (ref "U10") (pin "1") (pinfunction "SYNC_1") (pintype "passive"))
      (node (ref "U12") (pin "44") (pinfunction "PB4_(nSS)_44") (pintype "passive"))
    )
    (net (code "54") (name "/{slash}READY") (class "Default")
      (node (ref "R104") (pin "2") (pinfunction "2_2") (pintype "passive"))
      (node (ref "U12") (pin "11") (pinfunction "PD2_(INT0)_11") (pintype "passive"))
    )
    (net (code "55") (name "/{slash}RESET") (class "Default")
      (node (ref "C55") (pin "2") (pinfunction "2_2") (pintype "power_in"))
      (node (ref "R89") (pin "2") (pinfunction "2_2") (pintype "passive"))
      (node (ref "R90") (pin "2") (pinfunction "2_2") (pintype "passive"))
      (node (ref "U12") (pin "4") (pinfunction "RST_4") (pintype "passive"))
    )
    (net (code "56") (name "GND") (class "Default")
      (node (ref "C10") (pin "1") (pinfunction "1_1") (pintype "power_in"))
      (node (ref "C13") (pin "1") (pinfunction "1_1") (pintype "power_in"))
      (node (ref "C16") (pin "1") (pinfunction "1_1") (pintype "power_in"))
      (node (ref "C17") (pin "1") (pinfunction "1_1") (pintype "power_in"))
      (node (ref "C18") (pin "1") (pinfunction "1_1") (pintype "power_in"))
      (node (ref "C19") (pin "1") (pinfunction "1_1") (pintype "power_in"))
      (node (ref "C21") (pin "1") (pinfunction "1_1") (pintype "power_in"))
      (node (ref "C23") (pin "2") (pinfunction "2_2") (pintype "power_in"))
      (node (ref "C24") (pin "1") (pinfunction "1_1") (pintype "power_in"))
      (node (ref "C27") (pin "1") (pinfunction "1_1") (pintype "power_in"))
      (node (ref "C28") (pin "1") (pinfunction "1_1") (pintype "power_in"))
      (node (ref "C29") (pin "1") (pinfunction "1_1") (pintype "power_in"))
      (node (ref "C3") (pin "1") (pinfunction "1_1") (pintype "power_in"))
      (node (ref "C30") (pin "1") (pinfunction "1_1") (pintype "power_in"))
      (node (ref "C32") (pin "2") (pinfunction "2_2") (pintype "power_in"))
      (node (ref "C33") (pin "2") (pinfunction "2_2") (pintype "power_in"))
      (node (ref "C34") (pin "1") (pinfunction "1_1") (pintype "power_in"))
      (node (ref "C36") (pin "1") (pinfunction "1_1") (pintype "power_in"))
      (node (ref "C38") (pin "2") (pinfunction "2_2") (pintype "power_in"))
      (node (ref "C39") (pin "1") (pinfunction "1_1") (pintype "power_in"))
      (node (ref "C4") (pin "1") (pinfunction "1_1") (pintype "power_in"))
      (node (ref "C40") (pin "1") (pinfunction "1_1") (pintype "power_in"))
      (node (ref "C41") (pin "1") (pinfunction "1_1") (pintype "power_in"))
      (node (ref "C42") (pin "1") (pinfunction "1_1") (pintype "power_in"))
      (node (ref "C43") (pin "2") (pinfunction "2_2") (pintype "power_in"))
      (node (ref "C44") (pin "2") (pinfunction "2_2") (pintype "power_in"))
      (node (ref "C45") (pin "2") (pinfunction "2_2") (pintype "power_in"))
      (node (ref "C46") (pin "2") (pinfunction "2_2") (pintype "power_in"))
      (node (ref "C47") (pin "1") (pinfunction "1_1") (pintype "power_in"))
      (node (ref "C48") (pin "2") (pinfunction "2_2") (pintype "power_in"))
      (node (ref "C49") (pin "2") (pinfunction "2_2") (pintype "power_in"))
      (node (ref "C50") (pin "1") (pinfunction "1_1") (pintype "power_in"))
      (node (ref "C51") (pin "2") (pinfunction "2_2") (pintype "power_in"))
      (node (ref "C52") (pin "2") (pinfunction "2_2") (pintype "power_in"))
      (node (ref "C53") (pin "1") (pinfunction "1_1") (pintype "power_in"))
      (node (ref "C54") (pin "2") (pinfunction "2_2") (pintype "power_in"))
      (node (ref "C55") (pin "1") (pinfunction "1_1") (pintype "power_in"))
      (node (ref "C56") (pin "1") (pinfunction "1_1") (pintype "power_in"))
      (node (ref "C57") (pin "2") (pinfunction "2_2") (pintype "power_in"))
      (node (ref "C58") (pin "2") (pinfunction "2_2") (pintype "power_in"))
      (node (ref "C59") (pin "1") (pinfunction "1_1") (pintype "power_in"))
      (node (ref "C6") (pin "2") (pinfunction "2_2") (pintype "power_in"))
      (node (ref "C60") (pin "1") (pinfunction "1_1") (pintype "power_in"))
      (node (ref "C61") (pin "1") (pinfunction "1_1") (pintype "power_in"))
      (node (ref "C62") (pin "1") (pinfunction "1_1") (pintype "power_in"))
      (node (ref "C63") (pin "2") (pinfunction "2_2") (pintype "power_in"))
      (node (ref "C65") (pin "2") (pinfunction "2_2") (pintype "power_in"))
      (node (ref "C66") (pin "2") (pinfunction "2_2") (pintype "power_in"))
      (node (ref "C67") (pin "1") (pinfunction "1_1") (pintype "power_in"))
      (node (ref "C68") (pin "2") (pinfunction "2_2") (pintype "power_in"))
      (node (ref "C7") (pin "2") (pinfunction "2_2") (pintype "power_in"))
      (node (ref "C8") (pin "1") (pinfunction "1_1") (pintype "power_in"))
      (node (ref "D1") (pin "1") (pinfunction "1_1") (pintype "passive"))
      (node (ref "D15") (pin "1") (pinfunction "A_1") (pintype "passive"))
      (node (ref "D2") (pin "1") (pinfunction "1_1") (pintype "passive"))
      (node (ref "D21") (pin "1") (pinfunction "1_1") (pintype "passive"))
      (node (ref "D22") (pin "1") (pinfunction "1_1") (pintype "passive"))
      (node (ref "D23") (pin "1") (pinfunction "1_1") (pintype "passive"))
      (node (ref "D24") (pin "1") (pinfunction "1_1") (pintype "passive"))
      (node (ref "D25") (pin "1") (pinfunction "1_1") (pintype "passive"))
      (node (ref "D26") (pin "1") (pinfunction "1_1") (pintype "passive"))
      (node (ref "D27") (pin "1") (pinfunction "1_1") (pintype "passive"))
      (node (ref "D28") (pin "1") (pinfunction "1_1") (pintype "passive"))
      (node (ref "D6") (pin "1") (pinfunction "1_1") (pintype "passive"))
      (node (ref "LED4") (pin "2") (pinfunction "C_2") (pintype "passive"))
      (node (ref "LED5") (pin "1") (pinfunction "A_1") (pintype "passive"))
      (node (ref "LED6") (pin "2") (pinfunction "C_2") (pintype "passive"))
      (node (ref "PGM") (pin "6") (pinfunction "6_6") (pintype "power_in"))
      (node (ref "Q10") (pin "2") (pinfunction "E_2") (pintype "passive"))
      (node (ref "Q11") (pin "2") (pinfunction "E_2") (pintype "passive"))
      (node (ref "Q14") (pin "2") (pinfunction "E_2") (pintype "passive"))
      (node (ref "Q15") (pin "2") (pinfunction "E_2") (pintype "passive"))
      (node (ref "Q7") (pin "2") (pinfunction "E_2") (pintype "passive"))
      (node (ref "Q8") (pin "2") (pinfunction "S_2") (pintype "passive"))
      (node (ref "R10") (pin "1") (pinfunction "1_1") (pintype "passive"))
      (node (ref "R101") (pin "1") (pinfunction "1_1") (pintype "passive"))
      (node (ref "R11") (pin "1") (pinfunction "1_1") (pintype "passive"))
      (node (ref "R110") (pin "1") (pinfunction "1_1") (pintype "passive"))
      (node (ref "R113") (pin "1") (pinfunction "1_1") (pintype "passive"))
      (node (ref "R115") (pin "1") (pinfunction "1_1") (pintype "passive"))
      (node (ref "R12") (pin "1") (pinfunction "1_1") (pintype "passive"))
      (node (ref "R120") (pin "1") (pinfunction "1_1") (pintype "passive"))
      (node (ref "R13") (pin "1") (pinfunction "1_1") (pintype "passive"))
      (node (ref "R130") (pin "1") (pinfunction "1_1") (pintype "passive"))
      (node (ref "R17") (pin "1") (pinfunction "1_1") (pintype "passive"))
      (node (ref "R20") (pin "1") (pinfunction "1_1") (pintype "passive"))
      (node (ref "R23") (pin "1") (pinfunction "1_1") (pintype "passive"))
      (node (ref "R26") (pin "2") (pinfunction "2_2") (pintype "passive"))
      (node (ref "R29") (pin "1") (pinfunction "1_1") (pintype "passive"))
      (node (ref "R41") (pin "1") (pinfunction "1_1") (pintype "passive"))
      (node (ref "R45") (pin "1") (pinfunction "1_1") (pintype "passive"))
      (node (ref "R50") (pin "1") (pinfunction "1_1") (pintype "passive"))
      (node (ref "R57*") (pin "1") (pinfunction "1_1") (pintype "passive"))
      (node (ref "R58") (pin "1") (pinfunction "1_1") (pintype "passive"))
      (node (ref "R63") (pin "1") (pinfunction "1_1") (pintype "passive"))
      (node (ref "R68") (pin "1") (pinfunction "1_1") (pintype "passive"))
      (node (ref "R7") (pin "1") (pinfunction "1_1") (pintype "passive"))
      (node (ref "R78") (pin "1") (pinfunction "1_1") (pintype "passive"))
      (node (ref "R79") (pin "1") (pinfunction "1_1") (pintype "passive"))
      (node (ref "RC1") (pin "11") (pinfunction "11_11") (pintype "passive"))
      (node (ref "RC1") (pin "13") (pinfunction "13_13") (pintype "passive"))
      (node (ref "RC1") (pin "15") (pinfunction "15_15") (pintype "passive"))
      (node (ref "RC1") (pin "17") (pinfunction "17_17") (pintype "passive"))
      (node (ref "RC1") (pin "19") (pinfunction "19_19") (pintype "passive"))
      (node (ref "RC1") (pin "5") (pinfunction "5_5") (pintype "passive"))
      (node (ref "RC1") (pin "7") (pinfunction "7_7") (pintype "passive"))
      (node (ref "RC1") (pin "9") (pinfunction "9_9") (pintype "passive"))
      (node (ref "RC3") (pin "1") (pinfunction "1_1") (pintype "passive"))
      (node (ref "RC3") (pin "7") (pinfunction "7_7") (pintype "power_in"))
      (node (ref "RC4") (pin "1") (pinfunction "1_1") (pintype "passive"))
      (node (ref "RC4") (pin "2") (pinfunction "2_2") (pintype "passive"))
      (node (ref "RC4") (pin "7") (pinfunction "7_7") (pintype "power_in"))
      (node (ref "RC5") (pin "6") (pinfunction "6_6") (pintype "power_in"))
      (node (ref "RC7") (pin "2") (pinfunction "2_2") (pintype "passive"))
      (node (ref "SW1") (pin "3") (pinfunction "3_3") (pintype "passive"))
      (node (ref "SW1") (pin "4") (pinfunction "4_4") (pintype "passive"))
      (node (ref "T1") (pin "2") (pinfunction "2_2") (pintype "power_in"))
      (node (ref "U1") (pin "7") (pintype "passive"))
      (node (ref "U10") (pin "5") (pinfunction "GND_5") (pintype "passive"))
      (node (ref "U11") (pin "2") (pintype "passive"))
      (node (ref "U12") (pin "18") (pinfunction "GND_18") (pintype "passive"))
      (node (ref "U12") (pin "28") (pinfunction "GND_28") (pintype "passive"))
      (node (ref "U12") (pin "39") (pinfunction "GND_39") (pintype "passive"))
      (node (ref "U12") (pin "6") (pinfunction "GND_6") (pintype "passive"))
      (node (ref "U13") (pin "2") (pinfunction "GND_2") (pintype "passive"))
      (node (ref "U13") (pin "4") (pinfunction "GND_4") (pintype "passive"))
      (node (ref "U14") (pin "2") (pinfunction "GND_2") (pintype "passive"))
      (node (ref "U15") (pin "4") (pinfunction "V-_4") (pintype "power_in"))
      (node (ref "U16") (pin "3") (pinfunction "GND_3") (pintype "passive"))
      (node (ref "U2") (pin "12") (pinfunction "V-_12") (pintype "power_in"))
      (node (ref "U3") (pin "7") (pinfunction "GND_7") (pintype "passive"))
      (node (ref "U4") (pin "7") (pintype "power_in"))
      (node (ref "U7") (pin "12") (pinfunction "IN+_12") (pintype "input"))
      (node (ref "U7") (pin "5") (pinfunction "IN+_5") (pintype "input"))
      (node (ref "U8") (pin "4") (pinfunction "V-_4") (pintype "power_in"))
      (node (ref "U9") (pin "4") (pinfunction "GND_4") (pintype "passive"))
      (node (ref "UART") (pin "4") (pinfunction "4_4") (pintype "power_in"))
      (node (ref "VO1") (pin "2") (pinfunction "C_2") (pintype "passive"))
    )
    (net (code "57") (name "Net-(C8-Pad2)") (class "Default")
      (node (ref "C8") (pin "2") (pinfunction "2_2") (pintype "power_in"))
      (node (ref "R33") (pin "1") (pinfunction "1_1") (pintype "passive"))
      (node (ref "U1") (pin "8") (pintype "passive"))
      (node (ref "U1") (pin "9") (pintype "passive"))
    )
    (net (code "58") (name "Net-(C11-Pad1)") (class "Default")
      (node (ref "C11") (pin "1") (pinfunction "1_1") (pintype "power_in"))
      (node (ref "C20") (pin "1") (pinfunction "1_1") (pintype "power_in"))
      (node (ref "C22") (pin "1") (pinfunction "1_1") (pintype "power_in"))
      (node (ref "D5") (pin "2") (pinfunction "2_2") (pintype "passive"))
      (node (ref "L1") (pin "1") (pinfunction "1_1") (pintype "passive"))
      (node (ref "R39") (pin "1") (pinfunction "1_1") (pintype "passive"))
      (node (ref "RC2") (pin "1") (pinfunction "1_1") (pintype "passive"))
    )
    (net (code "59") (name "Net-(C15-Pad2)") (class "Default")
      (node (ref "C15") (pin "2") (pinfunction "2_2") (pintype "power_in"))
      (node (ref "R52") (pin "1") (pinfunction "1_1") (pintype "passive"))
    )
    (net (code "60") (name "Net-(C20-Pad2)") (class "Default")
      (node (ref "C20") (pin "2") (pinfunction "2_2") (pintype "power_in"))
      (node (ref "R53") (pin "1") (pinfunction "1_1") (pintype "passive"))
    )
    (net (code "61") (name "Net-(C32-Pad1)") (class "Default")
      (node (ref "C32") (pin "1") (pinfunction "1_1") (pintype "power_in"))
      (node (ref "D11") (pin "2") (pinfunction "2_2") (pintype "passive"))
      (node (ref "R44") (pin "1") (pinfunction "1_1") (pintype "passive"))
      (node (ref "R58") (pin "2") (pinfunction "2_2") (pintype "passive"))
    )
    (net (code "62") (name "Net-(C35-Pad2)") (class "Default")
      (node (ref "C35") (pin "2") (pinfunction "2_2") (pintype "power_in"))
      (node (ref "R71") (pin "2") (pinfunction "2_2") (pintype "passive"))
    )
    (net (code "63") (name "Net-(C64-Pad1)") (class "Default")
      (node (ref "C64") (pin "1") (pinfunction "1_1") (pintype "power_in"))
      (node (ref "D19") (pin "2") (pinfunction "2_2") (pintype "passive"))
      (node (ref "D20") (pin "1") (pinfunction "1_1") (pintype "passive"))
    )
    (net (code "64") (name "Net-(C65-Pad1)") (class "Default")
      (node (ref "C65") (pin "1") (pinfunction "1_1") (pintype "power_in"))
      (node (ref "R104") (pin "1") (pinfunction "1_1") (pintype "passive"))
      (node (ref "R105") (pin "2") (pinfunction "2_2") (pintype "passive"))
      (node (ref "RC4") (pin "6") (pinfunction "6_6") (pintype "power_in"))
    )
    (net (code "65") (name "Net-(D1-Pad3)") (class "Default")
      (node (ref "D1") (pin "3") (pinfunction "3_3") (pintype "passive"))
      (node (ref "RC3") (pin "9") (pinfunction "9_9") (pintype "power_in"))
    )
    (net (code "66") (name "Net-(D2-Pad3)") (class "Default")
      (node (ref "D2") (pin "3") (pinfunction "3_3") (pintype "passive"))
      (node (ref "RC3") (pin "10") (pinfunction "10_10") (pintype "power_in"))
    )
    (net (code "67") (name "Net-(D4-Pad1)") (class "Default")
      (node (ref "D4") (pin "1") (pinfunction "1_1") (pintype "passive"))
      (node (ref "T1") (pin "6") (pinfunction "6_6") (pintype "power_in"))
    )
    (net (code "68") (name "Net-(D4-Pad2)") (class "Default")
      (node (ref "D4") (pin "2") (pinfunction "2_2") (pintype "passive"))
      (node (ref "R8") (pin "2") (pinfunction "2_2") (pintype "passive"))
    )
    (net (code "69") (name "Net-(D8-Pad1)") (class "Default")
      (node (ref "D8") (pin "1") (pinfunction "1_1") (pintype "passive"))
      (node (ref "T1") (pin "5") (pinfunction "5_5") (pintype "power_in"))
    )
    (net (code "70") (name "Net-(D17-A)") (class "Default")
      (node (ref "D17") (pin "1") (pinfunction "A_1") (pintype "passive"))
      (node (ref "R71") (pin "1") (pinfunction "1_1") (pintype "passive"))
      (node (ref "R72") (pin "2") (pinfunction "2_2") (pintype "passive"))
      (node (ref "U7") (pin "6") (pinfunction "IN-_6") (pintype "input"))
    )
    (net (code "71") (name "Net-(D17-C)") (class "Default")
      (node (ref "C35") (pin "1") (pinfunction "1_1") (pintype "power_in"))
      (node (ref "D16") (pin "2") (pinfunction "2_2") (pintype "passive"))
      (node (ref "D17") (pin "2") (pinfunction "C_2") (pintype "passive"))
      (node (ref "R69") (pin "1") (pinfunction "1_1") (pintype "passive"))
      (node (ref "U7") (pin "7") (pinfunction "OUT_7") (pintype "power_in"))
    )
    (net (code "72") (name "Net-(LED1-A)") (class "Default")
      (node (ref "LED1") (pin "1") (pinfunction "A_1") (pintype "passive"))
      (node (ref "R123") (pin "1") (pinfunction "1_1") (pintype "passive"))
    )
    (net (code "73") (name "Net-(LED2-A)") (class "Default")
      (node (ref "LED2") (pin "1") (pinfunction "A_1") (pintype "passive"))
      (node (ref "R25") (pin "2") (pinfunction "2_2") (pintype "passive"))
      (node (ref "U3") (pin "13") (pinfunction "Q_13") (pintype "passive"))
    )
    (net (code "74") (name "Net-(LED2-C)") (class "Default")
      (node (ref "LED2") (pin "2") (pinfunction "C_2") (pintype "passive"))
      (node (ref "R124") (pin "2") (pinfunction "2_2") (pintype "passive"))
    )
    (net (code "75") (name "Net-(LED3-A)") (class "Default")
      (node (ref "LED3") (pin "1") (pinfunction "A_1") (pintype "passive"))
      (node (ref "R125") (pin "1") (pinfunction "1_1") (pintype "passive"))
    )
    (net (code "76") (name "Net-(LED3-C)") (class "Default")
      (node (ref "D7") (pin "2") (pinfunction "2_2") (pintype "passive"))
      (node (ref "LED3") (pin "2") (pinfunction "C_2") (pintype "passive"))
      (node (ref "U2") (pin "14") (pinfunction "OUT_14") (pintype "power_in"))
      (node (ref "U4") (pin "11") (pintype "passive"))
      (node (ref "U4") (pin "12") (pintype "passive"))
      (node (ref "U4") (pin "13") (pintype "passive"))
    )
    (net (code "77") (name "Net-(LED4-A)") (class "Default")
      (node (ref "LED4") (pin "1") (pinfunction "A_1") (pintype "passive"))
      (node (ref "R126") (pin "1") (pinfunction "1_1") (pintype "passive"))
    )
    (net (code "78") (name "Net-(LED5-C)") (class "Default")
      (node (ref "LED5") (pin "2") (pinfunction "C_2") (pintype "passive"))
      (node (ref "R127") (pin "2") (pinfunction "2_2") (pintype "passive"))
    )
    (net (code "79") (name "Net-(LED6-A)") (class "Default")
      (node (ref "LED6") (pin "1") (pinfunction "A_1") (pintype "passive"))
      (node (ref "R128") (pin "1") (pinfunction "1_1") (pintype "passive"))
    )
    (net (code "80") (name "Net-(PGM-Pad2)") (class "Default")
      (node (ref "PGM") (pin "2") (pinfunction "2_2") (pintype "passive"))
      (node (ref "R90") (pin "1") (pinfunction "1_1") (pintype "passive"))
    )
    (net (code "81") (name "Net-(PGM-Pad3)") (class "Default")
      (node (ref "PGM") (pin "3") (pinfunction "3_3") (pintype "power_in"))
      (node (ref "R99") (pin "1") (pinfunction "1_1") (pintype "passive"))
    )
    (net (code "82") (name "Net-(PGM-Pad4)") (class "Default")
      (node (ref "PGM") (pin "4") (pinfunction "4_4") (pintype "power_in"))
      (node (ref "R95") (pin "1") (pinfunction "1_1") (pintype "passive"))
    )
    (net (code "83") (name "Net-(PGM-Pad5)") (class "Default")
      (node (ref "PGM") (pin "5") (pinfunction "5_5") (pintype "power_in"))
      (node (ref "R97") (pin "1") (pinfunction "1_1") (pintype "passive"))
    )
    (net (code "84") (name "Net-(Q5-C)") (class "Default")
      (node (ref "D3") (pin "1") (pinfunction "1_1") (pintype "passive"))
      (node (ref "Q5") (pin "3") (pinfunction "C_3") (pintype "passive"))
      (node (ref "R4") (pin "1") (pinfunction "1_1") (pintype "passive"))
      (node (ref "R5") (pin "1") (pinfunction "1_1") (pintype "passive"))
      (node (ref "R9") (pin "1") (pinfunction "1_1") (pintype "passive"))
    )
    (net (code "85") (name "Net-(Q7-B)") (class "Default")
      (node (ref "Q7") (pin "1") (pinfunction "B_1") (pintype "passive"))
      (node (ref "R25") (pin "1") (pinfunction "1_1") (pintype "passive"))
      (node (ref "R26") (pin "1") (pinfunction "1_1") (pintype "passive"))
    )
    (net (code "86") (name "Net-(Q7-C)") (class "Default")
      (node (ref "Q7") (pin "3") (pinfunction "C_3") (pintype "passive"))
      (node (ref "R35") (pin "1") (pinfunction "1_1") (pintype "passive"))
      (node (ref "U4") (pin "2") (pintype "passive"))
      (node (ref "U4") (pin "4") (pintype "passive"))
    )
    (net (code "87") (name "Net-(Q8-D)") (class "Default")
      (node (ref "Q8") (pin "3") (pinfunction "D_3") (pintype "passive"))
      (node (ref "T1") (pin "4") (pinfunction "4_4") (pintype "power_in"))
    )
    (net (code "88") (name "Net-(Q8-G)") (class "Default")
      (node (ref "Q8") (pin "1") (pinfunction "G_1") (pintype "passive"))
      (node (ref "R43") (pin "1") (pinfunction "1_1") (pintype "passive"))
    )
    (net (code "89") (name "Net-(Q9-E)") (class "Default")
      (node (ref "Q9") (pin "2") (pinfunction "E_2") (pintype "passive"))
      (node (ref "R59") (pin "1") (pinfunction "1_1") (pintype "passive"))
    )
    (net (code "90") (name "Net-(Q10-B)") (class "Default")
      (node (ref "D16") (pin "1") (pinfunction "1_1") (pintype "passive"))
      (node (ref "Q10") (pin "1") (pinfunction "B_1") (pintype "passive"))
      (node (ref "Q11") (pin "3") (pinfunction "C_3") (pintype "passive"))
      (node (ref "R14") (pin "2") (pinfunction "2_2") (pintype "passive"))
    )
    (net (code "91") (name "Net-(Q10-C)") (class "Default")
      (node (ref "C33") (pin "1") (pinfunction "1_1") (pintype "power_in"))
      (node (ref "Q10") (pin "3") (pinfunction "C_3") (pintype "passive"))
      (node (ref "Q9") (pin "3") (pinfunction "C_3") (pintype "passive"))
      (node (ref "U2") (pin "4") (pinfunction "IN-_4") (pintype "input"))
      (node (ref "U2") (pin "6") (pinfunction "IN-_6") (pintype "input"))
    )
    (net (code "92") (name "Net-(Q11-B)") (class "Default")
      (node (ref "Q11") (pin "1") (pinfunction "B_1") (pintype "passive"))
      (node (ref "R15") (pin "2") (pinfunction "2_2") (pintype "passive"))
      (node (ref "R46") (pin "2") (pinfunction "2_2") (pintype "passive"))
      (node (ref "R60") (pin "1") (pinfunction "1_1") (pintype "passive"))
    )
    (net (code "93") (name "Net-(Q12-B)") (class "Default")
      (node (ref "Q12") (pin "1") (pinfunction "B_1") (pintype "passive"))
      (node (ref "Q12") (pin "3") (pinfunction "C_3") (pintype "passive"))
      (node (ref "Q9") (pin "1") (pinfunction "B_1") (pintype "passive"))
      (node (ref "R68") (pin "2") (pinfunction "2_2") (pintype "passive"))
    )
    (net (code "94") (name "Net-(Q12-E)") (class "Default")
      (node (ref "Q12") (pin "2") (pinfunction "E_2") (pintype "passive"))
      (node (ref "R67") (pin "1") (pinfunction "1_1") (pintype "passive"))
    )
    (net (code "95") (name "Net-(Q14-B)") (class "Default")
      (node (ref "Q14") (pin "1") (pinfunction "B_1") (pintype "passive"))
      (node (ref "R101") (pin "2") (pinfunction "2_2") (pintype "passive"))
      (node (ref "R102") (pin "1") (pinfunction "1_1") (pintype "passive"))
    )
    (net (code "96") (name "Net-(Q15-B)") (class "Default")
      (node (ref "Q15") (pin "1") (pinfunction "B_1") (pintype "passive"))
      (node (ref "R114") (pin "2") (pinfunction "2_2") (pintype "passive"))
      (node (ref "R115") (pin "2") (pinfunction "2_2") (pintype "passive"))
    )
    (net (code "97") (name "Net-(Q15-C)") (class "Default")
      (node (ref "Q15") (pin "3") (pinfunction "C_3") (pintype "passive"))
      (node (ref "R24") (pin "1") (pinfunction "1_1") (pintype "passive"))
      (node (ref "U3") (pin "11") (pinfunction "C_11") (pintype "passive"))
    )
    (net (code "98") (name "Net-(Q16-B)") (class "Default")
      (node (ref "C68") (pin "1") (pinfunction "1_1") (pintype "power_in"))
      (node (ref "D19") (pin "1") (pinfunction "1_1") (pintype "passive"))
      (node (ref "Q16") (pin "1") (pinfunction "B_1") (pintype "passive"))
      (node (ref "R119") (pin "1") (pinfunction "1_1") (pintype "passive"))
    )
    (net (code "99") (name "Net-(Q16-C)") (class "Default")
      (node (ref "Q16") (pin "3") (pinfunction "C_3") (pintype "passive"))
      (node (ref "Q5") (pin "1") (pinfunction "B_1") (pintype "passive"))
      (node (ref "R16") (pin "2") (pinfunction "2_2") (pintype "passive"))
    )
    (net (code "100") (name "Net-(Q16-E)") (class "Default")
      (node (ref "Q16") (pin "2") (pinfunction "E_2") (pintype "passive"))
      (node (ref "R112") (pin "1") (pinfunction "1_1") (pintype "passive"))
      (node (ref "R118") (pin "1") (pinfunction "1_1") (pintype "passive"))
    )
    (net (code "101") (name "Net-(R1-Pad1)") (class "Default")
      (node (ref "R1") (pin "1") (pinfunction "1_1") (pintype "passive"))
      (node (ref "UART") (pin "2") (pinfunction "2_2") (pintype "passive"))
    )
    (net (code "102") (name "Net-(R2-Pad1)") (class "Default")
      (node (ref "R2") (pin "1") (pinfunction "1_1") (pintype "passive"))
      (node (ref "UART") (pin "3") (pinfunction "3_3") (pintype "power_in"))
    )
    (net (code "103") (name "Net-(R4-Pad2)") (class "Default")
      (node (ref "R4") (pin "2") (pinfunction "2_2") (pintype "passive"))
      (node (ref "R5") (pin "2") (pinfunction "2_2") (pintype "passive"))
      (node (ref "R9") (pin "2") (pinfunction "2_2") (pintype "passive"))
      (node (ref "RC3") (pin "11") (pinfunction "11_11") (pintype "power_in"))
    )
    (net (code "104") (name "Net-(R15-Pad1)") (class "Default")
      (node (ref "R15") (pin "1") (pinfunction "1_1") (pintype "passive"))
      (node (ref "U1") (pin "11") (pintype "passive"))
    )
    (net (code "105") (name "Net-(R35-Pad2)") (class "Default")
      (node (ref "R35") (pin "2") (pinfunction "2_2") (pintype "passive"))
      (node (ref "U1") (pin "3") (pintype "passive"))
      (node (ref "U1") (pin "5") (pintype "passive"))
    )
    (net (code "106") (name "Net-(R46-Pad1)") (class "Default")
      (node (ref "R46") (pin "1") (pinfunction "1_1") (pintype "passive"))
      (node (ref "R47") (pin "1") (pinfunction "1_1") (pintype "passive"))
      (node (ref "U4") (pin "10") (pintype "passive"))
    )
    (net (code "107") (name "Net-(R61-Pad1)") (class "Default")
      (node (ref "R61") (pin "1") (pinfunction "1_1") (pintype "passive"))
      (node (ref "RC5") (pin "3") (pinfunction "3_3") (pintype "power_in"))
    )
    (net (code "108") (name "Net-(R64-Pad2)") (class "Default")
      (node (ref "R64") (pin "2") (pinfunction "2_2") (pintype "passive"))
      (node (ref "R65") (pin "1") (pinfunction "1_1") (pintype "passive"))
    )
    (net (code "109") (name "Net-(R73-Pad2)") (class "Default")
      (node (ref "R73") (pin "2") (pinfunction "2_2") (pintype "passive"))
      (node (ref "RC7") (pin "1") (pinfunction "1_1") (pintype "passive"))
    )
    (net (code "110") (name "Net-(R92-Pad1)") (class "Default")
      (node (ref "R92") (pin "1") (pinfunction "1_1") (pintype "passive"))
      (node (ref "RC1") (pin "8") (pinfunction "8_8") (pintype "passive"))
    )
    (net (code "111") (name "Net-(R132-Pad1)") (class "Default")
      (node (ref "R132") (pin "1") (pinfunction "1_1") (pintype "passive"))
      (node (ref "RC4") (pin "4") (pinfunction "4_4") (pintype "power_in"))
    )
    (net (code "112") (name "Net-(R133-Pad1)") (class "Default")
      (node (ref "R133") (pin "1") (pinfunction "1_1") (pintype "passive"))
      (node (ref "RC4") (pin "8") (pinfunction "8_8") (pintype "power_in"))
    )
    (net (code "113") (name "Net-(U1-Pad2)") (class "Default")
      (node (ref "U1") (pin "2") (pintype "passive"))
      (node (ref "U1") (pin "4") (pintype "passive"))
    )
    (net (code "114") (name "Net-(U2A-IN+)") (class "Default")
      (node (ref "C23") (pin "1") (pinfunction "1_1") (pintype "power_in"))
      (node (ref "D13") (pin "2") (pinfunction "2_2") (pintype "passive"))
      (node (ref "R69") (pin "2") (pinfunction "2_2") (pintype "passive"))
      (node (ref "U2") (pin "5") (pinfunction "IN+_5") (pintype "input"))
    )
    (net (code "115") (name "Net-(U2A-OUT)") (class "Default")
      (node (ref "R18") (pin "1") (pinfunction "1_1") (pintype "passive"))
      (node (ref "U1") (pin "6") (pintype "passive"))
      (node (ref "U2") (pin "2") (pinfunction "OUT_2") (pintype "power_in"))
    )
    (net (code "116") (name "Net-(U2B-IN+)") (class "Default")
      (node (ref "D11") (pin "1") (pinfunction "1_1") (pintype "passive"))
      (node (ref "D12") (pin "1") (pinfunction "1_1") (pintype "passive"))
      (node (ref "R38") (pin "1") (pinfunction "1_1") (pintype "passive"))
      (node (ref "U2") (pin "7") (pinfunction "IN+_7") (pintype "input"))
    )
    (net (code "117") (name "Net-(U2B-OUT)") (class "Default")
      (node (ref "D12") (pin "2") (pinfunction "2_2") (pintype "passive"))
      (node (ref "R33") (pin "2") (pinfunction "2_2") (pintype "passive"))
      (node (ref "R36") (pin "1") (pinfunction "1_1") (pintype "passive"))
      (node (ref "U1") (pin "1") (pintype "passive"))
      (node (ref "U2") (pin "1") (pinfunction "OUT_1") (pintype "power_in"))
      (node (ref "U4") (pin "1") (pintype "passive"))
      (node (ref "U4") (pin "3") (pintype "passive"))
    )
    (net (code "118") (name "Net-(U2C-IN+)") (class "Default")
      (node (ref "D7") (pin "1") (pinfunction "1_1") (pintype "passive"))
      (node (ref "R17") (pin "2") (pinfunction "2_2") (pintype "passive"))
      (node (ref "R21") (pin "1") (pinfunction "1_1") (pintype "passive"))
      (node (ref "U2") (pin "9") (pinfunction "IN+_9") (pintype "input"))
    )
    (net (code "119") (name "Net-(U2C-IN-)") (class "Default")
      (node (ref "D14") (pin "2") (pinfunction "2_2") (pintype "passive"))
      (node (ref "R20") (pin "2") (pinfunction "2_2") (pintype "passive"))
      (node (ref "R55") (pin "1") (pinfunction "1_1") (pintype "passive"))
      (node (ref "U2") (pin "8") (pinfunction "IN-_8") (pintype "input"))
    )
    (net (code "120") (name "Net-(U2D-OUT)") (class "Default")
      (node (ref "R22") (pin "1") (pinfunction "1_1") (pintype "passive"))
      (node (ref "U2") (pin "13") (pinfunction "OUT_13") (pintype "power_in"))
      (node (ref "U3") (pin "8") (pinfunction "S_8") (pintype "passive"))
    )
    (net (code "121") (name "Net-(U3A-C)") (class "Default")
      (node (ref "D13") (pin "1") (pinfunction "1_1") (pintype "passive"))
      (node (ref "R14") (pin "1") (pinfunction "1_1") (pintype "passive"))
      (node (ref "U1") (pin "10") (pintype "passive"))
      (node (ref "U3") (pin "3") (pinfunction "C_3") (pintype "passive"))
    )
    (net (code "122") (name "Net-(U3A-D)") (class "Default")
      (node (ref "U3") (pin "2") (pinfunction "/Q_2") (pintype "passive"))
      (node (ref "U3") (pin "5") (pinfunction "D_5") (pintype "passive"))
      (node (ref "U4") (pin "5") (pintype "passive"))
    )
    (net (code "123") (name "Net-(U3A-Q)") (class "Default")
      (node (ref "U3") (pin "1") (pinfunction "Q_1") (pintype "passive"))
      (node (ref "U4") (pin "8") (pintype "passive"))
    )
    (net (code "124") (name "Net-(U3A-R)") (class "Default")
      (node (ref "R45") (pin "2") (pinfunction "2_2") (pintype "passive"))
      (node (ref "U3") (pin "4") (pinfunction "R_4") (pintype "passive"))
      (node (ref "U3") (pin "6") (pinfunction "S_6") (pintype "passive"))
    )
    (net (code "125") (name "Net-(U3B-D)") (class "Default")
      (node (ref "R23") (pin "2") (pinfunction "2_2") (pintype "passive"))
      (node (ref "U3") (pin "10") (pinfunction "R_10") (pintype "passive"))
      (node (ref "U3") (pin "9") (pinfunction "D_9") (pintype "passive"))
    )
    (net (code "126") (name "Net-(U5A-IN+)") (class "Default")
      (node (ref "C13") (pin "2") (pinfunction "2_2") (pintype "power_in"))
      (node (ref "D9") (pin "3") (pinfunction "3_3") (pintype "passive"))
      (node (ref "R27") (pin "2") (pinfunction "2_2") (pintype "passive"))
      (node (ref "R29") (pin "2") (pinfunction "2_2") (pintype "passive"))
      (node (ref "U5") (pin "3") (pinfunction "IN+_3") (pintype "input"))
    )
    (net (code "127") (name "Net-(U5A-IN-)") (class "Default")
      (node (ref "C14") (pin "2") (pinfunction "2_2") (pintype "power_in"))
      (node (ref "D10") (pin "3") (pinfunction "3_3") (pintype "passive"))
      (node (ref "R28") (pin "1") (pinfunction "1_1") (pintype "passive"))
      (node (ref "R30") (pin "1") (pinfunction "1_1") (pintype "passive"))
      (node (ref "U5") (pin "2") (pinfunction "IN-_2") (pintype "input"))
    )
    (net (code "128") (name "Net-(U5B-IN-)") (class "Default")
      (node (ref "C31") (pin "2") (pinfunction "2_2") (pintype "power_in"))
      (node (ref "R63") (pin "2") (pinfunction "2_2") (pintype "passive"))
      (node (ref "R64") (pin "1") (pinfunction "1_1") (pintype "passive"))
      (node (ref "U5") (pin "6") (pinfunction "IN-_6") (pintype "input"))
    )
    (net (code "129") (name "Net-(U5B-OUT)") (class "Default")
      (node (ref "C31") (pin "1") (pinfunction "1_1") (pintype "power_in"))
      (node (ref "D14") (pin "1") (pinfunction "1_1") (pintype "passive"))
      (node (ref "U5") (pin "7") (pinfunction "OUT_7") (pintype "power_in"))
    )
    (net (code "130") (name "Net-(U7A-IN-)") (class "Default")
      (node (ref "C37") (pin "2") (pinfunction "2_2") (pintype "power_in"))
      (node (ref "R75") (pin "2") (pinfunction "2_2") (pintype "passive"))
      (node (ref "U7") (pin "2") (pinfunction "IN-_2") (pintype "input"))
    )
    (net (code "131") (name "Net-(U7A-OUT)") (class "Default")
      (node (ref "C37") (pin "1") (pinfunction "1_1") (pintype "power_in"))
      (node (ref "R76") (pin "2") (pinfunction "2_2") (pintype "passive"))
      (node (ref "U7") (pin "1") (pinfunction "OUT_1") (pintype "power_in"))
    )
    (net (code "132") (name "Net-(U7C-IN+)") (class "Default")
      (node (ref "C29") (pin "2") (pinfunction "2_2") (pintype "power_in"))
      (node (ref "R40") (pin "2") (pinfunction "2_2") (pintype "passive"))
      (node (ref "R41") (pin "2") (pinfunction "2_2") (pintype "passive"))
      (node (ref "U7") (pin "10") (pinfunction "IN+_10") (pintype "input"))
    )
    (net (code "133") (name "Net-(U7C-IN-)") (class "Default")
      (node (ref "C26*") (pin "2") (pinfunction "2_2") (pintype "power_in"))
      (node (ref "R49") (pin "1") (pinfunction "1_1") (pintype "passive"))
      (node (ref "R62") (pin "2") (pinfunction "2_2") (pintype "passive"))
      (node (ref "U7") (pin "9") (pinfunction "IN-_9") (pintype "input"))
    )
    (net (code "134") (name "Net-(U7C-OUT)") (class "Default")
      (node (ref "C26*") (pin "1") (pinfunction "1_1") (pintype "power_in"))
      (node (ref "R49") (pin "2") (pinfunction "2_2") (pintype "passive"))
      (node (ref "R72") (pin "1") (pinfunction "1_1") (pintype "passive"))
      (node (ref "U7") (pin "8") (pinfunction "OUT_8") (pintype "power_in"))
    )
    (net (code "135") (name "Net-(U7D-IN-)") (class "Default")
      (node (ref "C25") (pin "2") (pinfunction "2_2") (pintype "power_in"))
      (node (ref "R48") (pin "1") (pinfunction "1_1") (pintype "passive"))
      (node (ref "R61") (pin "2") (pinfunction "2_2") (pintype "passive"))
      (node (ref "U7") (pin "13") (pinfunction "IN-_13") (pintype "input"))
    )
    (net (code "136") (name "Net-(U7D-OUT)") (class "Default")
      (node (ref "C25") (pin "1") (pinfunction "1_1") (pintype "power_in"))
      (node (ref "R37") (pin "1") (pinfunction "1_1") (pintype "passive"))
      (node (ref "R40") (pin "1") (pinfunction "1_1") (pintype "passive"))
      (node (ref "R48") (pin "2") (pinfunction "2_2") (pintype "passive"))
      (node (ref "R77") (pin "1") (pinfunction "1_1") (pintype "passive"))
      (node (ref "U7") (pin "14") (pinfunction "OUT_14") (pintype "power_in"))
    )
    (net (code "137") (name "Net-(U8A-IN+)") (class "Default")
      (node (ref "C30") (pin "2") (pinfunction "2_2") (pintype "power_in"))
      (node (ref "R51") (pin "2") (pinfunction "2_2") (pintype "passive"))
      (node (ref "U8") (pin "3") (pinfunction "IN+_3") (pintype "input"))
    )
    (net (code "138") (name "Net-(U8B-IN+)") (class "Default")
      (node (ref "R77") (pin "2") (pinfunction "2_2") (pintype "passive"))
      (node (ref "U8") (pin "5") (pinfunction "IN+_5") (pintype "input"))
    )
    (net (code "139") (name "Net-(U9-{slash}RST)") (class "Default")
      (node (ref "R84") (pin "1") (pinfunction "1_1") (pintype "passive"))
      (node (ref "R89") (pin "1") (pinfunction "1_1") (pintype "passive"))
      (node (ref "U9") (pin "1") (pinfunction "/RST_1") (pintype "passive"))
    )
    (net (code "140") (name "Net-(U10-DIN)") (class "Default")
      (node (ref "R32") (pin "2") (pinfunction "2_2") (pintype "passive"))
      (node (ref "U10") (pin "3") (pinfunction "DIN_3") (pintype "passive"))
    )
    (net (code "141") (name "Net-(U10-SCLK)") (class "Default")
      (node (ref "R31") (pin "2") (pinfunction "2_2") (pintype "passive"))
      (node (ref "U10") (pin "2") (pinfunction "SCLK_2") (pintype "passive"))
    )
    (net (code "142") (name "Net-(U10-VOUT)") (class "Default")
      (node (ref "R62") (pin "1") (pinfunction "1_1") (pintype "passive"))
      (node (ref "U10") (pin "6") (pinfunction "VOUT_6") (pintype "passive"))
    )
    (net (code "143") (name "Net-(U12-PC2_(TCK))") (class "Default")
      (node (ref "TP1") (pin "1") (pinfunction "1_1") (pintype "passive"))
      (node (ref "U12") (pin "21") (pinfunction "PC2_(TCK)_21") (pintype "passive"))
    )
    (net (code "144") (name "Net-(U14-IN)") (class "Default")
      (node (ref "C53") (pin "2") (pinfunction "2_2") (pintype "power_in"))
      (node (ref "D18") (pin "2") (pinfunction "2_2") (pintype "passive"))
      (node (ref "U14") (pin "1") (pinfunction "IN_1") (pintype "passive"))
    )
    (net (code "145") (name "Net-(U15A-IN+)") (class "Default")
      (node (ref "R122") (pin "1") (pinfunction "1_1") (pintype "passive"))
      (node (ref "R129") (pin "1") (pinfunction "1_1") (pintype "passive"))
      (node (ref "R130") (pin "2") (pinfunction "2_2") (pintype "passive"))
      (node (ref "R131") (pin "1") (pinfunction "1_1") (pintype "passive"))
      (node (ref "U15") (pin "3") (pinfunction "IN+_3") (pintype "input"))
    )
    (net (code "146") (name "Net-(U15A-IN-)") (class "Default")
      (node (ref "R120") (pin "2") (pinfunction "2_2") (pintype "passive"))
      (node (ref "R121") (pin "2") (pinfunction "2_2") (pintype "passive"))
      (node (ref "U15") (pin "2") (pinfunction "IN-_2") (pintype "input"))
    )
    (net (code "147") (name "Net-(U15A-OUT)") (class "Default")
      (node (ref "R107") (pin "2") (pinfunction "2_2") (pintype "passive"))
      (node (ref "R108") (pin "1") (pinfunction "1_1") (pintype "passive"))
      (node (ref "R122") (pin "2") (pinfunction "2_2") (pintype "passive"))
      (node (ref "R131") (pin "2") (pinfunction "2_2") (pintype "passive"))
      (node (ref "U1") (pin "12") (pintype "passive"))
      (node (ref "U1") (pin "13") (pintype "passive"))
      (node (ref "U15") (pin "1") (pinfunction "OUT_1") (pintype "power_in"))
      (node (ref "U15") (pin "7") (pinfunction "OUT_7") (pintype "power_in"))
    )
    (net (code "148") (name "Net-(U15B-IN+)") (class "Default")
      (node (ref "R107") (pin "1") (pinfunction "1_1") (pintype "passive"))
      (node (ref "R109") (pin "2") (pinfunction "2_2") (pintype "passive"))
      (node (ref "R110") (pin "2") (pinfunction "2_2") (pintype "passive"))
      (node (ref "U15") (pin "5") (pinfunction "IN+_5") (pintype "input"))
    )
    (net (code "149") (name "Net-(U15B-IN-)") (class "Default")
      (node (ref "R116") (pin "2") (pinfunction "2_2") (pintype "passive"))
      (node (ref "R117") (pin "1") (pinfunction "1_1") (pintype "passive"))
      (node (ref "U15") (pin "6") (pinfunction "IN-_6") (pintype "input"))
    )
    (net (code "150") (name "Net-(U16-INA)") (class "Default")
      (node (ref "U16") (pin "2") (pinfunction "INA_2") (pintype "passive"))
      (node (ref "U4") (pin "9") (pintype "passive"))
    )
    (net (code "151") (name "Net-(U16-INB)") (class "Default")
      (node (ref "U16") (pin "4") (pinfunction "INB_4") (pintype "passive"))
      (node (ref "U4") (pin "6") (pintype "passive"))
    )
    (net (code "152") (name "Net-(U16-OUTA)") (class "Default")
      (node (ref "R132") (pin "2") (pinfunction "2_2") (pintype "passive"))
      (node (ref "U16") (pin "7") (pinfunction "OUTA_7") (pintype "passive"))
    )
    (net (code "153") (name "Net-(U16-OUTB)") (class "Default")
      (node (ref "R133") (pin "2") (pinfunction "2_2") (pintype "passive"))
      (node (ref "U16") (pin "5") (pinfunction "OUTB_5") (pintype "passive"))
    )
    (net (code "154") (name "Net-(U17-COMP)") (class "Default")
      (node (ref "C12") (pin "1") (pinfunction "1_1") (pintype "power_in"))
      (node (ref "C15") (pin "1") (pinfunction "1_1") (pintype "power_in"))
      (node (ref "U17") (pin "4") (pinfunction "COMP_4") (pintype "passive"))
    )
    (net (code "155") (name "Net-(U17-EN)") (class "Default")
      (node (ref "R56") (pin "1") (pinfunction "1_1") (pintype "passive"))
      (node (ref "U17") (pin "3") (pinfunction "EN_3") (pintype "passive"))
      (node (ref "VO1") (pin "3") (pinfunction "C_3") (pintype "passive"))
    )
    (net (code "156") (name "Net-(U17-FB)") (class "Default")
      (node (ref "C12") (pin "2") (pinfunction "2_2") (pintype "power_in"))
      (node (ref "R39") (pin "2") (pinfunction "2_2") (pintype "passive"))
      (node (ref "R52") (pin "2") (pinfunction "2_2") (pintype "passive"))
      (node (ref "R53") (pin "2") (pinfunction "2_2") (pintype "passive"))
      (node (ref "R54") (pin "1") (pinfunction "1_1") (pintype "passive"))
      (node (ref "U17") (pin "5") (pinfunction "FB_5") (pintype "passive"))
    )
    (net (code "157") (name "Net-(U17-FSW)") (class "Default")
      (node (ref "R42") (pin "2") (pinfunction "2_2") (pintype "passive"))
      (node (ref "U17") (pin "6") (pinfunction "FSW_6") (pintype "passive"))
    )
    (net (code "158") (name "Net-(U17-OUT)") (class "Default")
      (node (ref "D29") (pin "2") (pinfunction "2_2") (pintype "passive"))
      (node (ref "L1") (pin "2") (pinfunction "2_2") (pintype "passive"))
      (node (ref "U17") (pin "1") (pinfunction "OUT_1") (pintype "passive"))
    )
    (net (code "159") (name "Net-(VO1-A)") (class "Default")
      (node (ref "D6") (pin "2") (pinfunction "2_2") (pintype "passive"))
      (node (ref "R3") (pin "1") (pinfunction "1_1") (pintype "passive"))
      (node (ref "VO1") (pin "1") (pinfunction "A_1") (pintype "passive"))
    )
    (net (code "160") (name "unconnected-(RC5-Pad1)") (class "Default")
      (node (ref "RC5") (pin "1") (pinfunction "1_1") (pintype "passive"))
    )
    (net (code "161") (name "unconnected-(RC5-Pad2)") (class "Default")
      (node (ref "RC5") (pin "2") (pinfunction "2_2") (pintype "passive"))
    )
    (net (code "162") (name "unconnected-(RC6-Pad2)") (class "Default")
      (node (ref "RC6") (pin "2") (pinfunction "2_2") (pintype "passive"))
    )
    (net (code "163") (name "unconnected-(U3B-{slash}Q-Pad12)") (class "Default")
      (node (ref "U3") (pin "12") (pinfunction "/Q_12") (pintype "passive"))
    )
    (net (code "164") (name "unconnected-(U11-NC-Pad3)") (class "Default")
      (node (ref "U11") (pin "3") (pinfunction "NC_3") (pintype "passive"))
    )
    (net (code "165") (name "unconnected-(U16-NC-Pad1)") (class "Default")
      (node (ref "U16") (pin "1") (pinfunction "NC_1") (pintype "passive"))
    )
    (net (code "166") (name "unconnected-(U16-NC-Pad8)") (class "Default")
      (node (ref "U16") (pin "8") (pinfunction "NC_8") (pintype "passive"))
    )
    (net (code "167") (name "unconnected-(U17-SYNC-Pad2)") (class "Default")
      (node (ref "U17") (pin "2") (pinfunction "SYNC_2") (pintype "passive"))
    )
  )
)
